# SAST_PCB_V2B_Test_Beta_Main.net
KiCad netlist of a schematic drawn in Altium Designer
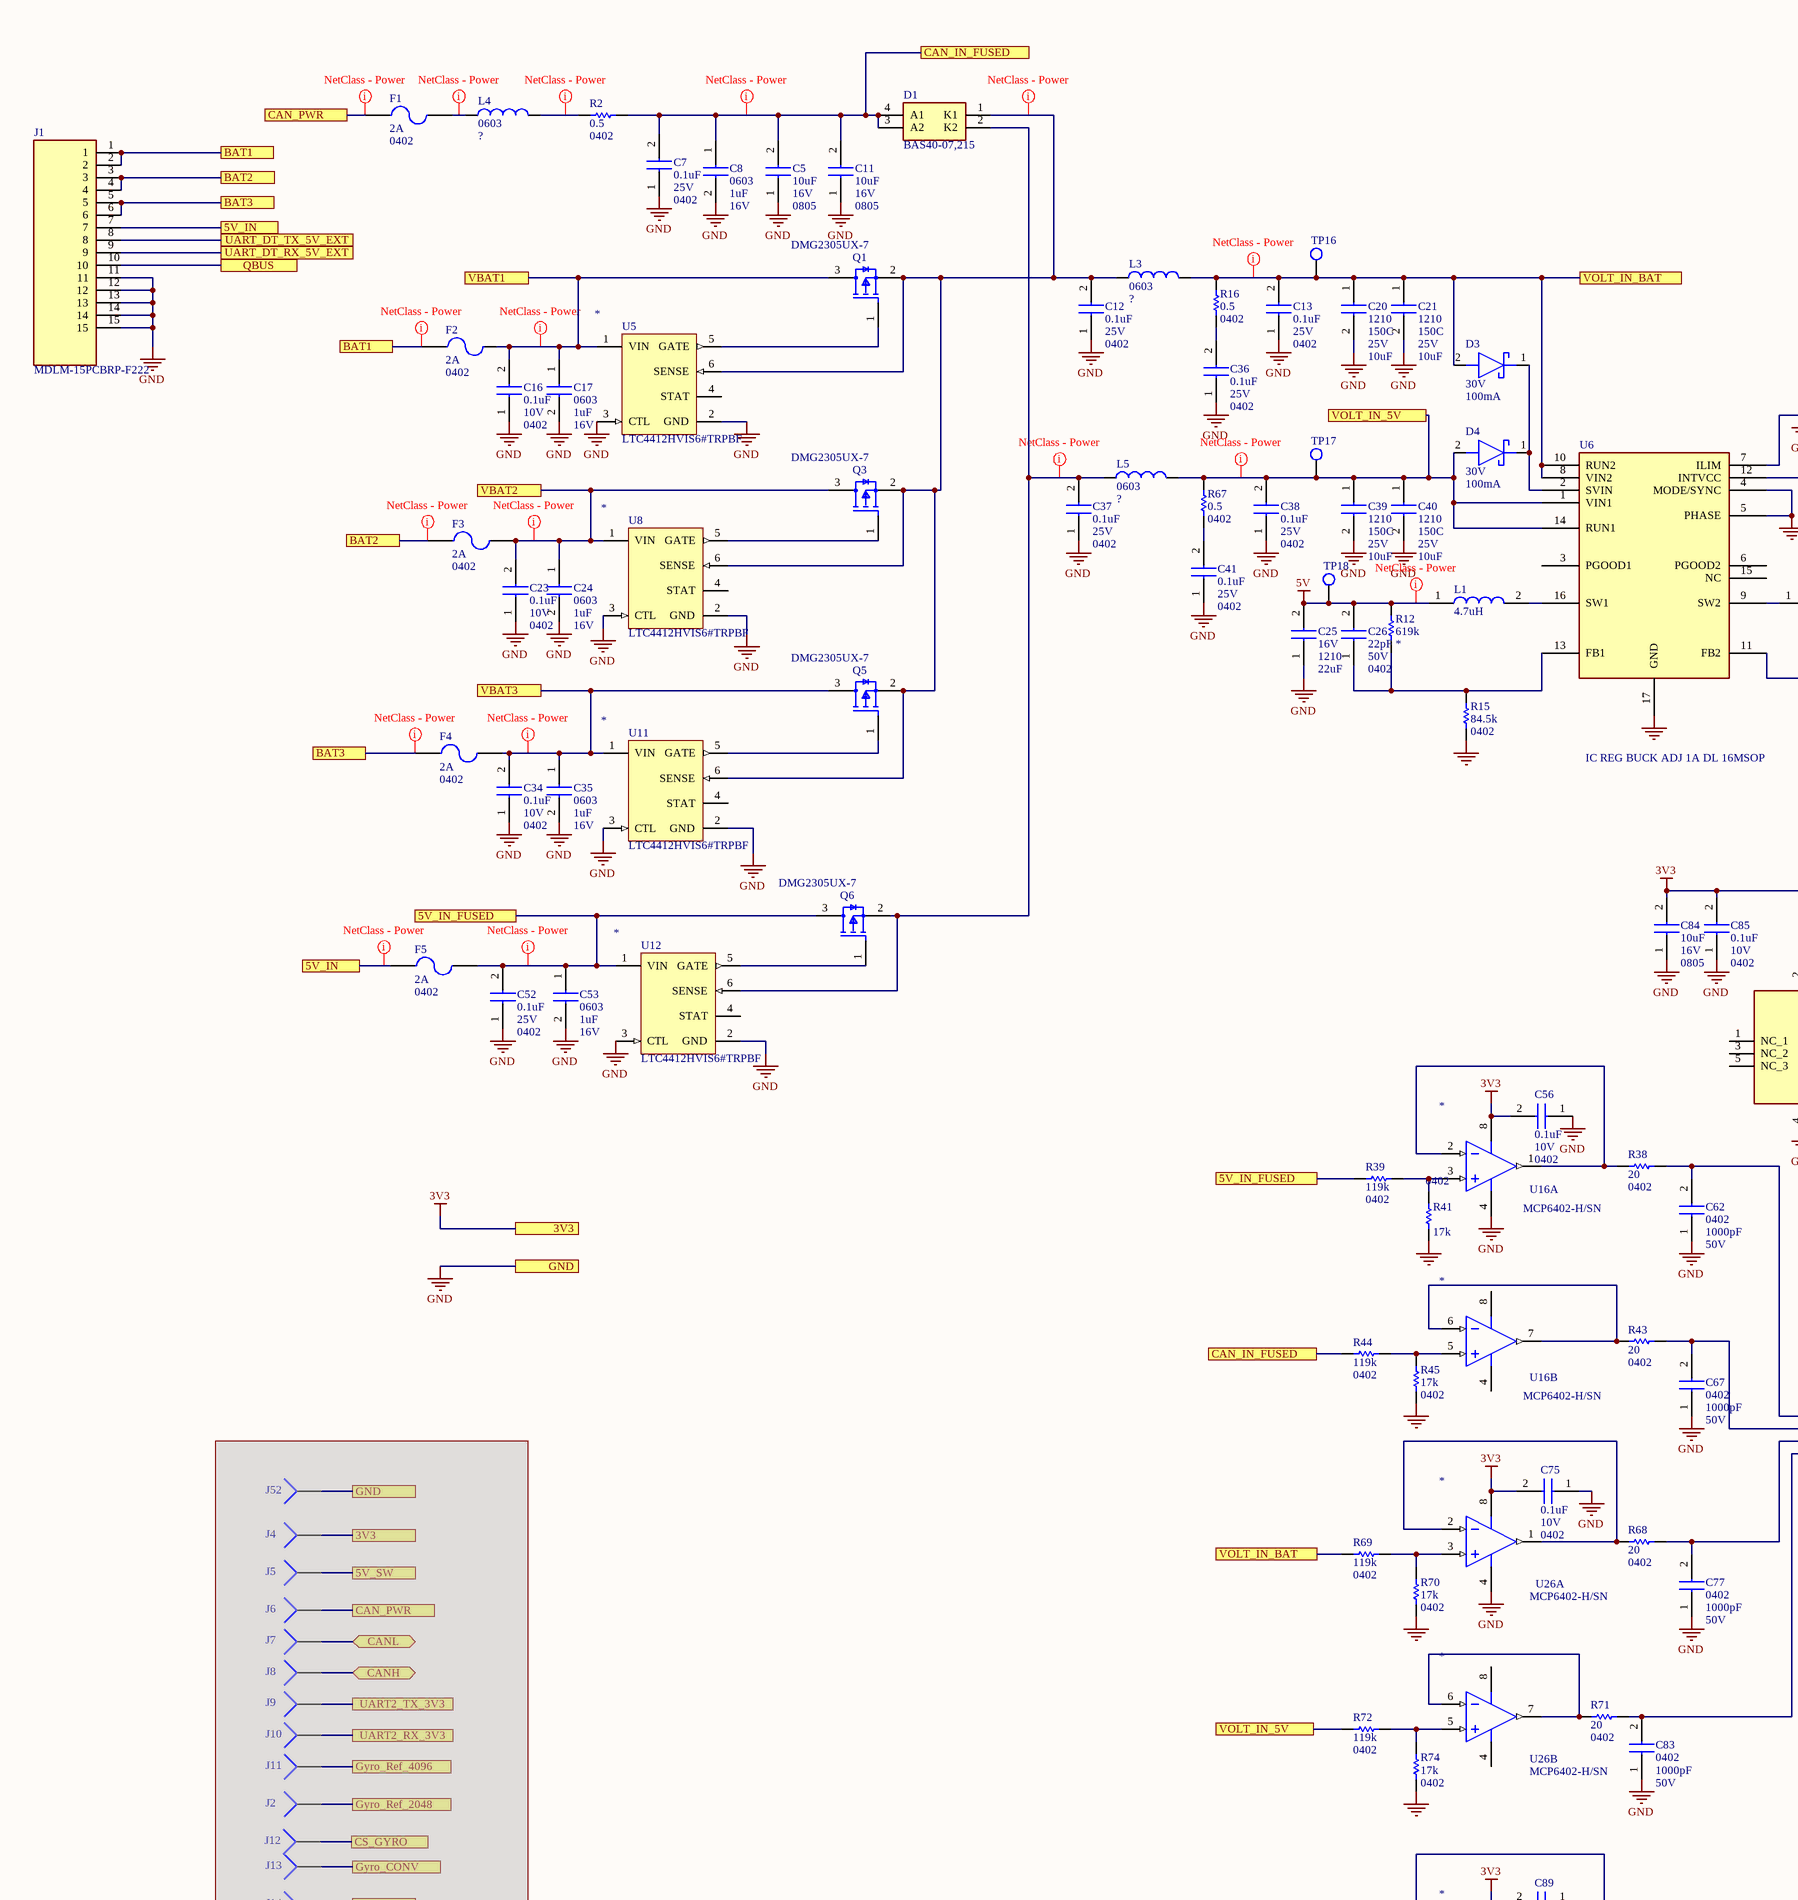
[diagram p0: SAST_PCB_V2B_Test_Beta_Main.SchDoc, top left]
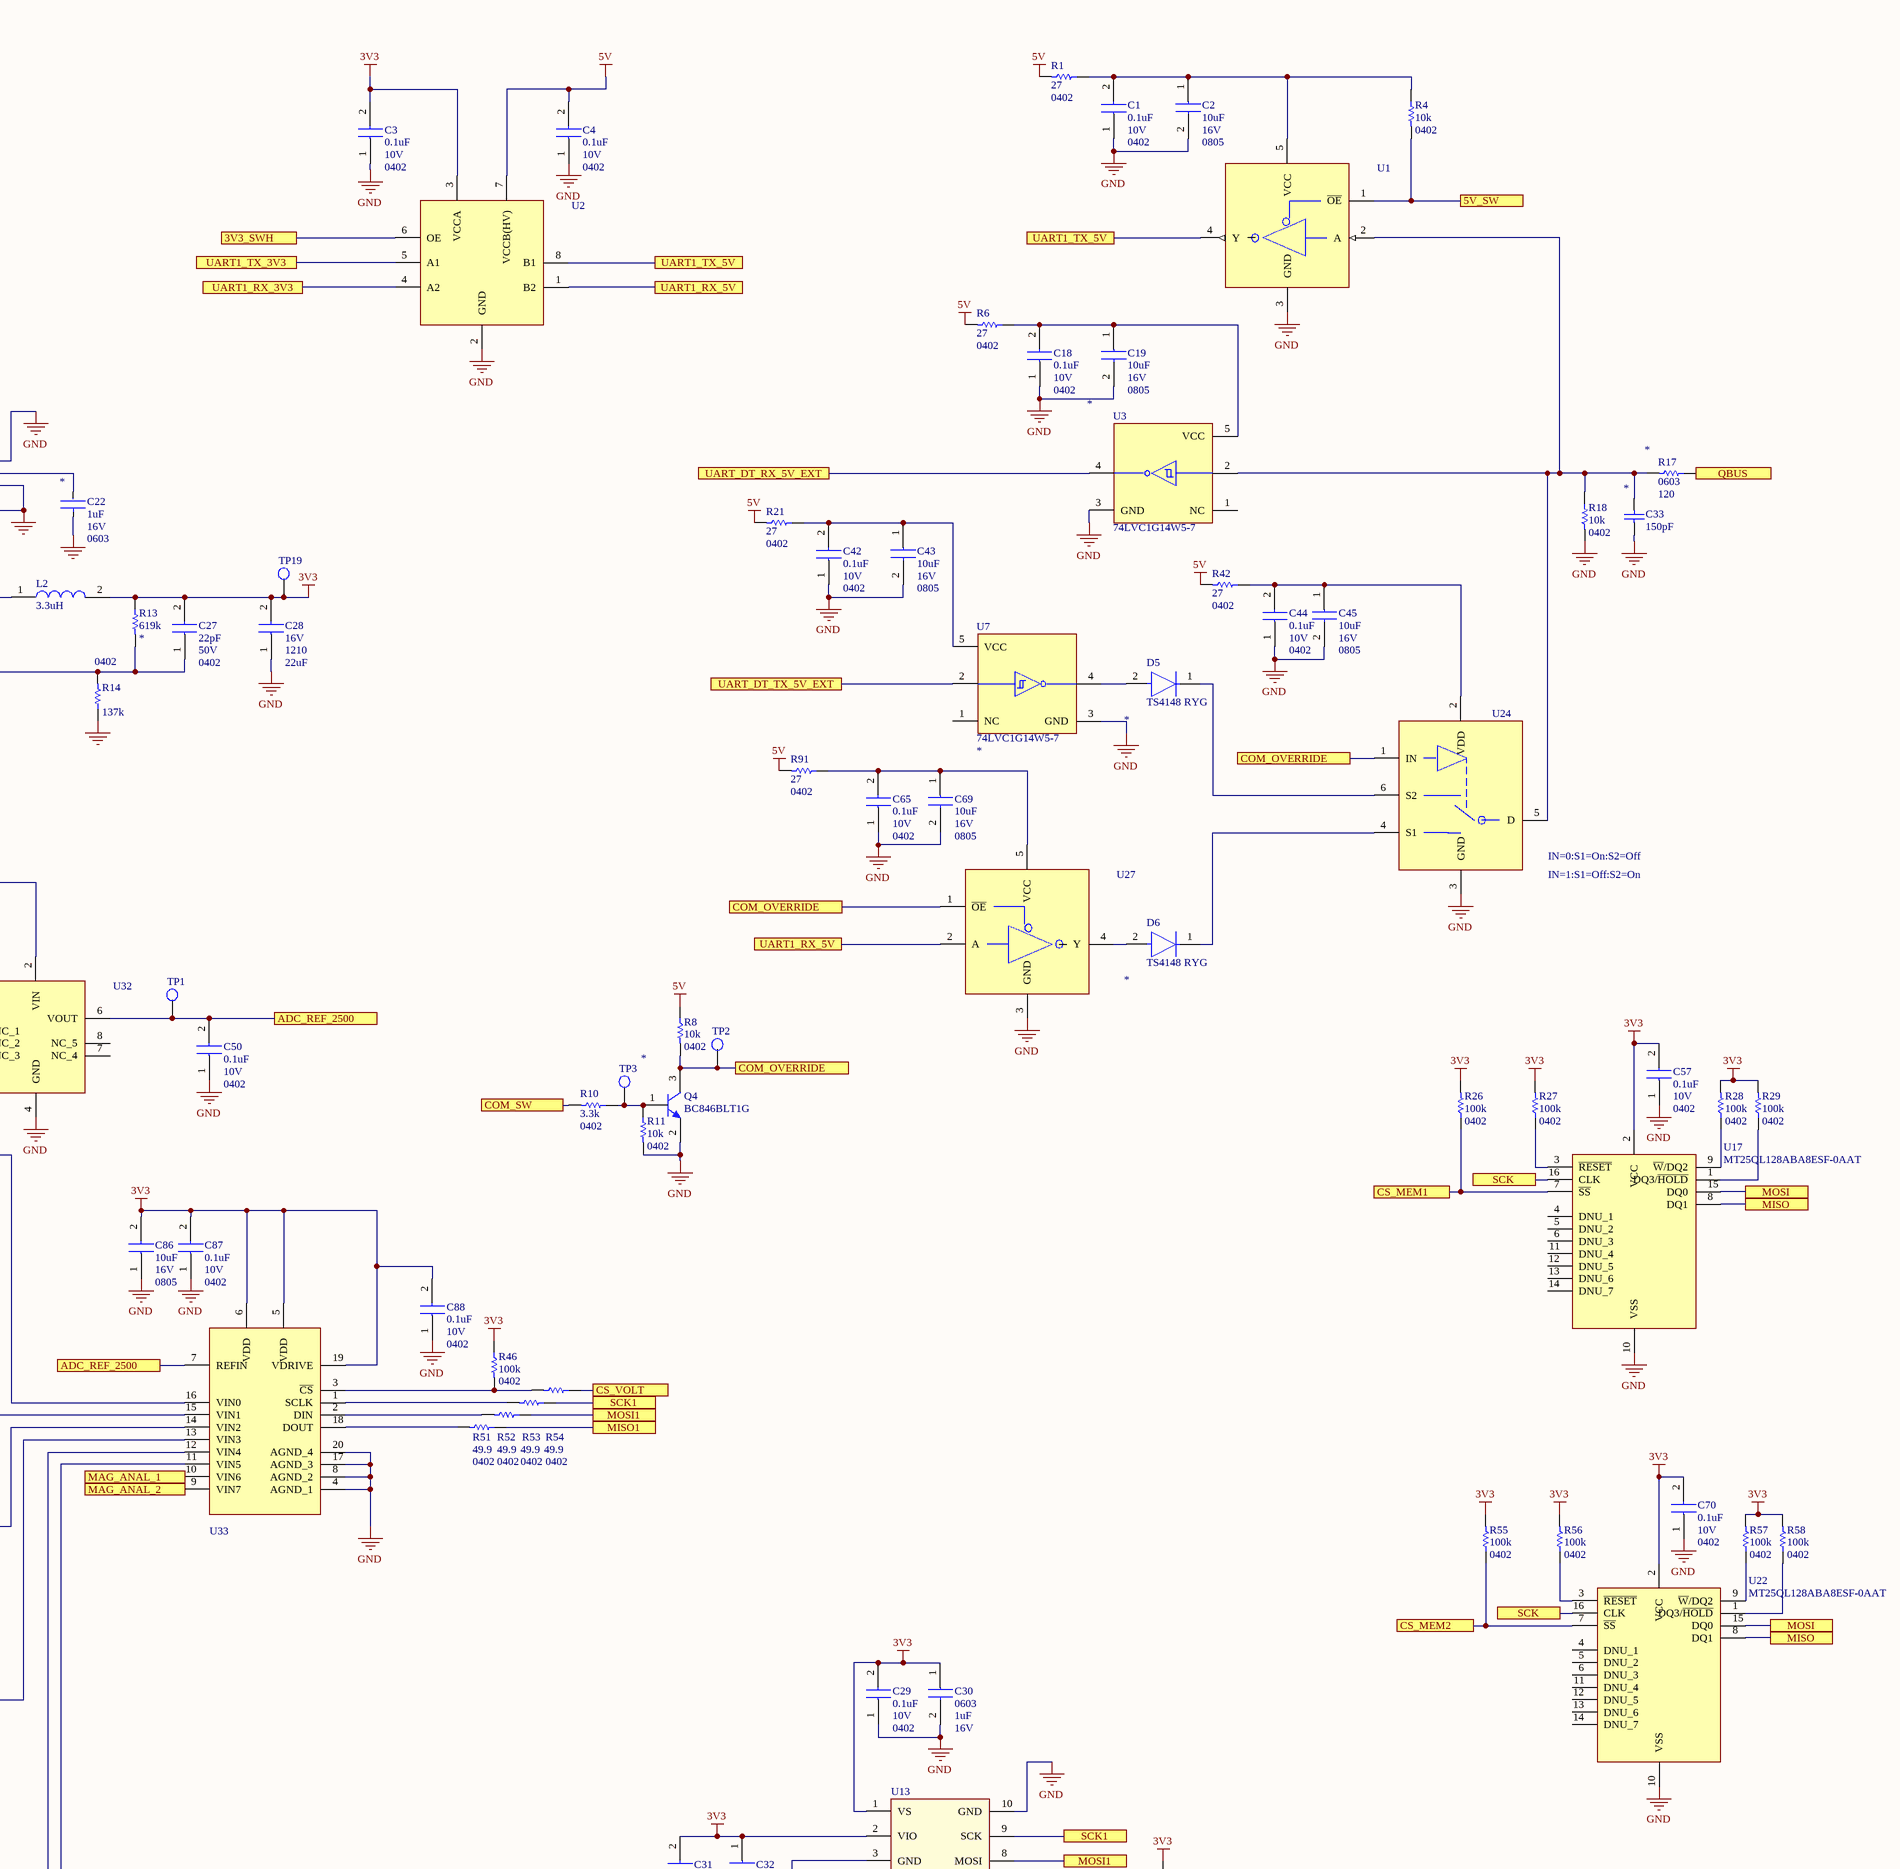
[diagram p1: SAST_PCB_V2B_Test_Beta_Main.SchDoc, top middle]
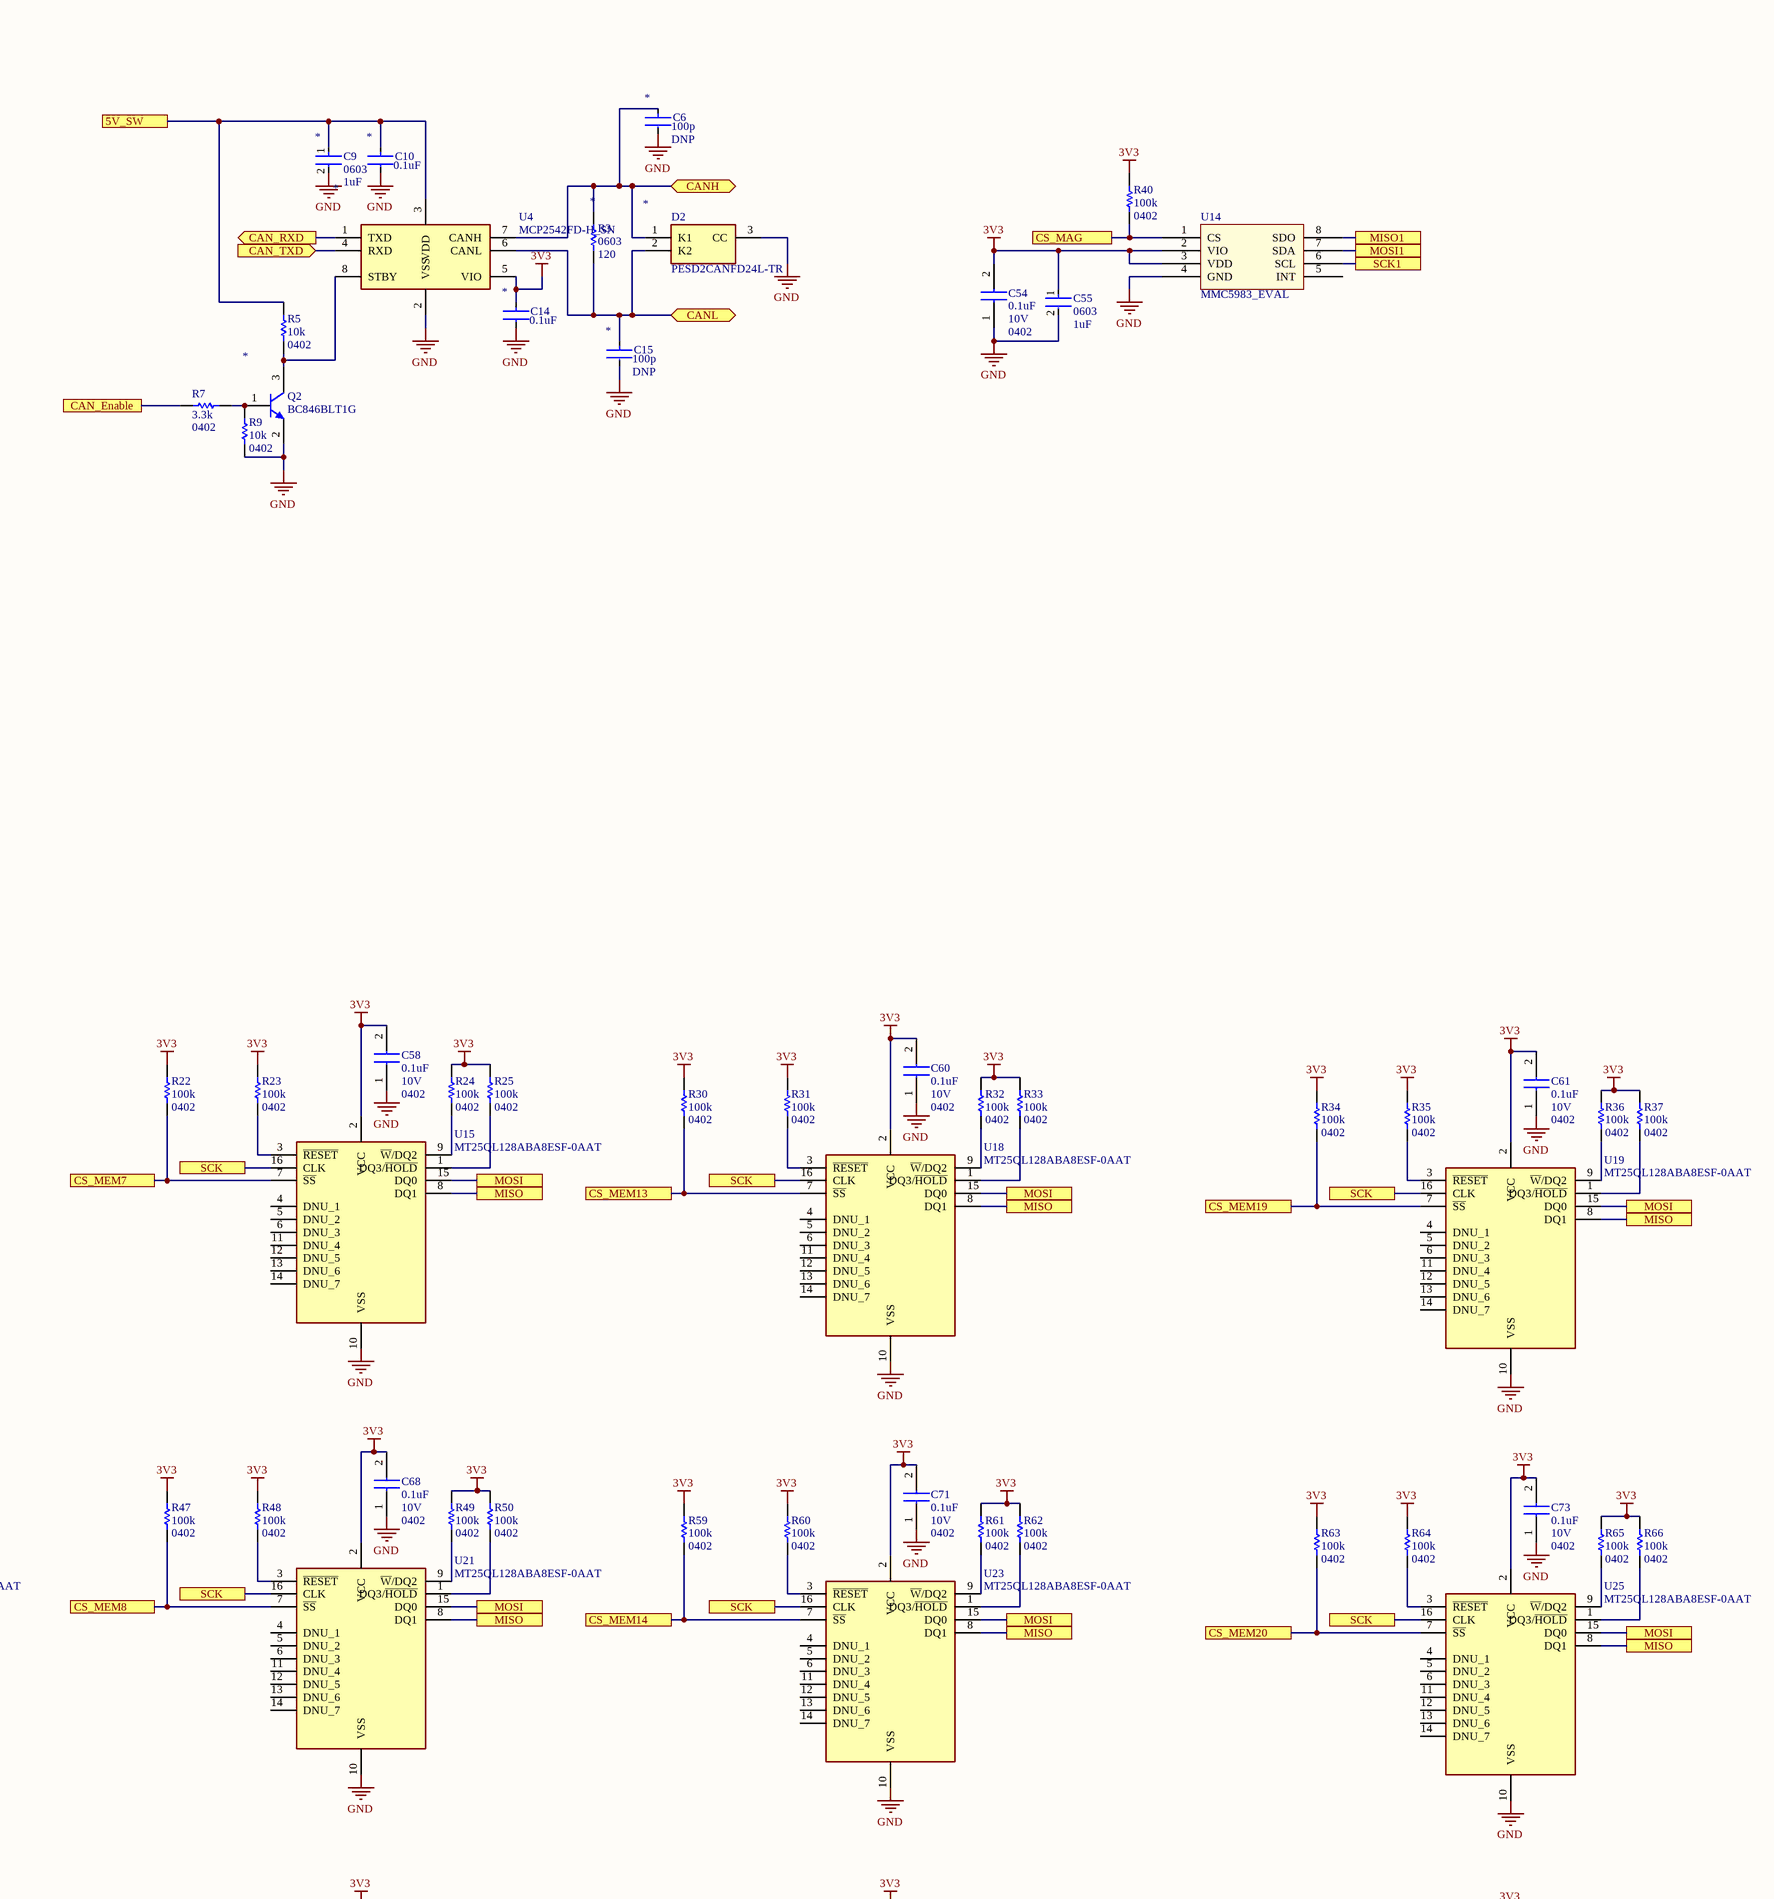
[diagram p2: SAST_PCB_V2B_Test_Beta_Main.SchDoc, top right]
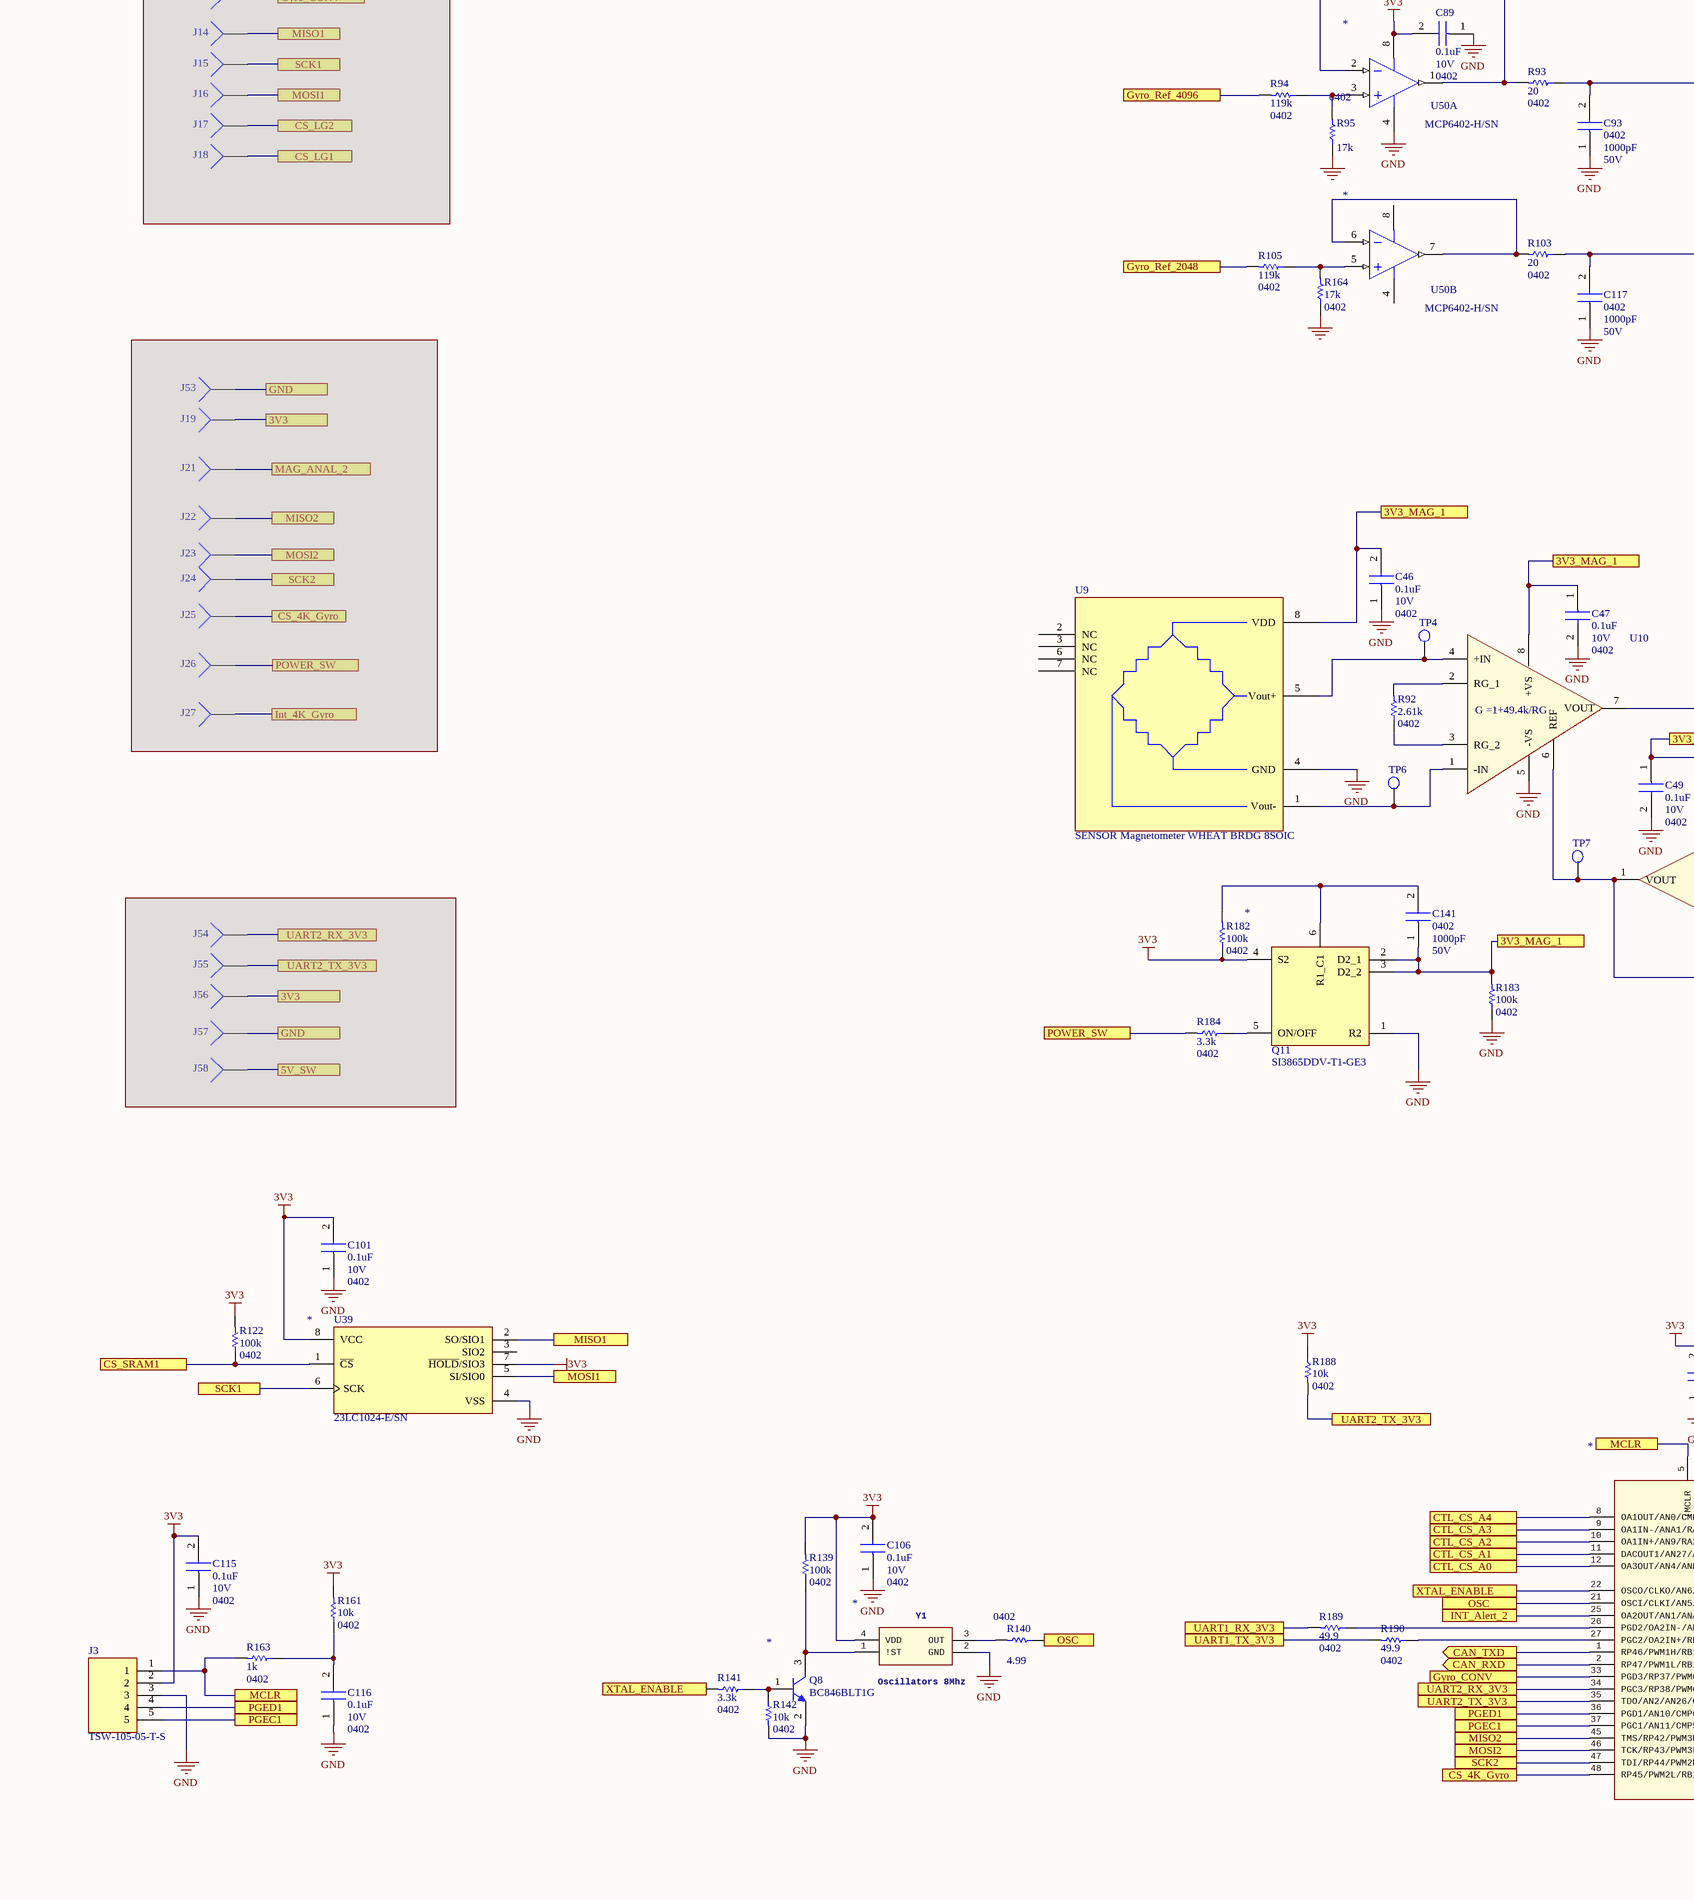
[diagram p3: SAST_PCB_V2B_Test_Beta_Main.SchDoc, bottom left]
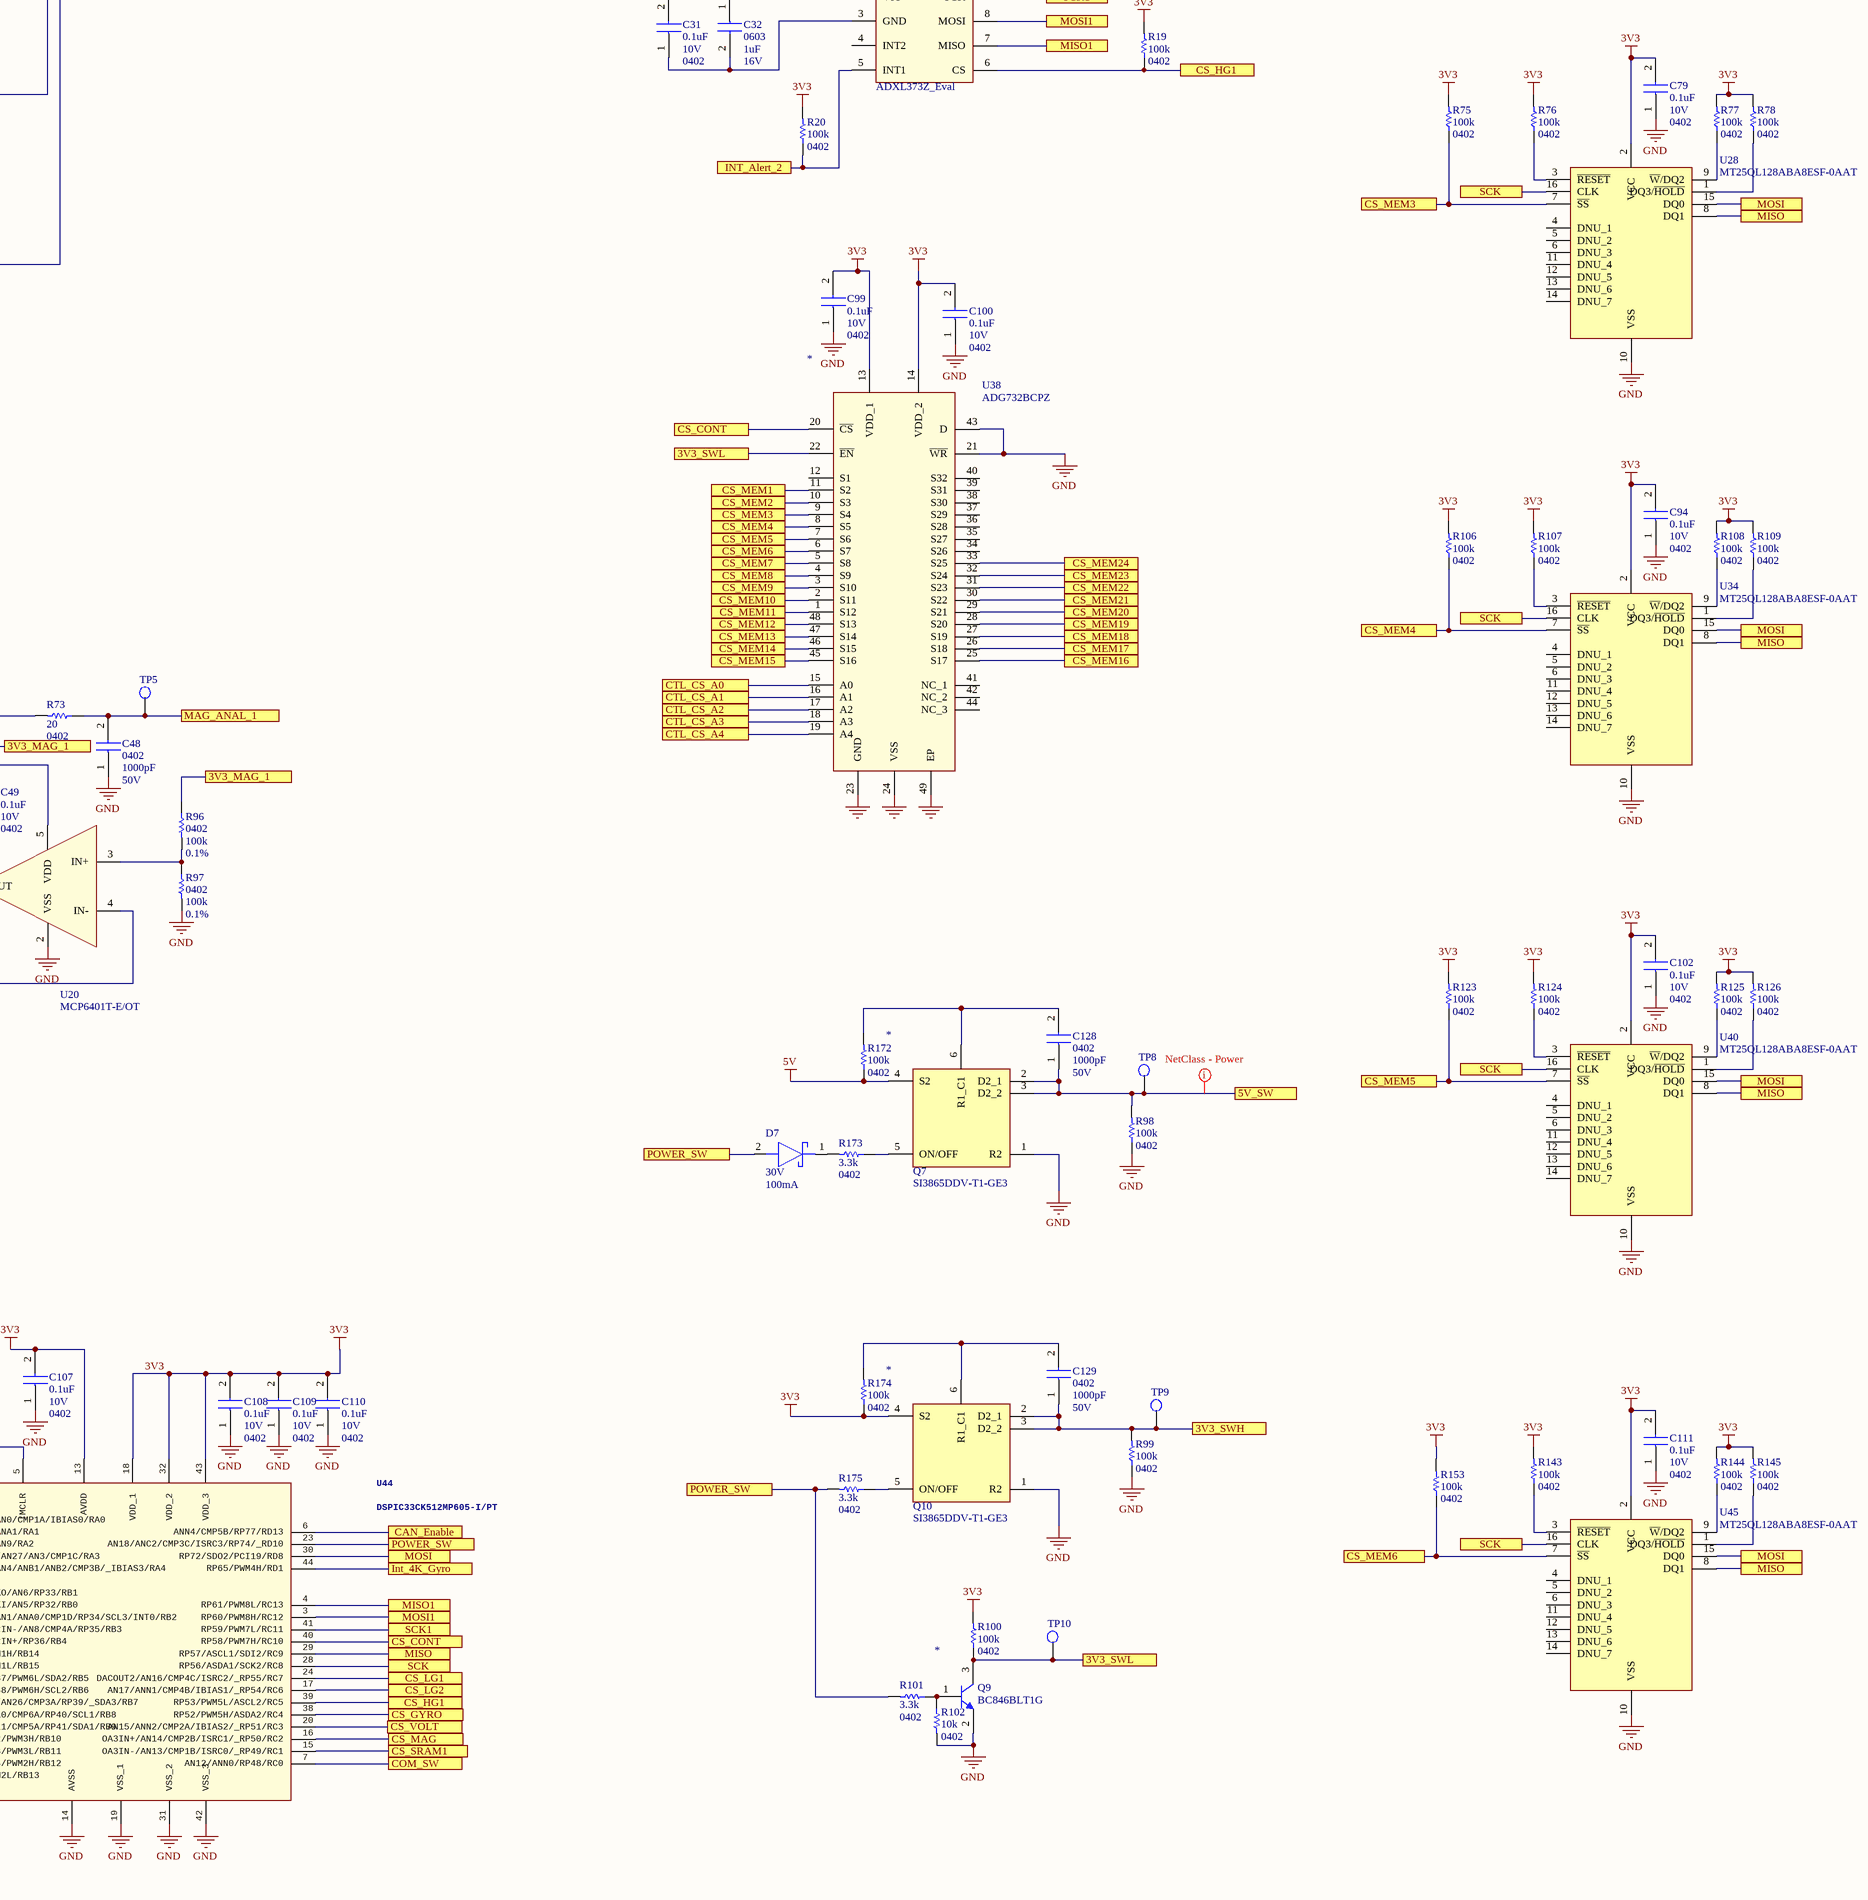
[diagram p4: SAST_PCB_V2B_Test_Beta_Main.SchDoc, bottom middle]
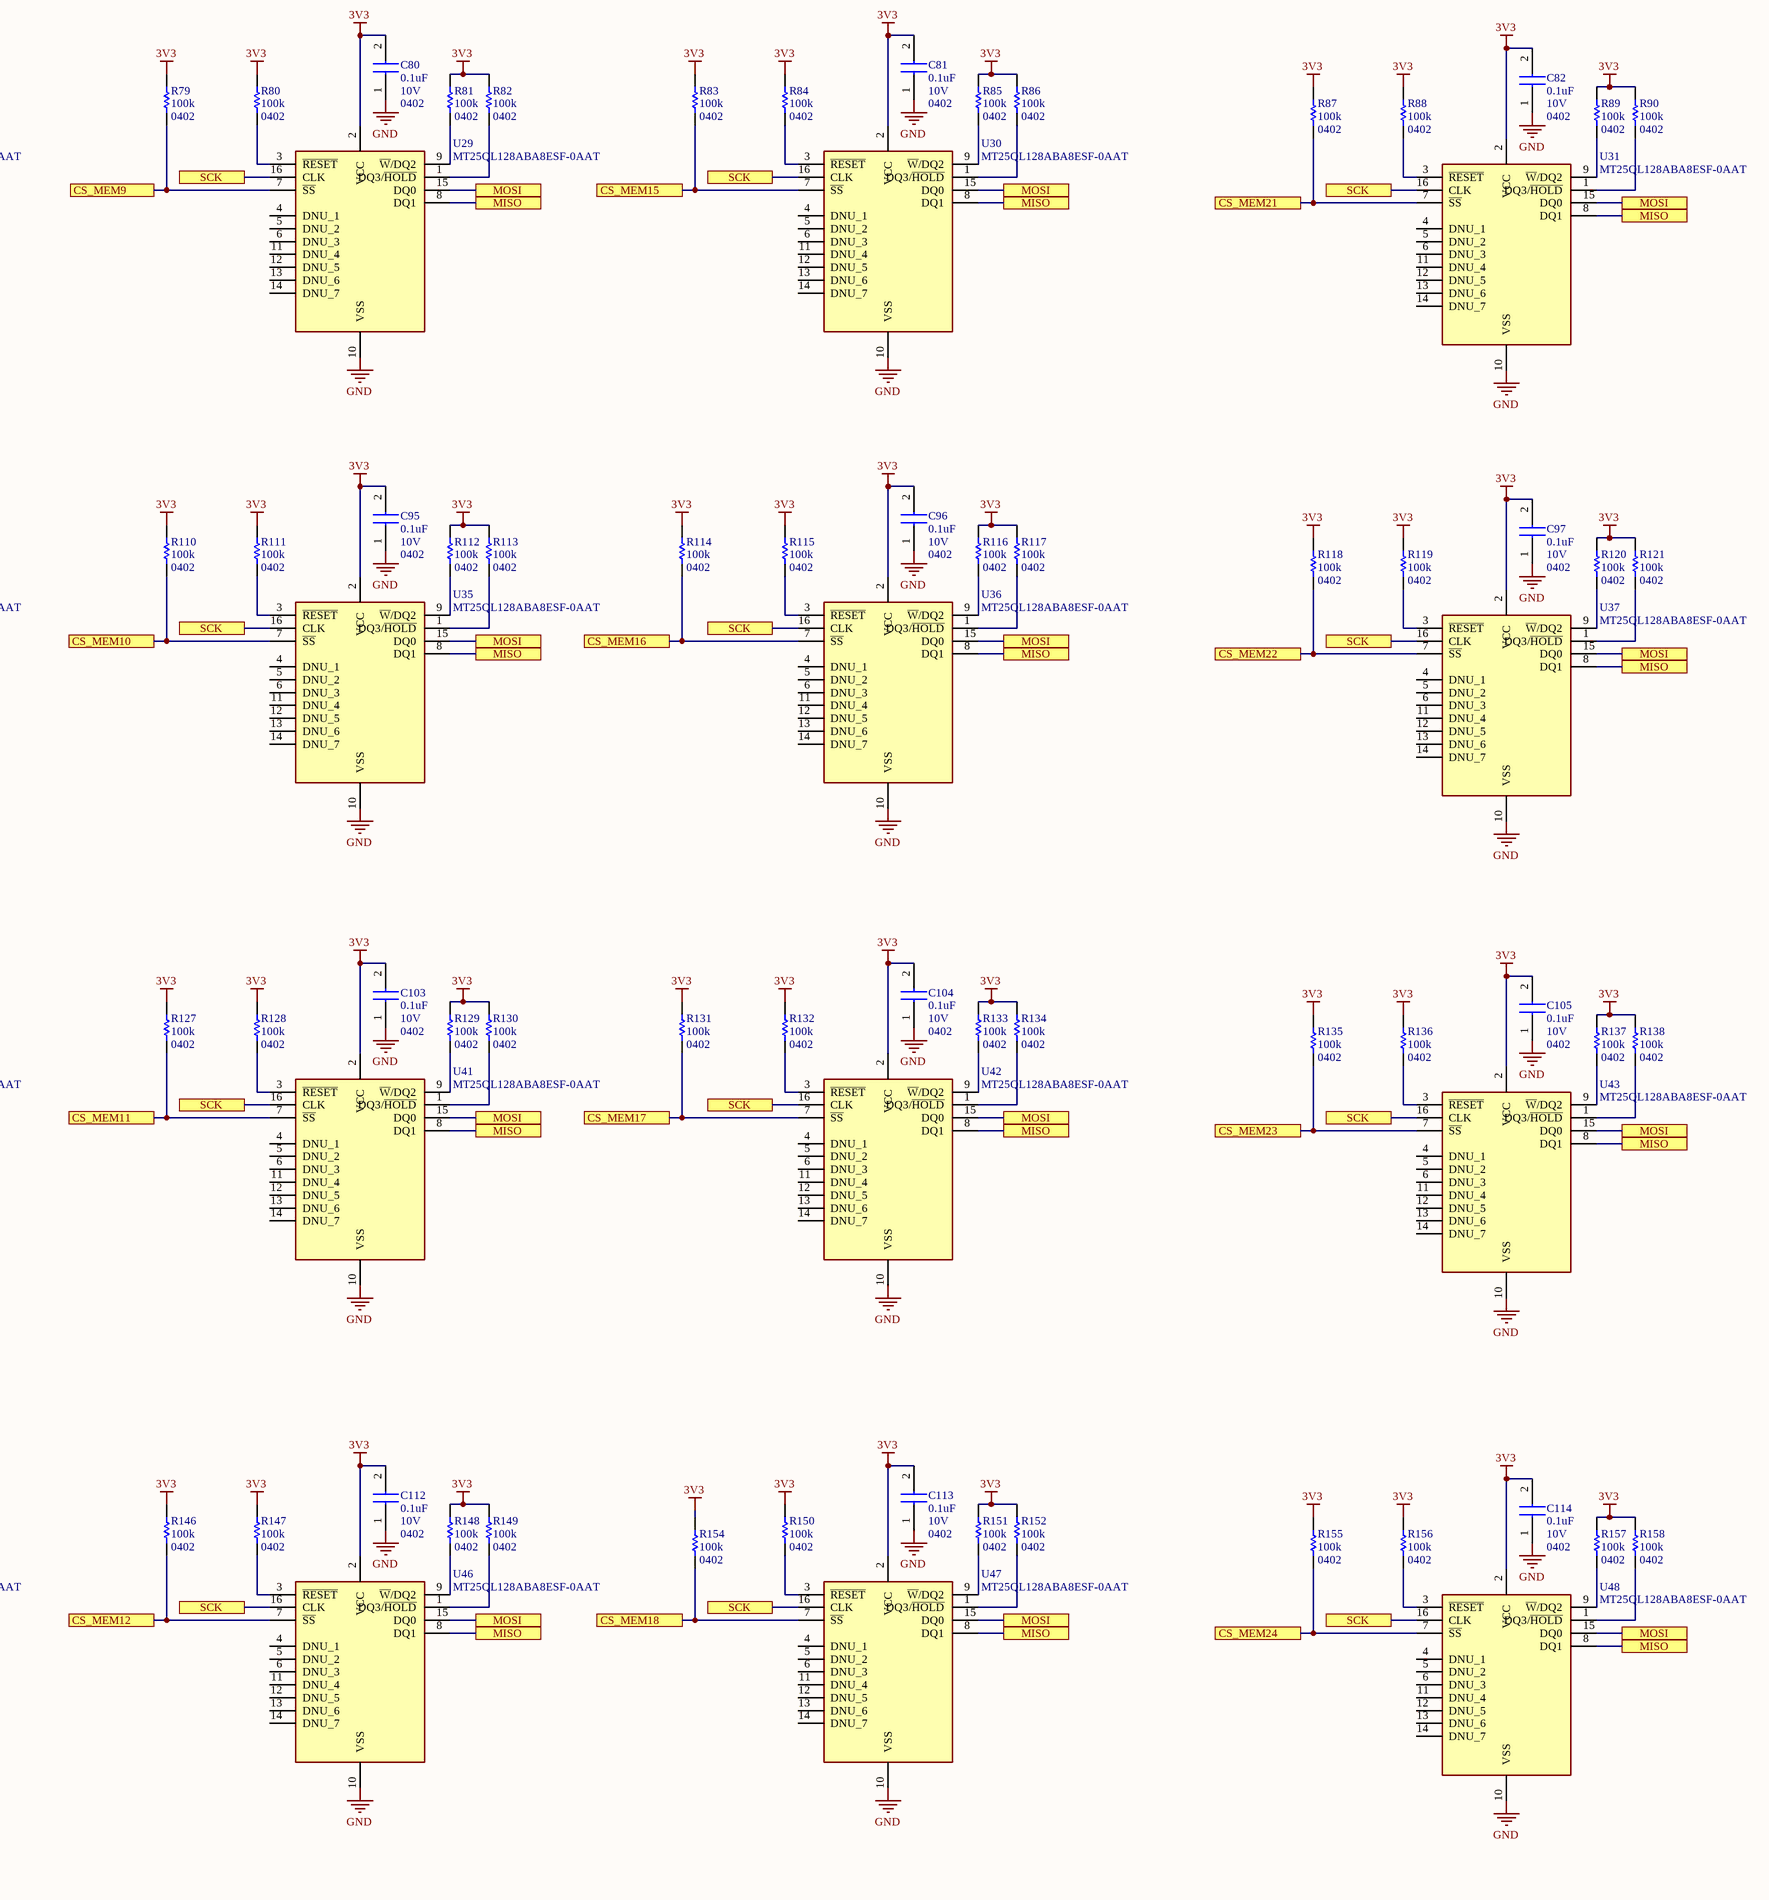
[diagram p5: SAST_PCB_V2B_Test_Beta_Main.SchDoc, bottom right]

(export (version "E")
  (design (tool "Eeschema 10.0.6"))
  (components
    (comp (ref "C1")
      (value "0.1uF")
      (footprint "0402_DSP")
      (description "Capacitor: 0.1 µF ±10% 10V Ceramic Capacitor X8M 0201")
      (fields
        (field (name "MANUFACTURER_PART_NUMBER") "GCM033M8ED104KE07J")
        (field (name "MOUSER PART NUMBER") "81-GCM033M8ED104KE07")
        (field (name "VOLTAGE") "10V")
        (field (name "CASE/PACKAGE") "0402")
      )
      (libsource (lib "CS_Library") (part "GCM033M8ED104KE07J"))
    )
    (comp (ref "C2")
      (value "10uF")
      (footprint "0805_DSP")
      (description "Capacitor:  10 µF ±10% 16V Ceramic Capacitor X8M 0805 (2012 Metric)")
      (fields
        (field (name "MANUFACTURER_PART_NUMBER") "GCM21BM8EE106KE08L")
        (field (name "MOUSER PART NUMBER") "81-GCM21BM8EE106KE8L")
        (field (name "VOLTAGE") "16V")
        (field (name "CASE/PACKAGE") "0805")
      )
      (libsource (lib "CS_Library") (part "GCM21BM8EE106KE08L"))
    )
    (comp (ref "C3")
      (value "0.1uF")
      (footprint "0402_DSP")
      (description "Capacitor: 0.1 µF ±10% 10V Ceramic Capacitor X8M 0201")
      (fields
        (field (name "MANUFACTURER_PART_NUMBER") "GCM033M8ED104KE07J")
        (field (name "MOUSER PART NUMBER") "81-GCM033M8ED104KE07")
        (field (name "VOLTAGE") "10V")
        (field (name "CASE/PACKAGE") "0402")
      )
      (libsource (lib "CS_Library") (part "GCM033M8ED104KE07J"))
    )
    (comp (ref "C4")
      (value "0.1uF")
      (footprint "0402_DSP")
      (description "Capacitor: 0.1 µF ±10% 10V Ceramic Capacitor X8M 0201")
      (fields
        (field (name "MANUFACTURER_PART_NUMBER") "GCM033M8ED104KE07J")
        (field (name "MOUSER PART NUMBER") "81-GCM033M8ED104KE07")
        (field (name "VOLTAGE") "10V")
        (field (name "CASE/PACKAGE") "0402")
      )
      (libsource (lib "CS_Library") (part "GCM033M8ED104KE07J"))
    )
    (comp (ref "C5")
      (value "10uF")
      (footprint "CS_Library:CAPC2012X140N")
      (description "Capacitor:  10 µF ±10% 16V Ceramic Capacitor X8M 0805 (2012 Metric)")
      (fields
        (field (name "MANUFACTURER_PART_NUMBER") "GCM21BM8EE106KE08L")
        (field (name "MOUSER PART NUMBER") "81-GCM21BM8EE106KE8L")
        (field (name "VOLTAGE") "16V")
        (field (name "CASE/PACKAGE") "0805")
      )
      (libsource (lib "CS_Library") (part "GCM21BM8EE106KE08L"))
    )
    (comp (ref "C6")
      (value "100p")
      (footprint "FP-GCM155-0_05-IPC_B")
      (description "Ceramic Capacitor for Automotive 100nF ±10% 25VDC X8L 0402 Paper T/R")
      (fields
        (field (name "MANUFACTURING") "DNP")
        (field (name "CASE/PACKAGE") "*")
        (field (name "Comment") "GCM155L81E104KE02D")
      )
      (libsource (lib "") (part "02cd4be3c70576c341d710602a673aa_1"))
    )
    (comp (ref "C7")
      (value "0.1uF")
      (footprint "CS_Library:0402_DSP")
      (description "Capacitor: 0.1 µF ±10% 25V Ceramic Capacitor X8L 0402 (1005 Metric)")
      (fields
        (field (name "MANUFACTURER_PART_NUMBER") "GCM155L81E104KE02D")
        (field (name "MOUSER PART NUMBER") "81-GCM155L81E104KE2D")
        (field (name "VOLTAGE") "25V")
        (field (name "CASE/PACKAGE") "0402")
      )
      (libsource (lib "CS_Library") (part "GCM155L81E104KE02D"))
    )
    (comp (ref "C8")
      (value "1uF")
      (footprint "0603_DSP")
      (description "Capacitor: 1 µF ±10% 16V Ceramic Capacitor X8L 0603")
      (fields
        (field (name "MANUFACTURER_PART_NUMBER") "GCG188L8EE105KA07D")
        (field (name "MOUSER PART NUMBER") "81-GCG188L8EE105KA7D")
        (field (name "CASE/PACKAGE") "0603")
        (field (name "VOLTAGE") "16V")
      )
      (libsource (lib "CS_Library") (part "GCG188L8EE105KA07D"))
    )
    (comp (ref "C9")
      (value "0603")
      (footprint "FP-GCG188-0_2-IPC_A")
      (fields
        (field (name "MANUFACTURER_PART_NUMBER") "GCG188L8EE105KA07D")
        (field (name "ALTIUM_VALUE") "1uF")
        (field (name "VOLTAGE") "16V")
        (field (name "CASE/PACKAGE") "*")
      )
      (libsource (lib "Altium Content Vault") (part "02cd4be3c70576c341d710602a673aa"))
    )
    (comp (ref "C10")
      (value "0.1uF")
      (footprint "FP-GCM155-0_05-IPC_B")
      (description "Ceramic Capacitor for Automotive 100nF ±10% 25VDC X8L 0402 Paper T/R")
      (fields
        (field (name "MANUFACTURER_PART_NUMBER") "GCM155L81E104KE02D")
        (field (name "VOLTAGE") "25V")
        (field (name "CASE/PACKAGE") "*")
      )
      (libsource (lib "") (part "02cd4be3c70576c341d710602a673aa_1"))
    )
    (comp (ref "C11")
      (value "10uF")
      (footprint "CS_Library:CAPC2012X140N")
      (description "Capacitor:  10 µF ±10% 16V Ceramic Capacitor X8M 0805 (2012 Metric)")
      (fields
        (field (name "MANUFACTURER_PART_NUMBER") "GCM21BM8EE106KE08L")
        (field (name "MOUSER PART NUMBER") "81-GCM21BM8EE106KE8L")
        (field (name "VOLTAGE") "16V")
        (field (name "CASE/PACKAGE") "0805")
      )
      (libsource (lib "CS_Library") (part "GCM21BM8EE106KE08L"))
    )
    (comp (ref "C12")
      (value "0.1uF")
      (footprint "CS_Library:0402_DSP")
      (description "Capacitor: 0.1 µF ±10% 25V Ceramic Capacitor X8L 0402 (1005 Metric)")
      (fields
        (field (name "MANUFACTURER_PART_NUMBER") "GCM155L81E104KE02D")
        (field (name "MOUSER PART NUMBER") "81-GCM155L81E104KE2D")
        (field (name "VOLTAGE") "25V")
        (field (name "CASE/PACKAGE") "0402")
      )
      (libsource (lib "CS_Library") (part "GCM155L81E104KE02D"))
    )
    (comp (ref "C13")
      (value "0.1uF")
      (footprint "CS_Library:0402_DSP")
      (description "Capacitor: 0.1 µF ±10% 25V Ceramic Capacitor X8L 0402 (1005 Metric)")
      (fields
        (field (name "MANUFACTURER_PART_NUMBER") "GCM155L81E104KE02D")
        (field (name "MOUSER PART NUMBER") "81-GCM155L81E104KE2D")
        (field (name "VOLTAGE") "25V")
        (field (name "CASE/PACKAGE") "0402")
      )
      (libsource (lib "CS_Library") (part "GCM155L81E104KE02D"))
    )
    (comp (ref "C14")
      (value "0.1uF")
      (footprint "FP-GCM155-0_05-IPC_B")
      (description "Ceramic Capacitor for Automotive 100nF ±10% 25VDC X8L 0402 Paper T/R")
      (fields
        (field (name "MANUFACTURER_PART_NUMBER") "GCM155L81E104KE02D")
        (field (name "VOLTAGE") "25V")
        (field (name "CASE/PACKAGE") "*")
      )
      (libsource (lib "") (part "02cd4be3c70576c341d710602a673aa_1"))
    )
    (comp (ref "C15")
      (value "100p")
      (footprint "FP-GCM155-0_05-IPC_B")
      (description "Ceramic Capacitor for Automotive 100nF ±10% 25VDC X8L 0402 Paper T/R")
      (fields
        (field (name "MANUFACTURING") "DNP")
        (field (name "CASE/PACKAGE") "*")
        (field (name "Comment") "GCM155L81E104KE02D")
      )
      (libsource (lib "") (part "02cd4be3c70576c341d710602a673aa_1"))
    )
    (comp (ref "C16")
      (value "0.1uF")
      (footprint "0402_DSP")
      (description "Capacitor: 0.1 µF ±10% 10V Ceramic Capacitor X8M 0201")
      (fields
        (field (name "MANUFACTURER_PART_NUMBER") "GCM033M8ED104KE07J")
        (field (name "MOUSER PART NUMBER") "81-GCM033M8ED104KE07")
        (field (name "VOLTAGE") "10V")
        (field (name "CASE/PACKAGE") "0402")
      )
      (libsource (lib "CS_Library") (part "GCM033M8ED104KE07J"))
    )
    (comp (ref "C17")
      (value "1uF")
      (footprint "0603_DSP")
      (description "Capacitor: 1 µF ±10% 16V Ceramic Capacitor X8L 0603")
      (fields
        (field (name "MANUFACTURER_PART_NUMBER") "GCG188L8EE105KA07D")
        (field (name "MOUSER PART NUMBER") "81-GCG188L8EE105KA7D")
        (field (name "CASE/PACKAGE") "0603")
        (field (name "VOLTAGE") "16V")
      )
      (libsource (lib "CS_Library") (part "GCG188L8EE105KA07D"))
    )
    (comp (ref "C18")
      (value "0.1uF")
      (footprint "0402_DSP")
      (description "Capacitor: 0.1 µF ±10% 10V Ceramic Capacitor X8M 0201")
      (fields
        (field (name "MANUFACTURER_PART_NUMBER") "GCM033M8ED104KE07J")
        (field (name "MOUSER PART NUMBER") "81-GCM033M8ED104KE07")
        (field (name "VOLTAGE") "10V")
        (field (name "CASE/PACKAGE") "0402")
      )
      (libsource (lib "CS_Library") (part "GCM033M8ED104KE07J"))
    )
    (comp (ref "C19")
      (value "10uF")
      (footprint "0805_DSP")
      (description "Capacitor:  10 µF ±10% 16V Ceramic Capacitor X8M 0805 (2012 Metric)")
      (fields
        (field (name "MANUFACTURER_PART_NUMBER") "GCM21BM8EE106KE08L")
        (field (name "MOUSER PART NUMBER") "81-GCM21BM8EE106KE8L")
        (field (name "VOLTAGE") "16V")
        (field (name "CASE/PACKAGE") "0805")
      )
      (libsource (lib "CS_Library") (part "GCM21BM8EE106KE08L"))
    )
    (comp (ref "C20")
      (value "10uF")
      (footprint "CS_Library:CAPC3225X280N")
      (description "Capacitor: 10 µF ±10% 25V Ceramic Capacitor X8R 1210 (3225 Metric)")
      (fields
        (field (name "MANUFACTURER_PART_NUMBER") "CGA6P1X8R1E106K250AC")
        (field (name "MOUSER PART NUMBER") "810-A6P1X816K25AC")
        (field (name "CASE/PACKAGE") "1210")
        (field (name "TEMPERATURE") "150C")
        (field (name "VOLTAGE") "25V")
      )
      (libsource (lib "CS_Library") (part "CGA6P1X8R1E106K250AC"))
    )
    (comp (ref "C21")
      (value "10uF")
      (footprint "CS_Library:CAPC3225X280N")
      (description "Capacitor: 10 µF ±10% 25V Ceramic Capacitor X8R 1210 (3225 Metric)")
      (fields
        (field (name "MANUFACTURER_PART_NUMBER") "CGA6P1X8R1E106K250AC")
        (field (name "MOUSER PART NUMBER") "810-A6P1X816K25AC")
        (field (name "CASE/PACKAGE") "1210")
        (field (name "TEMPERATURE") "150C")
        (field (name "VOLTAGE") "25V")
      )
      (libsource (lib "CS_Library") (part "CGA6P1X8R1E106K250AC"))
    )
    (comp (ref "C22")
      (value "C1608X8L1C105K080AC")
      (footprint "FP-C1608-080-0_1-IPC_A")
      (description "Multilayer Ceramic Capacitors 1μF ±10% 16V X8L SMD 0603")
      (fields
        (field (name "CAPACITANCE") "1uF")
        (field (name "CASE/PACKAGE") "*")
        (field (name "VOLTAGE RATING") "16V")
        (field (name "CASE CODE (IMPERIAL)") "0603")
        (field (name "TOLERANCE") "10%")
      )
      (libsource (lib "Altium Content Vault") (part "236180d848d6139a670b325ea6854c9"))
    )
    (comp (ref "C23")
      (value "0.1uF")
      (footprint "0402_DSP")
      (description "Capacitor: 0.1 µF ±10% 10V Ceramic Capacitor X8M 0201")
      (fields
        (field (name "MANUFACTURER_PART_NUMBER") "GCM033M8ED104KE07J")
        (field (name "MOUSER PART NUMBER") "81-GCM033M8ED104KE07")
        (field (name "VOLTAGE") "10V")
        (field (name "CASE/PACKAGE") "0402")
      )
      (libsource (lib "CS_Library") (part "GCM033M8ED104KE07J"))
    )
    (comp (ref "C24")
      (value "1uF")
      (footprint "0603_DSP")
      (description "Capacitor: 1 µF ±10% 16V Ceramic Capacitor X8L 0603")
      (fields
        (field (name "MANUFACTURER_PART_NUMBER") "GCG188L8EE105KA07D")
        (field (name "MOUSER PART NUMBER") "81-GCG188L8EE105KA7D")
        (field (name "CASE/PACKAGE") "0603")
        (field (name "VOLTAGE") "16V")
      )
      (libsource (lib "CS_Library") (part "GCG188L8EE105KA07D"))
    )
    (comp (ref "C25")
      (value "22uF")
      (footprint "CS_Library:CAPC3225X280N")
      (description "Capacitor: 22 µF ±20% 16V Ceramic Capacitor X8L 1210 (3225 Metric)")
      (fields
        (field (name "MANUFACTURER_PART_NUMBER") "CGA6P1X8L1C226M250AC")
        (field (name "MOUSER PART NUMBER") "810-CGA6P1X8L1C226M")
        (field (name "VOLTAGE") "16V")
        (field (name "CASE/PACKAGE") "1210")
      )
      (libsource (lib "CS_Library") (part "CGA6P1X8L1C226M250AC"))
    )
    (comp (ref "C26")
      (value "22pF")
      (footprint "0402_DSP")
      (description "Capacitor: 22 pF ±1% 50V Ceramic Capacitor C0G, NP0 0402 (1005 Metric)")
      (fields
        (field (name "MANUFACTURER_PART_NUMBER") "VJ0402A220FXAAC")
        (field (name "MOUSER PART NUMBER") "77-VJ0402A220FXAAC")
        (field (name "VOLTAGE") "50V")
        (field (name "CASE/PACKAGE") "0402")
      )
      (libsource (lib "CS_Library") (part "VJ0402A220FXAAC"))
    )
    (comp (ref "C27")
      (value "22pF")
      (footprint "0402_DSP")
      (description "Capacitor: 22 pF ±1% 50V Ceramic Capacitor C0G, NP0 0402 (1005 Metric)")
      (fields
        (field (name "MANUFACTURER_PART_NUMBER") "VJ0402A220FXAAC")
        (field (name "MOUSER PART NUMBER") "77-VJ0402A220FXAAC")
        (field (name "VOLTAGE") "50V")
        (field (name "CASE/PACKAGE") "0402")
      )
      (libsource (lib "CS_Library") (part "VJ0402A220FXAAC"))
    )
    (comp (ref "C28")
      (value "22uF")
      (footprint "CS_Library:CAPC3225X280N")
      (description "Capacitor: 22 µF ±20% 16V Ceramic Capacitor X8L 1210 (3225 Metric)")
      (fields
        (field (name "MANUFACTURER_PART_NUMBER") "CGA6P1X8L1C226M250AC")
        (field (name "MOUSER PART NUMBER") "810-CGA6P1X8L1C226M")
        (field (name "VOLTAGE") "16V")
        (field (name "CASE/PACKAGE") "1210")
      )
      (libsource (lib "CS_Library") (part "CGA6P1X8L1C226M250AC"))
    )
    (comp (ref "C29")
      (value "0.1uF")
      (footprint "0402_DSP")
      (description "Capacitor: 0.1 µF ±10% 10V Ceramic Capacitor X8M 0201")
      (fields
        (field (name "MANUFACTURER_PART_NUMBER") "GCM033M8ED104KE07J")
        (field (name "MOUSER PART NUMBER") "81-GCM033M8ED104KE07")
        (field (name "VOLTAGE") "10V")
        (field (name "CASE/PACKAGE") "0402")
      )
      (libsource (lib "CS_Library") (part "GCM033M8ED104KE07J"))
    )
    (comp (ref "C30")
      (value "1uF")
      (footprint "0603_DSP")
      (description "Capacitor: 1 µF ±10% 16V Ceramic Capacitor X8L 0603")
      (fields
        (field (name "MANUFACTURER_PART_NUMBER") "GCG188L8EE105KA07D")
        (field (name "MOUSER PART NUMBER") "81-GCG188L8EE105KA7D")
        (field (name "CASE/PACKAGE") "0603")
        (field (name "VOLTAGE") "16V")
      )
      (libsource (lib "CS_Library") (part "GCG188L8EE105KA07D"))
    )
    (comp (ref "C31")
      (value "0.1uF")
      (footprint "0402_DSP")
      (description "Capacitor: 0.1 µF ±10% 10V Ceramic Capacitor X8M 0201")
      (fields
        (field (name "MANUFACTURER_PART_NUMBER") "GCM033M8ED104KE07J")
        (field (name "MOUSER PART NUMBER") "81-GCM033M8ED104KE07")
        (field (name "VOLTAGE") "10V")
        (field (name "CASE/PACKAGE") "0402")
      )
      (libsource (lib "CS_Library") (part "GCM033M8ED104KE07J"))
    )
    (comp (ref "C32")
      (value "1uF")
      (footprint "0603_DSP")
      (description "Capacitor: 1 µF ±10% 16V Ceramic Capacitor X8L 0603")
      (fields
        (field (name "MANUFACTURER_PART_NUMBER") "GCG188L8EE105KA07D")
        (field (name "MOUSER PART NUMBER") "81-GCG188L8EE105KA7D")
        (field (name "CASE/PACKAGE") "0603")
        (field (name "VOLTAGE") "16V")
      )
      (libsource (lib "CS_Library") (part "GCG188L8EE105KA07D"))
    )
    (comp (ref "C33")
      (value "150pF")
      (footprint "CAPC1005X60X26LL10T16")
      (fields
        (field (name "MANUFACTURER") "Vitramon")
        (field (name "PART NUMBER") "VJ0402A151JXAAC")
        (field (name "VOLTAGE") "50V")
        (field (name "CASE/PACKAGE") "*")
      )
      (libsource (lib "Altium Content Vault") (part "CAP"))
    )
    (comp (ref "C34")
      (value "0.1uF")
      (footprint "0402_DSP")
      (description "Capacitor: 0.1 µF ±10% 10V Ceramic Capacitor X8M 0201")
      (fields
        (field (name "MANUFACTURER_PART_NUMBER") "GCM033M8ED104KE07J")
        (field (name "MOUSER PART NUMBER") "81-GCM033M8ED104KE07")
        (field (name "VOLTAGE") "10V")
        (field (name "CASE/PACKAGE") "0402")
      )
      (libsource (lib "CS_Library") (part "GCM033M8ED104KE07J"))
    )
    (comp (ref "C35")
      (value "1uF")
      (footprint "0603_DSP")
      (description "Capacitor: 1 µF ±10% 16V Ceramic Capacitor X8L 0603")
      (fields
        (field (name "MANUFACTURER_PART_NUMBER") "GCG188L8EE105KA07D")
        (field (name "MOUSER PART NUMBER") "81-GCG188L8EE105KA7D")
        (field (name "CASE/PACKAGE") "0603")
        (field (name "VOLTAGE") "16V")
      )
      (libsource (lib "CS_Library") (part "GCG188L8EE105KA07D"))
    )
    (comp (ref "C36")
      (value "0.1uF")
      (footprint "CS_Library:0402_DSP")
      (description "Capacitor: 0.1 µF ±10% 25V Ceramic Capacitor X8L 0402 (1005 Metric)")
      (fields
        (field (name "MANUFACTURER_PART_NUMBER") "GCM155L81E104KE02D")
        (field (name "MOUSER PART NUMBER") "81-GCM155L81E104KE2D")
        (field (name "VOLTAGE") "25V")
        (field (name "CASE/PACKAGE") "0402")
      )
      (libsource (lib "CS_Library") (part "GCM155L81E104KE02D"))
    )
    (comp (ref "C37")
      (value "0.1uF")
      (footprint "CS_Library:0402_DSP")
      (description "Capacitor: 0.1 µF ±10% 25V Ceramic Capacitor X8L 0402 (1005 Metric)")
      (fields
        (field (name "MANUFACTURER_PART_NUMBER") "GCM155L81E104KE02D")
        (field (name "MOUSER PART NUMBER") "81-GCM155L81E104KE2D")
        (field (name "VOLTAGE") "25V")
        (field (name "CASE/PACKAGE") "0402")
      )
      (libsource (lib "CS_Library") (part "GCM155L81E104KE02D"))
    )
    (comp (ref "C38")
      (value "0.1uF")
      (footprint "CS_Library:0402_DSP")
      (description "Capacitor: 0.1 µF ±10% 25V Ceramic Capacitor X8L 0402 (1005 Metric)")
      (fields
        (field (name "MANUFACTURER_PART_NUMBER") "GCM155L81E104KE02D")
        (field (name "MOUSER PART NUMBER") "81-GCM155L81E104KE2D")
        (field (name "VOLTAGE") "25V")
        (field (name "CASE/PACKAGE") "0402")
      )
      (libsource (lib "CS_Library") (part "GCM155L81E104KE02D"))
    )
    (comp (ref "C39")
      (value "10uF")
      (footprint "CS_Library:CAPC3225X280N")
      (description "Capacitor: 10 µF ±10% 25V Ceramic Capacitor X8R 1210 (3225 Metric)")
      (fields
        (field (name "MANUFACTURER_PART_NUMBER") "CGA6P1X8R1E106K250AC")
        (field (name "MOUSER PART NUMBER") "810-A6P1X816K25AC")
        (field (name "CASE/PACKAGE") "1210")
        (field (name "TEMPERATURE") "150C")
        (field (name "VOLTAGE") "25V")
      )
      (libsource (lib "CS_Library") (part "CGA6P1X8R1E106K250AC"))
    )
    (comp (ref "C40")
      (value "10uF")
      (footprint "CS_Library:CAPC3225X280N")
      (description "Capacitor: 10 µF ±10% 25V Ceramic Capacitor X8R 1210 (3225 Metric)")
      (fields
        (field (name "MANUFACTURER_PART_NUMBER") "CGA6P1X8R1E106K250AC")
        (field (name "MOUSER PART NUMBER") "810-A6P1X816K25AC")
        (field (name "CASE/PACKAGE") "1210")
        (field (name "TEMPERATURE") "150C")
        (field (name "VOLTAGE") "25V")
      )
      (libsource (lib "CS_Library") (part "CGA6P1X8R1E106K250AC"))
    )
    (comp (ref "C41")
      (value "0.1uF")
      (footprint "CS_Library:0402_DSP")
      (description "Capacitor: 0.1 µF ±10% 25V Ceramic Capacitor X8L 0402 (1005 Metric)")
      (fields
        (field (name "MANUFACTURER_PART_NUMBER") "GCM155L81E104KE02D")
        (field (name "MOUSER PART NUMBER") "81-GCM155L81E104KE2D")
        (field (name "VOLTAGE") "25V")
        (field (name "CASE/PACKAGE") "0402")
      )
      (libsource (lib "CS_Library") (part "GCM155L81E104KE02D"))
    )
    (comp (ref "C42")
      (value "0.1uF")
      (footprint "0402_DSP")
      (description "Capacitor: 0.1 µF ±10% 10V Ceramic Capacitor X8M 0201")
      (fields
        (field (name "MANUFACTURER_PART_NUMBER") "GCM033M8ED104KE07J")
        (field (name "MOUSER PART NUMBER") "81-GCM033M8ED104KE07")
        (field (name "VOLTAGE") "10V")
        (field (name "CASE/PACKAGE") "0402")
      )
      (libsource (lib "CS_Library") (part "GCM033M8ED104KE07J"))
    )
    (comp (ref "C43")
      (value "10uF")
      (footprint "0805_DSP")
      (description "Capacitor:  10 µF ±10% 16V Ceramic Capacitor X8M 0805 (2012 Metric)")
      (fields
        (field (name "MANUFACTURER_PART_NUMBER") "GCM21BM8EE106KE08L")
        (field (name "MOUSER PART NUMBER") "81-GCM21BM8EE106KE8L")
        (field (name "VOLTAGE") "16V")
        (field (name "CASE/PACKAGE") "0805")
      )
      (libsource (lib "CS_Library") (part "GCM21BM8EE106KE08L"))
    )
    (comp (ref "C44")
      (value "0.1uF")
      (footprint "0402_DSP")
      (description "Capacitor: 0.1 µF ±10% 10V Ceramic Capacitor X8M 0201")
      (fields
        (field (name "MANUFACTURER_PART_NUMBER") "GCM033M8ED104KE07J")
        (field (name "MOUSER PART NUMBER") "81-GCM033M8ED104KE07")
        (field (name "VOLTAGE") "10V")
        (field (name "CASE/PACKAGE") "0402")
      )
      (libsource (lib "CS_Library") (part "GCM033M8ED104KE07J"))
    )
    (comp (ref "C45")
      (value "10uF")
      (footprint "0805_DSP")
      (description "Capacitor:  10 µF ±10% 16V Ceramic Capacitor X8M 0805 (2012 Metric)")
      (fields
        (field (name "MANUFACTURER_PART_NUMBER") "GCM21BM8EE106KE08L")
        (field (name "MOUSER PART NUMBER") "81-GCM21BM8EE106KE8L")
        (field (name "VOLTAGE") "16V")
        (field (name "CASE/PACKAGE") "0805")
      )
      (libsource (lib "CS_Library") (part "GCM21BM8EE106KE08L"))
    )
    (comp (ref "C46")
      (value "0.1uF")
      (footprint "0402_DSP")
      (description "Capacitor: 0.1 µF ±10% 10V Ceramic Capacitor X8M 0201")
      (fields
        (field (name "MANUFACTURER_PART_NUMBER") "GCM033M8ED104KE07J")
        (field (name "MOUSER PART NUMBER") "81-GCM033M8ED104KE07")
        (field (name "VOLTAGE") "10V")
        (field (name "CASE/PACKAGE") "0402")
      )
      (libsource (lib "CS_Library") (part "GCM033M8ED104KE07J"))
    )
    (comp (ref "C47")
      (value "0.1uF")
      (footprint "0402_DSP")
      (description "Capacitor: 0.1 µF ±10% 10V Ceramic Capacitor X8M 0201")
      (fields
        (field (name "MANUFACTURER_PART_NUMBER") "GCM033M8ED104KE07J")
        (field (name "MOUSER PART NUMBER") "81-GCM033M8ED104KE07")
        (field (name "VOLTAGE") "10V")
        (field (name "CASE/PACKAGE") "0402")
      )
      (libsource (lib "CS_Library") (part "GCM033M8ED104KE07J"))
    )
    (comp (ref "C48")
      (value "1000pF")
      (footprint "0402_DSP")
      (description "Capacitor: 1000 pF ±10% 50V Ceramic Capacitor X8L 0402 (1005 Metric)")
      (fields
        (field (name "MANUFACTURER_PART_NUMBER") "GCM155L81H102KA37D")
        (field (name "MOUSER PART NUMBER") "81-GCM155L81H102KA7D")
        (field (name "CASE/PACKAGE") "0402")
        (field (name "VOLTAGE") "50V")
      )
      (libsource (lib "CS_Library") (part "GCM155L81H102KA37D"))
    )
    (comp (ref "C49")
      (value "0.1uF")
      (footprint "0402_DSP")
      (description "Capacitor: 0.1 µF ±10% 10V Ceramic Capacitor X8M 0201")
      (fields
        (field (name "MANUFACTURER_PART_NUMBER") "GCM033M8ED104KE07J")
        (field (name "MOUSER PART NUMBER") "81-GCM033M8ED104KE07")
        (field (name "VOLTAGE") "10V")
        (field (name "CASE/PACKAGE") "0402")
      )
      (libsource (lib "CS_Library") (part "GCM033M8ED104KE07J"))
    )
    (comp (ref "C50")
      (value "0.1uF")
      (footprint "0402_DSP")
      (description "Capacitor: 0.1 µF ±10% 10V Ceramic Capacitor X8M 0201")
      (fields
        (field (name "MANUFACTURER_PART_NUMBER") "GCM033M8ED104KE07J")
        (field (name "MOUSER PART NUMBER") "81-GCM033M8ED104KE07")
        (field (name "VOLTAGE") "10V")
        (field (name "CASE/PACKAGE") "0402")
      )
      (libsource (lib "CS_Library") (part "GCM033M8ED104KE07J"))
    )
    (comp (ref "C52")
      (value "0.1uF")
      (footprint "CS_Library:0402_DSP")
      (description "Capacitor: 0.1 µF ±10% 25V Ceramic Capacitor X8L 0402 (1005 Metric)")
      (fields
        (field (name "MANUFACTURER_PART_NUMBER") "GCM155L81E104KE02D")
        (field (name "MOUSER PART NUMBER") "81-GCM155L81E104KE2D")
        (field (name "VOLTAGE") "25V")
        (field (name "CASE/PACKAGE") "0402")
      )
      (libsource (lib "CS_Library") (part "GCM155L81E104KE02D"))
    )
    (comp (ref "C53")
      (value "1uF")
      (footprint "0603_DSP")
      (description "Capacitor: 1 µF ±10% 16V Ceramic Capacitor X8L 0603")
      (fields
        (field (name "MANUFACTURER_PART_NUMBER") "GCG188L8EE105KA07D")
        (field (name "MOUSER PART NUMBER") "81-GCG188L8EE105KA7D")
        (field (name "CASE/PACKAGE") "0603")
        (field (name "VOLTAGE") "16V")
      )
      (libsource (lib "CS_Library") (part "GCG188L8EE105KA07D"))
    )
    (comp (ref "C54")
      (value "0.1uF")
      (footprint "0402_DSP")
      (description "Capacitor: 0.1 µF ±10% 10V Ceramic Capacitor X8M 0201")
      (fields
        (field (name "MANUFACTURER_PART_NUMBER") "GCM033M8ED104KE07J")
        (field (name "MOUSER PART NUMBER") "81-GCM033M8ED104KE07")
        (field (name "VOLTAGE") "10V")
        (field (name "CASE/PACKAGE") "0402")
      )
      (libsource (lib "CS_Library") (part "GCM033M8ED104KE07J"))
    )
    (comp (ref "C55")
      (value "0603")
      (footprint "FP-GCG188-0_2-IPC_A")
      (fields
        (field (name "MANUFACTURER_PART_NUMBER") "GCG188L8EE105KA07D")
        (field (name "ALTIUM_VALUE") "1uF")
        (field (name "VOLTAGE") "16V")
      )
      (libsource (lib "Altium Content Vault") (part "02cd4be3c70576c341d710602a673aa"))
    )
    (comp (ref "C56")
      (value "0.1uF")
      (footprint "0402_DSP")
      (description "Capacitor: 0.1 µF ±10% 10V Ceramic Capacitor X8M 0201")
      (fields
        (field (name "MANUFACTURER_PART_NUMBER") "GCM033M8ED104KE07J")
        (field (name "MOUSER PART NUMBER") "81-GCM033M8ED104KE07")
        (field (name "VOLTAGE") "10V")
        (field (name "CASE/PACKAGE") "0402")
      )
      (libsource (lib "CS_Library") (part "GCM033M8ED104KE07J"))
    )
    (comp (ref "C57")
      (value "0.1uF")
      (footprint "0402_DSP")
      (description "Capacitor: 0.1 µF ±10% 10V Ceramic Capacitor X8M 0201")
      (fields
        (field (name "MANUFACTURER_PART_NUMBER") "GCM033M8ED104KE07J")
        (field (name "MOUSER PART NUMBER") "81-GCM033M8ED104KE07")
        (field (name "VOLTAGE") "10V")
        (field (name "CASE/PACKAGE") "0402")
      )
      (libsource (lib "CS_Library") (part "GCM033M8ED104KE07J"))
    )
    (comp (ref "C58")
      (value "0.1uF")
      (footprint "0402_DSP")
      (description "Capacitor: 0.1 µF ±10% 10V Ceramic Capacitor X8M 0201")
      (fields
        (field (name "MANUFACTURER_PART_NUMBER") "GCM033M8ED104KE07J")
        (field (name "MOUSER PART NUMBER") "81-GCM033M8ED104KE07")
        (field (name "VOLTAGE") "10V")
        (field (name "CASE/PACKAGE") "0402")
      )
      (libsource (lib "CS_Library") (part "GCM033M8ED104KE07J"))
    )
    (comp (ref "C60")
      (value "0.1uF")
      (footprint "0402_DSP")
      (description "Capacitor: 0.1 µF ±10% 10V Ceramic Capacitor X8M 0201")
      (fields
        (field (name "MANUFACTURER_PART_NUMBER") "GCM033M8ED104KE07J")
        (field (name "MOUSER PART NUMBER") "81-GCM033M8ED104KE07")
        (field (name "VOLTAGE") "10V")
        (field (name "CASE/PACKAGE") "0402")
      )
      (libsource (lib "CS_Library") (part "GCM033M8ED104KE07J"))
    )
    (comp (ref "C61")
      (value "0.1uF")
      (footprint "0402_DSP")
      (description "Capacitor: 0.1 µF ±10% 10V Ceramic Capacitor X8M 0201")
      (fields
        (field (name "MANUFACTURER_PART_NUMBER") "GCM033M8ED104KE07J")
        (field (name "MOUSER PART NUMBER") "81-GCM033M8ED104KE07")
        (field (name "VOLTAGE") "10V")
        (field (name "CASE/PACKAGE") "0402")
      )
      (libsource (lib "CS_Library") (part "GCM033M8ED104KE07J"))
    )
    (comp (ref "C62")
      (value "1000pF")
      (footprint "0402_DSP")
      (description "Capacitor: 1000 pF ±10% 50V Ceramic Capacitor X8L 0402 (1005 Metric)")
      (fields
        (field (name "MANUFACTURER_PART_NUMBER") "GCM155L81H102KA37D")
        (field (name "MOUSER PART NUMBER") "81-GCM155L81H102KA7D")
        (field (name "CASE/PACKAGE") "0402")
        (field (name "VOLTAGE") "50V")
      )
      (libsource (lib "CS_Library") (part "GCM155L81H102KA37D"))
    )
    (comp (ref "C65")
      (value "0.1uF")
      (footprint "0402_DSP")
      (description "Capacitor: 0.1 µF ±10% 10V Ceramic Capacitor X8M 0201")
      (fields
        (field (name "MANUFACTURER_PART_NUMBER") "GCM033M8ED104KE07J")
        (field (name "MOUSER PART NUMBER") "81-GCM033M8ED104KE07")
        (field (name "VOLTAGE") "10V")
        (field (name "CASE/PACKAGE") "0402")
      )
      (libsource (lib "CS_Library") (part "GCM033M8ED104KE07J"))
    )
    (comp (ref "C67")
      (value "1000pF")
      (footprint "0402_DSP")
      (description "Capacitor: 1000 pF ±10% 50V Ceramic Capacitor X8L 0402 (1005 Metric)")
      (fields
        (field (name "MANUFACTURER_PART_NUMBER") "GCM155L81H102KA37D")
        (field (name "MOUSER PART NUMBER") "81-GCM155L81H102KA7D")
        (field (name "CASE/PACKAGE") "0402")
        (field (name "VOLTAGE") "50V")
      )
      (libsource (lib "CS_Library") (part "GCM155L81H102KA37D"))
    )
    (comp (ref "C68")
      (value "0.1uF")
      (footprint "0402_DSP")
      (description "Capacitor: 0.1 µF ±10% 10V Ceramic Capacitor X8M 0201")
      (fields
        (field (name "MANUFACTURER_PART_NUMBER") "GCM033M8ED104KE07J")
        (field (name "MOUSER PART NUMBER") "81-GCM033M8ED104KE07")
        (field (name "VOLTAGE") "10V")
        (field (name "CASE/PACKAGE") "0402")
      )
      (libsource (lib "CS_Library") (part "GCM033M8ED104KE07J"))
    )
    (comp (ref "C69")
      (value "10uF")
      (footprint "0805_DSP")
      (description "Capacitor:  10 µF ±10% 16V Ceramic Capacitor X8M 0805 (2012 Metric)")
      (fields
        (field (name "MANUFACTURER_PART_NUMBER") "GCM21BM8EE106KE08L")
        (field (name "MOUSER PART NUMBER") "81-GCM21BM8EE106KE8L")
        (field (name "VOLTAGE") "16V")
        (field (name "CASE/PACKAGE") "0805")
      )
      (libsource (lib "CS_Library") (part "GCM21BM8EE106KE08L"))
    )
    (comp (ref "C70")
      (value "0.1uF")
      (footprint "0402_DSP")
      (description "Capacitor: 0.1 µF ±10% 10V Ceramic Capacitor X8M 0201")
      (fields
        (field (name "MANUFACTURER_PART_NUMBER") "GCM033M8ED104KE07J")
        (field (name "MOUSER PART NUMBER") "81-GCM033M8ED104KE07")
        (field (name "VOLTAGE") "10V")
        (field (name "CASE/PACKAGE") "0402")
      )
      (libsource (lib "CS_Library") (part "GCM033M8ED104KE07J"))
    )
    (comp (ref "C71")
      (value "0.1uF")
      (footprint "0402_DSP")
      (description "Capacitor: 0.1 µF ±10% 10V Ceramic Capacitor X8M 0201")
      (fields
        (field (name "MANUFACTURER_PART_NUMBER") "GCM033M8ED104KE07J")
        (field (name "MOUSER PART NUMBER") "81-GCM033M8ED104KE07")
        (field (name "VOLTAGE") "10V")
        (field (name "CASE/PACKAGE") "0402")
      )
      (libsource (lib "CS_Library") (part "GCM033M8ED104KE07J"))
    )
    (comp (ref "C73")
      (value "0.1uF")
      (footprint "0402_DSP")
      (description "Capacitor: 0.1 µF ±10% 10V Ceramic Capacitor X8M 0201")
      (fields
        (field (name "MANUFACTURER_PART_NUMBER") "GCM033M8ED104KE07J")
        (field (name "MOUSER PART NUMBER") "81-GCM033M8ED104KE07")
        (field (name "VOLTAGE") "10V")
        (field (name "CASE/PACKAGE") "0402")
      )
      (libsource (lib "CS_Library") (part "GCM033M8ED104KE07J"))
    )
    (comp (ref "C75")
      (value "0.1uF")
      (footprint "0402_DSP")
      (description "Capacitor: 0.1 µF ±10% 10V Ceramic Capacitor X8M 0201")
      (fields
        (field (name "MANUFACTURER_PART_NUMBER") "GCM033M8ED104KE07J")
        (field (name "MOUSER PART NUMBER") "81-GCM033M8ED104KE07")
        (field (name "VOLTAGE") "10V")
        (field (name "CASE/PACKAGE") "0402")
      )
      (libsource (lib "CS_Library") (part "GCM033M8ED104KE07J"))
    )
    (comp (ref "C77")
      (value "1000pF")
      (footprint "0402_DSP")
      (description "Capacitor: 1000 pF ±10% 50V Ceramic Capacitor X8L 0402 (1005 Metric)")
      (fields
        (field (name "MANUFACTURER_PART_NUMBER") "GCM155L81H102KA37D")
        (field (name "MOUSER PART NUMBER") "81-GCM155L81H102KA7D")
        (field (name "CASE/PACKAGE") "0402")
        (field (name "VOLTAGE") "50V")
      )
      (libsource (lib "CS_Library") (part "GCM155L81H102KA37D"))
    )
    (comp (ref "C79")
      (value "0.1uF")
      (footprint "0402_DSP")
      (description "Capacitor: 0.1 µF ±10% 10V Ceramic Capacitor X8M 0201")
      (fields
        (field (name "MANUFACTURER_PART_NUMBER") "GCM033M8ED104KE07J")
        (field (name "MOUSER PART NUMBER") "81-GCM033M8ED104KE07")
        (field (name "VOLTAGE") "10V")
        (field (name "CASE/PACKAGE") "0402")
      )
      (libsource (lib "CS_Library") (part "GCM033M8ED104KE07J"))
    )
    (comp (ref "C80")
      (value "0.1uF")
      (footprint "0402_DSP")
      (description "Capacitor: 0.1 µF ±10% 10V Ceramic Capacitor X8M 0201")
      (fields
        (field (name "MANUFACTURER_PART_NUMBER") "GCM033M8ED104KE07J")
        (field (name "MOUSER PART NUMBER") "81-GCM033M8ED104KE07")
        (field (name "VOLTAGE") "10V")
        (field (name "CASE/PACKAGE") "0402")
      )
      (libsource (lib "CS_Library") (part "GCM033M8ED104KE07J"))
    )
    (comp (ref "C81")
      (value "0.1uF")
      (footprint "0402_DSP")
      (description "Capacitor: 0.1 µF ±10% 10V Ceramic Capacitor X8M 0201")
      (fields
        (field (name "MANUFACTURER_PART_NUMBER") "GCM033M8ED104KE07J")
        (field (name "MOUSER PART NUMBER") "81-GCM033M8ED104KE07")
        (field (name "VOLTAGE") "10V")
        (field (name "CASE/PACKAGE") "0402")
      )
      (libsource (lib "CS_Library") (part "GCM033M8ED104KE07J"))
    )
    (comp (ref "C82")
      (value "0.1uF")
      (footprint "0402_DSP")
      (description "Capacitor: 0.1 µF ±10% 10V Ceramic Capacitor X8M 0201")
      (fields
        (field (name "MANUFACTURER_PART_NUMBER") "GCM033M8ED104KE07J")
        (field (name "MOUSER PART NUMBER") "81-GCM033M8ED104KE07")
        (field (name "VOLTAGE") "10V")
        (field (name "CASE/PACKAGE") "0402")
      )
      (libsource (lib "CS_Library") (part "GCM033M8ED104KE07J"))
    )
    (comp (ref "C83")
      (value "1000pF")
      (footprint "0402_DSP")
      (description "Capacitor: 1000 pF ±10% 50V Ceramic Capacitor X8L 0402 (1005 Metric)")
      (fields
        (field (name "MANUFACTURER_PART_NUMBER") "GCM155L81H102KA37D")
        (field (name "MOUSER PART NUMBER") "81-GCM155L81H102KA7D")
        (field (name "CASE/PACKAGE") "0402")
        (field (name "VOLTAGE") "50V")
      )
      (libsource (lib "CS_Library") (part "GCM155L81H102KA37D"))
    )
    (comp (ref "C84")
      (value "10uF")
      (footprint "CS_Library:CAPC2012X140N")
      (description "Capacitor:  10 µF ±10% 16V Ceramic Capacitor X8M 0805 (2012 Metric)")
      (fields
        (field (name "MANUFACTURER_PART_NUMBER") "GCM21BM8EE106KE08L")
        (field (name "MOUSER PART NUMBER") "81-GCM21BM8EE106KE8L")
        (field (name "VOLTAGE") "16V")
        (field (name "CASE/PACKAGE") "0805")
      )
      (libsource (lib "CS_Library") (part "GCM21BM8EE106KE08L"))
    )
    (comp (ref "C85")
      (value "0.1uF")
      (footprint "0402_DSP")
      (description "Capacitor: 0.1 µF ±10% 10V Ceramic Capacitor X8M 0201")
      (fields
        (field (name "MANUFACTURER_PART_NUMBER") "GCM033M8ED104KE07J")
        (field (name "MOUSER PART NUMBER") "81-GCM033M8ED104KE07")
        (field (name "VOLTAGE") "10V")
        (field (name "CASE/PACKAGE") "0402")
      )
      (libsource (lib "CS_Library") (part "GCM033M8ED104KE07J"))
    )
    (comp (ref "C86")
      (value "10uF")
      (footprint "CS_Library:CAPC2012X140N")
      (description "Capacitor:  10 µF ±10% 16V Ceramic Capacitor X8M 0805 (2012 Metric)")
      (fields
        (field (name "MANUFACTURER_PART_NUMBER") "GCM21BM8EE106KE08L")
        (field (name "MOUSER PART NUMBER") "81-GCM21BM8EE106KE8L")
        (field (name "VOLTAGE") "16V")
        (field (name "CASE/PACKAGE") "0805")
      )
      (libsource (lib "CS_Library") (part "GCM21BM8EE106KE08L"))
    )
    (comp (ref "C87")
      (value "0.1uF")
      (footprint "0402_DSP")
      (description "Capacitor: 0.1 µF ±10% 10V Ceramic Capacitor X8M 0201")
      (fields
        (field (name "MANUFACTURER_PART_NUMBER") "GCM033M8ED104KE07J")
        (field (name "MOUSER PART NUMBER") "81-GCM033M8ED104KE07")
        (field (name "VOLTAGE") "10V")
        (field (name "CASE/PACKAGE") "0402")
      )
      (libsource (lib "CS_Library") (part "GCM033M8ED104KE07J"))
    )
    (comp (ref "C88")
      (value "0.1uF")
      (footprint "0402_DSP")
      (description "Capacitor: 0.1 µF ±10% 10V Ceramic Capacitor X8M 0201")
      (fields
        (field (name "MANUFACTURER_PART_NUMBER") "GCM033M8ED104KE07J")
        (field (name "MOUSER PART NUMBER") "81-GCM033M8ED104KE07")
        (field (name "VOLTAGE") "10V")
        (field (name "CASE/PACKAGE") "0402")
      )
      (libsource (lib "CS_Library") (part "GCM033M8ED104KE07J"))
    )
    (comp (ref "C89")
      (value "0.1uF")
      (footprint "0402_DSP")
      (description "Capacitor: 0.1 µF ±10% 10V Ceramic Capacitor X8M 0201")
      (fields
        (field (name "MANUFACTURER_PART_NUMBER") "GCM033M8ED104KE07J")
        (field (name "MOUSER PART NUMBER") "81-GCM033M8ED104KE07")
        (field (name "VOLTAGE") "10V")
        (field (name "CASE/PACKAGE") "0402")
      )
      (libsource (lib "CS_Library") (part "GCM033M8ED104KE07J"))
    )
    (comp (ref "C93")
      (value "1000pF")
      (footprint "0402_DSP")
      (description "Capacitor: 1000 pF ±10% 50V Ceramic Capacitor X8L 0402 (1005 Metric)")
      (fields
        (field (name "MANUFACTURER_PART_NUMBER") "GCM155L81H102KA37D")
        (field (name "MOUSER PART NUMBER") "81-GCM155L81H102KA7D")
        (field (name "CASE/PACKAGE") "0402")
        (field (name "VOLTAGE") "50V")
      )
      (libsource (lib "CS_Library") (part "GCM155L81H102KA37D"))
    )
    (comp (ref "C94")
      (value "0.1uF")
      (footprint "0402_DSP")
      (description "Capacitor: 0.1 µF ±10% 10V Ceramic Capacitor X8M 0201")
      (fields
        (field (name "MANUFACTURER_PART_NUMBER") "GCM033M8ED104KE07J")
        (field (name "MOUSER PART NUMBER") "81-GCM033M8ED104KE07")
        (field (name "VOLTAGE") "10V")
        (field (name "CASE/PACKAGE") "0402")
      )
      (libsource (lib "CS_Library") (part "GCM033M8ED104KE07J"))
    )
    (comp (ref "C95")
      (value "0.1uF")
      (footprint "0402_DSP")
      (description "Capacitor: 0.1 µF ±10% 10V Ceramic Capacitor X8M 0201")
      (fields
        (field (name "MANUFACTURER_PART_NUMBER") "GCM033M8ED104KE07J")
        (field (name "MOUSER PART NUMBER") "81-GCM033M8ED104KE07")
        (field (name "VOLTAGE") "10V")
        (field (name "CASE/PACKAGE") "0402")
      )
      (libsource (lib "CS_Library") (part "GCM033M8ED104KE07J"))
    )
    (comp (ref "C96")
      (value "0.1uF")
      (footprint "0402_DSP")
      (description "Capacitor: 0.1 µF ±10% 10V Ceramic Capacitor X8M 0201")
      (fields
        (field (name "MANUFACTURER_PART_NUMBER") "GCM033M8ED104KE07J")
        (field (name "MOUSER PART NUMBER") "81-GCM033M8ED104KE07")
        (field (name "VOLTAGE") "10V")
        (field (name "CASE/PACKAGE") "0402")
      )
      (libsource (lib "CS_Library") (part "GCM033M8ED104KE07J"))
    )
    (comp (ref "C97")
      (value "0.1uF")
      (footprint "0402_DSP")
      (description "Capacitor: 0.1 µF ±10% 10V Ceramic Capacitor X8M 0201")
      (fields
        (field (name "MANUFACTURER_PART_NUMBER") "GCM033M8ED104KE07J")
        (field (name "MOUSER PART NUMBER") "81-GCM033M8ED104KE07")
        (field (name "VOLTAGE") "10V")
        (field (name "CASE/PACKAGE") "0402")
      )
      (libsource (lib "CS_Library") (part "GCM033M8ED104KE07J"))
    )
    (comp (ref "C99")
      (value "0.1uF")
      (footprint "0402_DSP")
      (description "Capacitor: 0.1 µF ±10% 10V Ceramic Capacitor X8M 0201")
      (fields
        (field (name "MANUFACTURER_PART_NUMBER") "GCM033M8ED104KE07J")
        (field (name "MOUSER PART NUMBER") "81-GCM033M8ED104KE07")
        (field (name "VOLTAGE") "10V")
        (field (name "CASE/PACKAGE") "0402")
      )
      (libsource (lib "CS_Library") (part "GCM033M8ED104KE07J"))
    )
    (comp (ref "C100")
      (value "0.1uF")
      (footprint "0402_DSP")
      (description "Capacitor: 0.1 µF ±10% 10V Ceramic Capacitor X8M 0201")
      (fields
        (field (name "MANUFACTURER_PART_NUMBER") "GCM033M8ED104KE07J")
        (field (name "MOUSER PART NUMBER") "81-GCM033M8ED104KE07")
        (field (name "VOLTAGE") "10V")
        (field (name "CASE/PACKAGE") "0402")
      )
      (libsource (lib "CS_Library") (part "GCM033M8ED104KE07J"))
    )
    (comp (ref "C101")
      (value "0.1uF")
      (footprint "0402_DSP")
      (description "Capacitor: 0.1 µF ±10% 10V Ceramic Capacitor X8M 0201")
      (fields
        (field (name "MANUFACTURER_PART_NUMBER") "GCM033M8ED104KE07J")
        (field (name "MOUSER PART NUMBER") "81-GCM033M8ED104KE07")
        (field (name "VOLTAGE") "10V")
        (field (name "CASE/PACKAGE") "0402")
      )
      (libsource (lib "CS_Library") (part "GCM033M8ED104KE07J"))
    )
    (comp (ref "C102")
      (value "0.1uF")
      (footprint "0402_DSP")
      (description "Capacitor: 0.1 µF ±10% 10V Ceramic Capacitor X8M 0201")
      (fields
        (field (name "MANUFACTURER_PART_NUMBER") "GCM033M8ED104KE07J")
        (field (name "MOUSER PART NUMBER") "81-GCM033M8ED104KE07")
        (field (name "VOLTAGE") "10V")
        (field (name "CASE/PACKAGE") "0402")
      )
      (libsource (lib "CS_Library") (part "GCM033M8ED104KE07J"))
    )
    (comp (ref "C103")
      (value "0.1uF")
      (footprint "0402_DSP")
      (description "Capacitor: 0.1 µF ±10% 10V Ceramic Capacitor X8M 0201")
      (fields
        (field (name "MANUFACTURER_PART_NUMBER") "GCM033M8ED104KE07J")
        (field (name "MOUSER PART NUMBER") "81-GCM033M8ED104KE07")
        (field (name "VOLTAGE") "10V")
        (field (name "CASE/PACKAGE") "0402")
      )
      (libsource (lib "CS_Library") (part "GCM033M8ED104KE07J"))
    )
    (comp (ref "C104")
      (value "0.1uF")
      (footprint "0402_DSP")
      (description "Capacitor: 0.1 µF ±10% 10V Ceramic Capacitor X8M 0201")
      (fields
        (field (name "MANUFACTURER_PART_NUMBER") "GCM033M8ED104KE07J")
        (field (name "MOUSER PART NUMBER") "81-GCM033M8ED104KE07")
        (field (name "VOLTAGE") "10V")
        (field (name "CASE/PACKAGE") "0402")
      )
      (libsource (lib "CS_Library") (part "GCM033M8ED104KE07J"))
    )
    (comp (ref "C105")
      (value "0.1uF")
      (footprint "0402_DSP")
      (description "Capacitor: 0.1 µF ±10% 10V Ceramic Capacitor X8M 0201")
      (fields
        (field (name "MANUFACTURER_PART_NUMBER") "GCM033M8ED104KE07J")
        (field (name "MOUSER PART NUMBER") "81-GCM033M8ED104KE07")
        (field (name "VOLTAGE") "10V")
        (field (name "CASE/PACKAGE") "0402")
      )
      (libsource (lib "CS_Library") (part "GCM033M8ED104KE07J"))
    )
    (comp (ref "C106")
      (value "0.1uF")
      (footprint "0402_DSP")
      (description "Capacitor: 0.1 µF ±10% 10V Ceramic Capacitor X8M 0201")
      (fields
        (field (name "MANUFACTURER_PART_NUMBER") "GCM033M8ED104KE07J")
        (field (name "MOUSER PART NUMBER") "81-GCM033M8ED104KE07")
        (field (name "VOLTAGE") "10V")
        (field (name "CASE/PACKAGE") "0402")
      )
      (libsource (lib "CS_Library") (part "GCM033M8ED104KE07J"))
    )
    (comp (ref "C107")
      (value "0.1uF")
      (footprint "0402_DSP")
      (description "Capacitor: 0.1 µF ±10% 10V Ceramic Capacitor X8M 0201")
      (fields
        (field (name "MANUFACTURER_PART_NUMBER") "GCM033M8ED104KE07J")
        (field (name "MOUSER PART NUMBER") "81-GCM033M8ED104KE07")
        (field (name "VOLTAGE") "10V")
        (field (name "CASE/PACKAGE") "0402")
      )
      (libsource (lib "CS_Library") (part "GCM033M8ED104KE07J"))
    )
    (comp (ref "C108")
      (value "0.1uF")
      (footprint "0402_DSP")
      (description "Capacitor: 0.1 µF ±10% 10V Ceramic Capacitor X8M 0201")
      (fields
        (field (name "MANUFACTURER_PART_NUMBER") "GCM033M8ED104KE07J")
        (field (name "MOUSER PART NUMBER") "81-GCM033M8ED104KE07")
        (field (name "VOLTAGE") "10V")
        (field (name "CASE/PACKAGE") "0402")
      )
      (libsource (lib "CS_Library") (part "GCM033M8ED104KE07J"))
    )
    (comp (ref "C109")
      (value "0.1uF")
      (footprint "0402_DSP")
      (description "Capacitor: 0.1 µF ±10% 10V Ceramic Capacitor X8M 0201")
      (fields
        (field (name "MANUFACTURER_PART_NUMBER") "GCM033M8ED104KE07J")
        (field (name "MOUSER PART NUMBER") "81-GCM033M8ED104KE07")
        (field (name "VOLTAGE") "10V")
        (field (name "CASE/PACKAGE") "0402")
      )
      (libsource (lib "CS_Library") (part "GCM033M8ED104KE07J"))
    )
    (comp (ref "C110")
      (value "0.1uF")
      (footprint "0402_DSP")
      (description "Capacitor: 0.1 µF ±10% 10V Ceramic Capacitor X8M 0201")
      (fields
        (field (name "MANUFACTURER_PART_NUMBER") "GCM033M8ED104KE07J")
        (field (name "MOUSER PART NUMBER") "81-GCM033M8ED104KE07")
        (field (name "VOLTAGE") "10V")
        (field (name "CASE/PACKAGE") "0402")
      )
      (libsource (lib "CS_Library") (part "GCM033M8ED104KE07J"))
    )
    (comp (ref "C111")
      (value "0.1uF")
      (footprint "0402_DSP")
      (description "Capacitor: 0.1 µF ±10% 10V Ceramic Capacitor X8M 0201")
      (fields
        (field (name "MANUFACTURER_PART_NUMBER") "GCM033M8ED104KE07J")
        (field (name "MOUSER PART NUMBER") "81-GCM033M8ED104KE07")
        (field (name "VOLTAGE") "10V")
        (field (name "CASE/PACKAGE") "0402")
      )
      (libsource (lib "CS_Library") (part "GCM033M8ED104KE07J"))
    )
    (comp (ref "C112")
      (value "0.1uF")
      (footprint "0402_DSP")
      (description "Capacitor: 0.1 µF ±10% 10V Ceramic Capacitor X8M 0201")
      (fields
        (field (name "MANUFACTURER_PART_NUMBER") "GCM033M8ED104KE07J")
        (field (name "MOUSER PART NUMBER") "81-GCM033M8ED104KE07")
        (field (name "VOLTAGE") "10V")
        (field (name "CASE/PACKAGE") "0402")
      )
      (libsource (lib "CS_Library") (part "GCM033M8ED104KE07J"))
    )
    (comp (ref "C113")
      (value "0.1uF")
      (footprint "0402_DSP")
      (description "Capacitor: 0.1 µF ±10% 10V Ceramic Capacitor X8M 0201")
      (fields
        (field (name "MANUFACTURER_PART_NUMBER") "GCM033M8ED104KE07J")
        (field (name "MOUSER PART NUMBER") "81-GCM033M8ED104KE07")
        (field (name "VOLTAGE") "10V")
        (field (name "CASE/PACKAGE") "0402")
      )
      (libsource (lib "CS_Library") (part "GCM033M8ED104KE07J"))
    )
    (comp (ref "C114")
      (value "0.1uF")
      (footprint "0402_DSP")
      (description "Capacitor: 0.1 µF ±10% 10V Ceramic Capacitor X8M 0201")
      (fields
        (field (name "MANUFACTURER_PART_NUMBER") "GCM033M8ED104KE07J")
        (field (name "MOUSER PART NUMBER") "81-GCM033M8ED104KE07")
        (field (name "VOLTAGE") "10V")
        (field (name "CASE/PACKAGE") "0402")
      )
      (libsource (lib "CS_Library") (part "GCM033M8ED104KE07J"))
    )
    (comp (ref "C115")
      (value "0.1uF")
      (footprint "0402_DSP")
      (description "Capacitor: 0.1 µF ±10% 10V Ceramic Capacitor X8M 0201")
      (fields
        (field (name "MANUFACTURER_PART_NUMBER") "GCM033M8ED104KE07J")
        (field (name "MOUSER PART NUMBER") "81-GCM033M8ED104KE07")
        (field (name "VOLTAGE") "10V")
        (field (name "CASE/PACKAGE") "0402")
      )
      (libsource (lib "CS_Library") (part "GCM033M8ED104KE07J"))
    )
    (comp (ref "C116")
      (value "0.1uF")
      (footprint "0402_DSP")
      (description "Capacitor: 0.1 µF ±10% 10V Ceramic Capacitor X8M 0201")
      (fields
        (field (name "MANUFACTURER_PART_NUMBER") "GCM033M8ED104KE07J")
        (field (name "MOUSER PART NUMBER") "81-GCM033M8ED104KE07")
        (field (name "VOLTAGE") "10V")
        (field (name "CASE/PACKAGE") "0402")
      )
      (libsource (lib "CS_Library") (part "GCM033M8ED104KE07J"))
    )
    (comp (ref "C117")
      (value "1000pF")
      (footprint "0402_DSP")
      (description "Capacitor: 1000 pF ±10% 50V Ceramic Capacitor X8L 0402 (1005 Metric)")
      (fields
        (field (name "MANUFACTURER_PART_NUMBER") "GCM155L81H102KA37D")
        (field (name "MOUSER PART NUMBER") "81-GCM155L81H102KA7D")
        (field (name "CASE/PACKAGE") "0402")
        (field (name "VOLTAGE") "50V")
      )
      (libsource (lib "CS_Library") (part "GCM155L81H102KA37D"))
    )
    (comp (ref "C128")
      (value "1000pF")
      (footprint "0402_DSP")
      (description "Capacitor: 1000 pF ±10% 50V Ceramic Capacitor X8L 0402 (1005 Metric)")
      (fields
        (field (name "MANUFACTURER_PART_NUMBER") "GCM155L81H102KA37D")
        (field (name "MOUSER PART NUMBER") "81-GCM155L81H102KA7D")
        (field (name "CASE/PACKAGE") "0402")
        (field (name "VOLTAGE") "50V")
      )
      (libsource (lib "CS_Library") (part "GCM155L81H102KA37D"))
    )
    (comp (ref "C129")
      (value "1000pF")
      (footprint "0402_DSP")
      (description "Capacitor: 1000 pF ±10% 50V Ceramic Capacitor X8L 0402 (1005 Metric)")
      (fields
        (field (name "MANUFACTURER_PART_NUMBER") "GCM155L81H102KA37D")
        (field (name "MOUSER PART NUMBER") "81-GCM155L81H102KA7D")
        (field (name "CASE/PACKAGE") "0402")
        (field (name "VOLTAGE") "50V")
      )
      (libsource (lib "CS_Library") (part "GCM155L81H102KA37D"))
    )
    (comp (ref "C141")
      (value "1000pF")
      (footprint "0402_DSP")
      (description "Capacitor: 1000 pF ±10% 50V Ceramic Capacitor X8L 0402 (1005 Metric)")
      (fields
        (field (name "MANUFACTURER_PART_NUMBER") "GCM155L81H102KA37D")
        (field (name "MOUSER PART NUMBER") "81-GCM155L81H102KA7D")
        (field (name "CASE/PACKAGE") "0402")
        (field (name "VOLTAGE") "50V")
      )
      (libsource (lib "CS_Library") (part "GCM155L81H102KA37D"))
    )
    (comp (ref "D1")
      (value "BAS40-07,215")
      (footprint "CS_Library:BAS4007215")
      (description "Schottky Diode")
      (fields (field (name "MOUSER PART NUMBER") "771-BAS40-07215"))
      (libsource (lib "*") (part "BAS40-07,215"))
    )
    (comp (ref "D2")
      (value "PESD2CANFD24L-TR")
      (footprint "CS_Library:SOT95P230X110-3N")
      (description "Diode")
      (fields (field (name "MOUSER PART NUMBER") "771-PESD2CANFD24L-TR") (field (name "CASE/PACKAGE") "*"))
      (libsource (lib "*") (part "PESD2CANFD24L-TR"))
    )
    (comp (ref "D3")
      (value "DIODE SCHOTTKY 30V 100MA VMN2")
      (footprint "CS_Library:RB521CS30FHT2RA")
      (description "Diode: Schottky Diode 30 V 100mA Surface Mount VMN2 (SOD-923)")
      (fields
        (field (name "MANUFACTURER_PART_NUMBER") "RB521CS-30FHT2RA")
        (field (name "MOUSER PART NUMBER") "755-RB521CS-30FHT2RA")
        (field (name "VOLTAGE") "30V")
        (field (name "CURRENT") "100mA")
      )
      (libsource (lib "CS_Library") (part "RB521CS-30FHT2RA"))
    )
    (comp (ref "D4")
      (value "DIODE SCHOTTKY 30V 100MA VMN2")
      (footprint "CS_Library:RB521CS30FHT2RA")
      (description "Diode: Schottky Diode 30 V 100mA Surface Mount VMN2 (SOD-923)")
      (fields
        (field (name "MANUFACTURER_PART_NUMBER") "RB521CS-30FHT2RA")
        (field (name "MOUSER PART NUMBER") "755-RB521CS-30FHT2RA")
        (field (name "VOLTAGE") "30V")
        (field (name "CURRENT") "100mA")
      )
      (libsource (lib "CS_Library") (part "RB521CS-30FHT2RA"))
    )
    (comp (ref "D5")
      (value "TS4148 RYG")
      (footprint "FP-TS4148_RYG-MFG")
      (description "Rectifier Diode Switching 75V 0.15A 4ns 2-Pin Case 0805(2012Metric) T/R")
      (fields (field (name "CASE/PACKAGE") "*"))
      (libsource (lib "Altium Content Vault") (part "d7152d700b627762746794eb795d46e"))
    )
    (comp (ref "D6")
      (value "TS4148 RYG")
      (footprint "FP-TS4148_RYG-MFG")
      (description "Rectifier Diode Switching 75V 0.15A 4ns 2-Pin Case 0805(2012Metric) T/R")
      (fields (field (name "CASE/PACKAGE") "*"))
      (libsource (lib "Altium Content Vault") (part "d7152d700b627762746794eb795d46e"))
    )
    (comp (ref "D7")
      (value "DIODE SCHOTTKY 30V 100MA VMN2")
      (footprint "CS_Library:RB521CS30FHT2RA")
      (description "Diode: Schottky Diode 30 V 100mA Surface Mount VMN2 (SOD-923)")
      (fields
        (field (name "MANUFACTURER_PART_NUMBER") "RB521CS-30FHT2RA")
        (field (name "MOUSER PART NUMBER") "755-RB521CS-30FHT2RA")
        (field (name "VOLTAGE") "30V")
        (field (name "CURRENT") "100mA")
      )
      (libsource (lib "CS_Library") (part "RB521CS-30FHT2RA"))
    )
    (comp (ref "F1")
      (value "2A")
      (footprint "0402_DSP")
      (description "Fuse")
      (fields
        (field (name "MANUFACTURER_PART_NUMBER") "SF-0402FP200-2")
        (field (name "CASE/PACKAGE") "0402")
        (field (name "PUBLISHER") "Altium Limited")
      )
      (libsource (lib "Miscellaneous Devices") (part "Fuse 2"))
    )
    (comp (ref "F2")
      (value "2A")
      (footprint "0402_DSP")
      (description "Fuse")
      (fields
        (field (name "MANUFACTURER_PART_NUMBER") "SF-0402FP200-2")
        (field (name "CASE/PACKAGE") "0402")
        (field (name "PUBLISHER") "Altium Limited")
      )
      (libsource (lib "Miscellaneous Devices") (part "Fuse 2"))
    )
    (comp (ref "F3")
      (value "2A")
      (footprint "0402_DSP")
      (description "Fuse")
      (fields
        (field (name "MANUFACTURER_PART_NUMBER") "SF-0402FP200-2")
        (field (name "CASE/PACKAGE") "0402")
        (field (name "PUBLISHER") "Altium Limited")
      )
      (libsource (lib "Miscellaneous Devices") (part "Fuse 2"))
    )
    (comp (ref "F4")
      (value "2A")
      (footprint "0402_DSP")
      (description "Fuse")
      (fields
        (field (name "MANUFACTURER_PART_NUMBER") "SF-0402FP200-2")
        (field (name "CASE/PACKAGE") "0402")
        (field (name "PUBLISHER") "Altium Limited")
      )
      (libsource (lib "Miscellaneous Devices") (part "Fuse 2"))
    )
    (comp (ref "F5")
      (value "2A")
      (footprint "0402_DSP")
      (description "Fuse")
      (fields
        (field (name "MANUFACTURER_PART_NUMBER") "SF-0402FP200-2")
        (field (name "CASE/PACKAGE") "0402")
        (field (name "PUBLISHER") "Altium Limited")
      )
      (libsource (lib "Miscellaneous Devices") (part "Fuse 2"))
    )
    (comp (ref "J1")
      (value "MDLM-15PCBRP-F222")
      (footprint "MDLM-15PCBRP-F222")
      (description "Connector")
      (libsource (lib "CS_Library") (part "MDLM-15PCBRP-F222"))
    )
    (comp (ref "J2")
      (value "~")
      (footprint "Wire24Awg2x1HPAD")
      (description "Socket")
      (fields (field (name "PUBLISHER") "Altium Limited"))
      (libsource (lib "Miscellaneous Connectors") (part "Socket"))
    )
    (comp (ref "J3")
      (value "TSW-105-05-T-S")
      (footprint "Surface_Mount_PIC_Prog")
      (description "Connector")
      (fields (field (name "MOUSER PART NUMBER") "200-TSW10505TS"))
      (libsource (lib "CS_Library") (part "TSW-105-05-T-S"))
    )
    (comp (ref "J4")
      (value "~")
      (footprint "Wire24Awg2x1HPAD")
      (description "Socket")
      (fields (field (name "PUBLISHER") "Altium Limited"))
      (libsource (lib "Miscellaneous Connectors") (part "Socket"))
    )
    (comp (ref "J5")
      (value "~")
      (footprint "Wire24Awg2x1HPAD")
      (description "Socket")
      (fields (field (name "PUBLISHER") "Altium Limited"))
      (libsource (lib "Miscellaneous Connectors") (part "Socket"))
    )
    (comp (ref "J6")
      (value "~")
      (footprint "Wire24Awg2x1HPAD")
      (description "Socket")
      (fields (field (name "PUBLISHER") "Altium Limited"))
      (libsource (lib "Miscellaneous Connectors") (part "Socket"))
    )
    (comp (ref "J7")
      (value "~")
      (footprint "Wire24Awg2x1HPAD")
      (description "Socket")
      (fields (field (name "PUBLISHER") "Altium Limited"))
      (libsource (lib "Miscellaneous Connectors") (part "Socket"))
    )
    (comp (ref "J8")
      (value "~")
      (footprint "Wire24Awg2x1HPAD")
      (description "Socket")
      (fields (field (name "PUBLISHER") "Altium Limited"))
      (libsource (lib "Miscellaneous Connectors") (part "Socket"))
    )
    (comp (ref "J9")
      (value "~")
      (footprint "Wire24Awg2x1HPAD")
      (description "Socket")
      (fields (field (name "PUBLISHER") "Altium Limited"))
      (libsource (lib "Miscellaneous Connectors") (part "Socket"))
    )
    (comp (ref "J10")
      (value "~")
      (footprint "Wire24Awg2x1HPAD")
      (description "Socket")
      (fields (field (name "PUBLISHER") "Altium Limited"))
      (libsource (lib "Miscellaneous Connectors") (part "Socket"))
    )
    (comp (ref "J11")
      (value "~")
      (footprint "Wire24Awg2x1HPAD")
      (description "Socket")
      (fields (field (name "PUBLISHER") "Altium Limited"))
      (libsource (lib "Miscellaneous Connectors") (part "Socket"))
    )
    (comp (ref "J12")
      (value "~")
      (footprint "Wire24Awg2x1HPAD")
      (description "Socket")
      (fields (field (name "PUBLISHER") "Altium Limited"))
      (libsource (lib "Miscellaneous Connectors") (part "Socket"))
    )
    (comp (ref "J13")
      (value "~")
      (footprint "Wire24Awg2x1HPAD")
      (description "Socket")
      (fields (field (name "PUBLISHER") "Altium Limited"))
      (libsource (lib "Miscellaneous Connectors") (part "Socket"))
    )
    (comp (ref "J14")
      (value "~")
      (footprint "Wire24Awg2x1HPAD")
      (description "Socket")
      (fields (field (name "PUBLISHER") "Altium Limited"))
      (libsource (lib "Miscellaneous Connectors") (part "Socket"))
    )
    (comp (ref "J15")
      (value "~")
      (footprint "Wire24Awg2x1HPAD")
      (description "Socket")
      (fields (field (name "PUBLISHER") "Altium Limited"))
      (libsource (lib "Miscellaneous Connectors") (part "Socket"))
    )
    (comp (ref "J16")
      (value "~")
      (footprint "Wire24Awg2x1HPAD")
      (description "Socket")
      (fields (field (name "PUBLISHER") "Altium Limited"))
      (libsource (lib "Miscellaneous Connectors") (part "Socket"))
    )
    (comp (ref "J17")
      (value "~")
      (footprint "Wire24Awg2x1HPAD")
      (description "Socket")
      (fields (field (name "PUBLISHER") "Altium Limited"))
      (libsource (lib "Miscellaneous Connectors") (part "Socket"))
    )
    (comp (ref "J18")
      (value "~")
      (footprint "Wire24Awg2x1HPAD")
      (description "Socket")
      (fields (field (name "PUBLISHER") "Altium Limited"))
      (libsource (lib "Miscellaneous Connectors") (part "Socket"))
    )
    (comp (ref "J19")
      (value "~")
      (footprint "Wire24Awg2x1HPAD")
      (description "Socket")
      (fields (field (name "PUBLISHER") "Altium Limited"))
      (libsource (lib "Miscellaneous Connectors") (part "Socket"))
    )
    (comp (ref "J21")
      (value "~")
      (footprint "Wire24Awg2x1HPAD")
      (description "Socket")
      (fields (field (name "PUBLISHER") "Altium Limited"))
      (libsource (lib "Miscellaneous Connectors") (part "Socket"))
    )
    (comp (ref "J22")
      (value "~")
      (footprint "Wire24Awg2x1HPAD")
      (description "Socket")
      (fields (field (name "PUBLISHER") "Altium Limited"))
      (libsource (lib "Miscellaneous Connectors") (part "Socket"))
    )
    (comp (ref "J23")
      (value "~")
      (footprint "Wire24Awg2x1HPAD")
      (description "Socket")
      (fields (field (name "PUBLISHER") "Altium Limited"))
      (libsource (lib "Miscellaneous Connectors") (part "Socket"))
    )
    (comp (ref "J24")
      (value "~")
      (footprint "Wire24Awg2x1HPAD")
      (description "Socket")
      (fields (field (name "PUBLISHER") "Altium Limited"))
      (libsource (lib "Miscellaneous Connectors") (part "Socket"))
    )
    (comp (ref "J25")
      (value "~")
      (footprint "Wire24Awg2x1HPAD")
      (description "Socket")
      (fields (field (name "PUBLISHER") "Altium Limited"))
      (libsource (lib "Miscellaneous Connectors") (part "Socket"))
    )
    (comp (ref "J26")
      (value "~")
      (footprint "Wire24Awg2x1HPAD")
      (description "Socket")
      (fields (field (name "PUBLISHER") "Altium Limited"))
      (libsource (lib "Miscellaneous Connectors") (part "Socket"))
    )
    (comp (ref "J27")
      (value "~")
      (footprint "Wire24Awg2x1HPAD")
      (description "Socket")
      (fields (field (name "PUBLISHER") "Altium Limited"))
      (libsource (lib "Miscellaneous Connectors") (part "Socket"))
    )
    (comp (ref "J52")
      (value "~")
      (footprint "Wire24Awg2x1HPAD")
      (description "Socket")
      (fields (field (name "PUBLISHER") "Altium Limited"))
      (libsource (lib "Miscellaneous Connectors") (part "Socket"))
    )
    (comp (ref "J53")
      (value "~")
      (footprint "Wire24Awg2x1HPAD")
      (description "Socket")
      (fields (field (name "PUBLISHER") "Altium Limited"))
      (libsource (lib "Miscellaneous Connectors") (part "Socket"))
    )
    (comp (ref "J54")
      (value "~")
      (footprint "Wire24Awg2x1HPAD")
      (description "Socket")
      (fields (field (name "PUBLISHER") "Altium Limited"))
      (libsource (lib "Miscellaneous Connectors") (part "Socket"))
    )
    (comp (ref "J55")
      (value "~")
      (footprint "Wire24Awg2x1HPAD")
      (description "Socket")
      (fields (field (name "PUBLISHER") "Altium Limited"))
      (libsource (lib "Miscellaneous Connectors") (part "Socket"))
    )
    (comp (ref "J56")
      (value "~")
      (footprint "Wire24Awg2x1HPAD")
      (description "Socket")
      (fields (field (name "PUBLISHER") "Altium Limited"))
      (libsource (lib "Miscellaneous Connectors") (part "Socket"))
    )
    (comp (ref "J57")
      (value "~")
      (footprint "Wire24Awg2x1HPAD")
      (description "Socket")
      (fields (field (name "PUBLISHER") "Altium Limited"))
      (libsource (lib "Miscellaneous Connectors") (part "Socket"))
    )
    (comp (ref "J58")
      (value "~")
      (footprint "Wire24Awg2x1HPAD")
      (description "Socket")
      (fields (field (name "PUBLISHER") "Altium Limited"))
      (libsource (lib "Miscellaneous Connectors") (part "Socket"))
    )
    (comp (ref "L1")
      (value "4.7uH")
      (footprint "CS_Library:INDPM4441X200N")
      (description "Inductor")
      (fields
        (field (name "MANUFACTURER_PART_NUMBER") "IHLP1616BZER4R7M5A")
        (field (name "MOUSER PART NUMBER") "70-IHLP1616BZR4R7M5A")
      )
      (libsource (lib "CS_Library") (part "IHLP1616BZER4R7M5A"))
    )
    (comp (ref "L2")
      (value "3.3uH")
      (footprint "CS_Library:IHLP2020BZER3R3M01")
      (description "Inductor: 3.3 µH Shielded Molded Inductor 4 A 74.9mOhm Max Nonstandard")
      (fields
        (field (name "MANUFACTURER_PART_NUMBER") "IHLP2020BZER3R3M5A")
        (field (name "MOUSER PART NUMBER") "70-IHLP2020BZR3R3M5A")
      )
      (libsource (lib "CS_Library") (part "IHLP2020BZER3R3M5A"))
    )
    (comp (ref "L3")
      (value "?")
      (footprint "0603_DSP")
      (description "Inductor")
      (fields (field (name "PACKAGEREFERENCE") "0603") (field (name "PUBLISHER") "Altium Limited"))
      (libsource (lib "Miscellaneous Devices") (part "Inductor"))
    )
    (comp (ref "L4")
      (value "?")
      (footprint "0603_DSP")
      (description "Inductor")
      (fields (field (name "PACKAGEREFERENCE") "0603") (field (name "PUBLISHER") "Altium Limited"))
      (libsource (lib "Miscellaneous Devices") (part "Inductor"))
    )
    (comp (ref "L5")
      (value "?")
      (footprint "0603_DSP")
      (description "Inductor")
      (fields (field (name "PACKAGEREFERENCE") "0603") (field (name "PUBLISHER") "Altium Limited"))
      (libsource (lib "Miscellaneous Devices") (part "Inductor"))
    )
    (comp (ref "Q1")
      (value "DMG2305UX-7")
      (footprint "FP-SOT23-IPC_B")
      (description "MOSFET P-CH 20V 4.2A SOT23")
      (libsource (lib "Altium Content Vault") (part "87831b450059b469d4a68f5364f4496"))
    )
    (comp (ref "Q2")
      (value "BC846BLT1G")
      (footprint "ONSC-SOT-23-3-318-08_V")
      (description "General Purpose Transistor, NPN Silicon, 3-Pin SOT-23, Pb-Free, Tape and Reel")
      (fields (field (name "MANUFACTURER") "On Semiconductor") (field (name "CASE/PACKAGE") "*"))
      (libsource (lib "Altium Content Vault") (part "ONSC-NPN-B1E2C3-3"))
    )
    (comp (ref "Q3")
      (value "DMG2305UX-7")
      (footprint "FP-SOT23-IPC_B")
      (description "MOSFET P-CH 20V 4.2A SOT23")
      (libsource (lib "Altium Content Vault") (part "87831b450059b469d4a68f5364f4496"))
    )
    (comp (ref "Q4")
      (value "BC846BLT1G")
      (footprint "ONSC-SOT-23-3-318-08_V")
      (description "General Purpose Transistor, NPN Silicon, 3-Pin SOT-23, Pb-Free, Tape and Reel")
      (fields (field (name "MANUFACTURER") "On Semiconductor") (field (name "CASE/PACKAGE") "*"))
      (libsource (lib "Altium Content Vault") (part "ONSC-NPN-B1E2C3-3"))
    )
    (comp (ref "Q5")
      (value "DMG2305UX-7")
      (footprint "FP-SOT23-IPC_B")
      (description "MOSFET P-CH 20V 4.2A SOT23")
      (libsource (lib "Altium Content Vault") (part "87831b450059b469d4a68f5364f4496"))
    )
    (comp (ref "Q6")
      (value "DMG2305UX-7")
      (footprint "FP-SOT23-IPC_B")
      (description "MOSFET P-CH 20V 4.2A SOT23")
      (libsource (lib "Altium Content Vault") (part "87831b450059b469d4a68f5364f4496"))
    )
    (comp (ref "Q7")
      (value "SI3865DDV-T1-GE3")
      (footprint "CS_Library:SOP95P284X110-6N")
      (description "Transistor")
      (fields (field (name "MOUSER PART NUMBER") "78-SI3865DDV-T1-GE3") (field (name "CASE/PACKAGE") "*"))
      (libsource (lib "CS_Library") (part "SI3865DDV-T1-GE3"))
    )
    (comp (ref "Q8")
      (value "BC846BLT1G")
      (footprint "ONSC-SOT-23-3-318-08_V")
      (description "General Purpose Transistor, NPN Silicon, 3-Pin SOT-23, Pb-Free, Tape and Reel")
      (fields (field (name "MANUFACTURER") "On Semiconductor") (field (name "CASE/PACKAGE") "*"))
      (libsource (lib "Altium Content Vault") (part "ONSC-NPN-B1E2C3-3"))
    )
    (comp (ref "Q9")
      (value "BC846BLT1G")
      (footprint "ONSC-SOT-23-3-318-08_V")
      (description "General Purpose Transistor, NPN Silicon, 3-Pin SOT-23, Pb-Free, Tape and Reel")
      (fields (field (name "MANUFACTURER") "On Semiconductor") (field (name "CASE/PACKAGE") "*"))
      (libsource (lib "Altium Content Vault") (part "ONSC-NPN-B1E2C3-3"))
    )
    (comp (ref "Q10")
      (value "SI3865DDV-T1-GE3")
      (footprint "CS_Library:SOP95P284X110-6N")
      (description "Transistor")
      (fields (field (name "MOUSER PART NUMBER") "78-SI3865DDV-T1-GE3") (field (name "CASE/PACKAGE") "*"))
      (libsource (lib "CS_Library") (part "SI3865DDV-T1-GE3"))
    )
    (comp (ref "Q11")
      (value "SI3865DDV-T1-GE3")
      (footprint "CS_Library:SOP95P284X110-6N")
      (description "Transistor")
      (fields (field (name "MOUSER PART NUMBER") "78-SI3865DDV-T1-GE3") (field (name "CASE/PACKAGE") "*"))
      (libsource (lib "CS_Library") (part "SI3865DDV-T1-GE3"))
    )
    (comp (ref "R1")
      (value "27")
      (footprint "0402_DSP")
      (fields (field (name "CASE/PACKAGE") "0402"))
      (libsource (lib "CS_Library") (part "Resistor 0402"))
    )
    (comp (ref "R2")
      (value "0.5")
      (footprint "0402_DSP")
      (fields (field (name "CASE/PACKAGE") "0402"))
      (libsource (lib "CS_Library") (part "Resistor 0402"))
    )
    (comp (ref "R3")
      (value "0603")
      (footprint "0603_DSP")
      (fields (field (name "ALTIUM_VALUE") "120") (field (name "CASE/PACKAGE") "*"))
      (libsource (lib "CS_Library") (part "Resistor 0603"))
    )
    (comp (ref "R4")
      (value "10k")
      (footprint "0402_DSP")
      (fields
        (field (name "MANUFACTURER_PART_NUMBER") "CRCW040210K0FKEDC")
        (field (name "CASE/PACKAGE") "0402")
      )
      (libsource (lib "CS_Library") (part "Resistor 0402"))
    )
    (comp (ref "R5")
      (value "10k")
      (footprint "0402_DSP")
      (fields
        (field (name "MANUFACTURER_PART_NUMBER") "CRCW040210K0FKEDC")
        (field (name "CASE/PACKAGE") "0402")
      )
      (libsource (lib "CS_Library") (part "Resistor 0402"))
    )
    (comp (ref "R6")
      (value "27")
      (footprint "0402_DSP")
      (fields (field (name "CASE/PACKAGE") "0402"))
      (libsource (lib "CS_Library") (part "Resistor 0402"))
    )
    (comp (ref "R7")
      (value "3.3k")
      (footprint "0402_DSP")
      (fields
        (field (name "MANUFACTURER_PART_NUMBER") "CRCW04023K30FKEDC")
        (field (name "CASE/PACKAGE") "0402")
      )
      (libsource (lib "CS_Library") (part "Resistor 0402"))
    )
    (comp (ref "R8")
      (value "10k")
      (footprint "0402_DSP")
      (fields
        (field (name "MANUFACTURER_PART_NUMBER") "CRCW040210K0FKEDC")
        (field (name "CASE/PACKAGE") "0402")
      )
      (libsource (lib "CS_Library") (part "Resistor 0402"))
    )
    (comp (ref "R9")
      (value "10k")
      (footprint "0402_DSP")
      (fields
        (field (name "MANUFACTURER_PART_NUMBER") "CRCW040210K0FKEDC")
        (field (name "CASE/PACKAGE") "0402")
      )
      (libsource (lib "CS_Library") (part "Resistor 0402"))
    )
    (comp (ref "R10")
      (value "3.3k")
      (footprint "0402_DSP")
      (fields
        (field (name "MANUFACTURER_PART_NUMBER") "CRCW04023K30FKEDC")
        (field (name "CASE/PACKAGE") "0402")
      )
      (libsource (lib "CS_Library") (part "Resistor 0402"))
    )
    (comp (ref "R11")
      (value "10k")
      (footprint "0402_DSP")
      (fields
        (field (name "MANUFACTURER_PART_NUMBER") "CRCW040210K0FKEDC")
        (field (name "CASE/PACKAGE") "0402")
      )
      (libsource (lib "CS_Library") (part "Resistor 0402"))
    )
    (comp (ref "R12")
      (value "619k")
      (footprint "RESC1005X40X25NL05T05")
      (fields
        (field (name "PART NUMBER") "CRCW0402619KFKTD")
        (field (name "MANUFACTURER") "Vishay Dale")
        (field (name "CASE/PACKAGE") "*")
      )
      (libsource (lib "Altium Content Vault") (part "RES"))
    )
    (comp (ref "R13")
      (value "619k")
      (footprint "RESC1005X40X25NL05T05")
      (fields
        (field (name "PART NUMBER") "CRCW0402619KFKTD")
        (field (name "MANUFACTURER") "Vishay Dale")
        (field (name "CASE/PACKAGE") "*")
      )
      (libsource (lib "Altium Content Vault") (part "RES"))
    )
    (comp (ref "R14")
      (value "137k")
      (footprint "0402_DSP")
      (fields (field (name "CASE/PACKAGE") "0402"))
      (libsource (lib "CS_Library") (part "Resistor 0402"))
    )
    (comp (ref "R15")
      (value "84.5k")
      (footprint "0402_DSP")
      (fields (field (name "CASE/PACKAGE") "0402"))
      (libsource (lib "CS_Library") (part "Resistor 0402"))
    )
    (comp (ref "R16")
      (value "0.5")
      (footprint "0402_DSP")
      (fields (field (name "CASE/PACKAGE") "0402"))
      (libsource (lib "CS_Library") (part "Resistor 0402"))
    )
    (comp (ref "R17")
      (value "0603")
      (footprint "0603_DSP")
      (fields (field (name "ALTIUM_VALUE") "120") (field (name "CASE/PACKAGE") "*"))
      (libsource (lib "CS_Library") (part "Resistor 0603"))
    )
    (comp (ref "R18")
      (value "10k")
      (footprint "0402_DSP")
      (fields
        (field (name "MANUFACTURER_PART_NUMBER") "CRCW040210K0FKEDC")
        (field (name "CASE/PACKAGE") "0402")
      )
      (libsource (lib "CS_Library") (part "Resistor 0402"))
    )
    (comp (ref "R19")
      (value "100k")
      (footprint "0402_DSP")
      (fields
        (field (name "MANUFACTURER_PART_NUMBER") "CRCW0402100KFKEDC")
        (field (name "CASE/PACKAGE") "0402")
      )
      (libsource (lib "CS_Library") (part "Resistor 0402"))
    )
    (comp (ref "R20")
      (value "100k")
      (footprint "0402_DSP")
      (fields
        (field (name "MANUFACTURER_PART_NUMBER") "CRCW0402100KFKEDC")
        (field (name "CASE/PACKAGE") "0402")
      )
      (libsource (lib "CS_Library") (part "Resistor 0402"))
    )
    (comp (ref "R21")
      (value "27")
      (footprint "0402_DSP")
      (fields (field (name "CASE/PACKAGE") "0402"))
      (libsource (lib "CS_Library") (part "Resistor 0402"))
    )
    (comp (ref "R22")
      (value "100k")
      (footprint "0402_DSP")
      (fields
        (field (name "MANUFACTURER_PART_NUMBER") "CRCW0402100KFKEDC")
        (field (name "CASE/PACKAGE") "0402")
      )
      (libsource (lib "CS_Library") (part "Resistor 0402"))
    )
    (comp (ref "R23")
      (value "100k")
      (footprint "0402_DSP")
      (fields
        (field (name "MANUFACTURER_PART_NUMBER") "CRCW0402100KFKEDC")
        (field (name "CASE/PACKAGE") "0402")
      )
      (libsource (lib "CS_Library") (part "Resistor 0402"))
    )
    (comp (ref "R24")
      (value "100k")
      (footprint "0402_DSP")
      (fields
        (field (name "MANUFACTURER_PART_NUMBER") "CRCW0402100KFKEDC")
        (field (name "CASE/PACKAGE") "0402")
      )
      (libsource (lib "CS_Library") (part "Resistor 0402"))
    )
    (comp (ref "R25")
      (value "100k")
      (footprint "0402_DSP")
      (fields
        (field (name "MANUFACTURER_PART_NUMBER") "CRCW0402100KFKEDC")
        (field (name "CASE/PACKAGE") "0402")
      )
      (libsource (lib "CS_Library") (part "Resistor 0402"))
    )
    (comp (ref "R26")
      (value "100k")
      (footprint "0402_DSP")
      (fields
        (field (name "MANUFACTURER_PART_NUMBER") "CRCW0402100KFKEDC")
        (field (name "CASE/PACKAGE") "0402")
      )
      (libsource (lib "CS_Library") (part "Resistor 0402"))
    )
    (comp (ref "R27")
      (value "100k")
      (footprint "0402_DSP")
      (fields
        (field (name "MANUFACTURER_PART_NUMBER") "CRCW0402100KFKEDC")
        (field (name "CASE/PACKAGE") "0402")
      )
      (libsource (lib "CS_Library") (part "Resistor 0402"))
    )
    (comp (ref "R28")
      (value "100k")
      (footprint "0402_DSP")
      (fields
        (field (name "MANUFACTURER_PART_NUMBER") "CRCW0402100KFKEDC")
        (field (name "CASE/PACKAGE") "0402")
      )
      (libsource (lib "CS_Library") (part "Resistor 0402"))
    )
    (comp (ref "R29")
      (value "100k")
      (footprint "0402_DSP")
      (fields
        (field (name "MANUFACTURER_PART_NUMBER") "CRCW0402100KFKEDC")
        (field (name "CASE/PACKAGE") "0402")
      )
      (libsource (lib "CS_Library") (part "Resistor 0402"))
    )
    (comp (ref "R30")
      (value "100k")
      (footprint "0402_DSP")
      (fields
        (field (name "MANUFACTURER_PART_NUMBER") "CRCW0402100KFKEDC")
        (field (name "CASE/PACKAGE") "0402")
      )
      (libsource (lib "CS_Library") (part "Resistor 0402"))
    )
    (comp (ref "R31")
      (value "100k")
      (footprint "0402_DSP")
      (fields
        (field (name "MANUFACTURER_PART_NUMBER") "CRCW0402100KFKEDC")
        (field (name "CASE/PACKAGE") "0402")
      )
      (libsource (lib "CS_Library") (part "Resistor 0402"))
    )
    (comp (ref "R32")
      (value "100k")
      (footprint "0402_DSP")
      (fields
        (field (name "MANUFACTURER_PART_NUMBER") "CRCW0402100KFKEDC")
        (field (name "CASE/PACKAGE") "0402")
      )
      (libsource (lib "CS_Library") (part "Resistor 0402"))
    )
    (comp (ref "R33")
      (value "100k")
      (footprint "0402_DSP")
      (fields
        (field (name "MANUFACTURER_PART_NUMBER") "CRCW0402100KFKEDC")
        (field (name "CASE/PACKAGE") "0402")
      )
      (libsource (lib "CS_Library") (part "Resistor 0402"))
    )
    (comp (ref "R34")
      (value "100k")
      (footprint "0402_DSP")
      (fields
        (field (name "MANUFACTURER_PART_NUMBER") "CRCW0402100KFKEDC")
        (field (name "CASE/PACKAGE") "0402")
      )
      (libsource (lib "CS_Library") (part "Resistor 0402"))
    )
    (comp (ref "R35")
      (value "100k")
      (footprint "0402_DSP")
      (fields
        (field (name "MANUFACTURER_PART_NUMBER") "CRCW0402100KFKEDC")
        (field (name "CASE/PACKAGE") "0402")
      )
      (libsource (lib "CS_Library") (part "Resistor 0402"))
    )
    (comp (ref "R36")
      (value "100k")
      (footprint "0402_DSP")
      (fields
        (field (name "MANUFACTURER_PART_NUMBER") "CRCW0402100KFKEDC")
        (field (name "CASE/PACKAGE") "0402")
      )
      (libsource (lib "CS_Library") (part "Resistor 0402"))
    )
    (comp (ref "R37")
      (value "100k")
      (footprint "0402_DSP")
      (fields
        (field (name "MANUFACTURER_PART_NUMBER") "CRCW0402100KFKEDC")
        (field (name "CASE/PACKAGE") "0402")
      )
      (libsource (lib "CS_Library") (part "Resistor 0402"))
    )
    (comp (ref "R38")
      (value "20")
      (footprint "0402_DSP")
      (fields (field (name "CASE/PACKAGE") "0402"))
      (libsource (lib "CS_Library") (part "Resistor 0402"))
    )
    (comp (ref "R39")
      (value "119k")
      (footprint "0402_DSP")
      (fields (field (name "CASE/PACKAGE") "0402"))
      (libsource (lib "CS_Library") (part "Resistor 0402"))
    )
    (comp (ref "R40")
      (value "100k")
      (footprint "0402_DSP")
      (fields
        (field (name "MANUFACTURER_PART_NUMBER") "CRCW040210K0FKEDC")
        (field (name "CASE/PACKAGE") "0402")
      )
      (libsource (lib "CS_Library") (part "Resistor 0402"))
    )
    (comp (ref "R41")
      (value "17k")
      (footprint "0402_DSP")
      (fields (field (name "CASE/PACKAGE") "0402"))
      (libsource (lib "CS_Library") (part "Resistor 0402"))
    )
    (comp (ref "R42")
      (value "27")
      (footprint "0402_DSP")
      (fields (field (name "CASE/PACKAGE") "0402"))
      (libsource (lib "CS_Library") (part "Resistor 0402"))
    )
    (comp (ref "R43")
      (value "20")
      (footprint "0402_DSP")
      (fields (field (name "CASE/PACKAGE") "0402"))
      (libsource (lib "CS_Library") (part "Resistor 0402"))
    )
    (comp (ref "R44")
      (value "119k")
      (footprint "0402_DSP")
      (fields (field (name "CASE/PACKAGE") "0402"))
      (libsource (lib "CS_Library") (part "Resistor 0402"))
    )
    (comp (ref "R45")
      (value "17k")
      (footprint "0402_DSP")
      (fields (field (name "CASE/PACKAGE") "0402"))
      (libsource (lib "CS_Library") (part "Resistor 0402"))
    )
    (comp (ref "R46")
      (value "100k")
      (footprint "0402_DSP")
      (fields
        (field (name "MANUFACTURER_PART_NUMBER") "CRCW040210K0FKEDC")
        (field (name "CASE/PACKAGE") "0402")
      )
      (libsource (lib "CS_Library") (part "Resistor 0402"))
    )
    (comp (ref "R47")
      (value "100k")
      (footprint "0402_DSP")
      (fields
        (field (name "MANUFACTURER_PART_NUMBER") "CRCW0402100KFKEDC")
        (field (name "CASE/PACKAGE") "0402")
      )
      (libsource (lib "CS_Library") (part "Resistor 0402"))
    )
    (comp (ref "R48")
      (value "100k")
      (footprint "0402_DSP")
      (fields
        (field (name "MANUFACTURER_PART_NUMBER") "CRCW0402100KFKEDC")
        (field (name "CASE/PACKAGE") "0402")
      )
      (libsource (lib "CS_Library") (part "Resistor 0402"))
    )
    (comp (ref "R49")
      (value "100k")
      (footprint "0402_DSP")
      (fields
        (field (name "MANUFACTURER_PART_NUMBER") "CRCW0402100KFKEDC")
        (field (name "CASE/PACKAGE") "0402")
      )
      (libsource (lib "CS_Library") (part "Resistor 0402"))
    )
    (comp (ref "R50")
      (value "100k")
      (footprint "0402_DSP")
      (fields
        (field (name "MANUFACTURER_PART_NUMBER") "CRCW0402100KFKEDC")
        (field (name "CASE/PACKAGE") "0402")
      )
      (libsource (lib "CS_Library") (part "Resistor 0402"))
    )
    (comp (ref "R51")
      (value "49.9")
      (footprint "0402_DSP")
      (fields (field (name "CASE/PACKAGE") "0402"))
      (libsource (lib "CS_Library") (part "Resistor 0402"))
    )
    (comp (ref "R52")
      (value "49.9")
      (footprint "0402_DSP")
      (fields (field (name "CASE/PACKAGE") "0402"))
      (libsource (lib "CS_Library") (part "Resistor 0402"))
    )
    (comp (ref "R53")
      (value "49.9")
      (footprint "0402_DSP")
      (fields (field (name "CASE/PACKAGE") "0402"))
      (libsource (lib "CS_Library") (part "Resistor 0402"))
    )
    (comp (ref "R54")
      (value "49.9")
      (footprint "0402_DSP")
      (fields (field (name "CASE/PACKAGE") "0402"))
      (libsource (lib "CS_Library") (part "Resistor 0402"))
    )
    (comp (ref "R55")
      (value "100k")
      (footprint "0402_DSP")
      (fields
        (field (name "MANUFACTURER_PART_NUMBER") "CRCW0402100KFKEDC")
        (field (name "CASE/PACKAGE") "0402")
      )
      (libsource (lib "CS_Library") (part "Resistor 0402"))
    )
    (comp (ref "R56")
      (value "100k")
      (footprint "0402_DSP")
      (fields
        (field (name "MANUFACTURER_PART_NUMBER") "CRCW0402100KFKEDC")
        (field (name "CASE/PACKAGE") "0402")
      )
      (libsource (lib "CS_Library") (part "Resistor 0402"))
    )
    (comp (ref "R57")
      (value "100k")
      (footprint "0402_DSP")
      (fields
        (field (name "MANUFACTURER_PART_NUMBER") "CRCW0402100KFKEDC")
        (field (name "CASE/PACKAGE") "0402")
      )
      (libsource (lib "CS_Library") (part "Resistor 0402"))
    )
    (comp (ref "R58")
      (value "100k")
      (footprint "0402_DSP")
      (fields
        (field (name "MANUFACTURER_PART_NUMBER") "CRCW0402100KFKEDC")
        (field (name "CASE/PACKAGE") "0402")
      )
      (libsource (lib "CS_Library") (part "Resistor 0402"))
    )
    (comp (ref "R59")
      (value "100k")
      (footprint "0402_DSP")
      (fields
        (field (name "MANUFACTURER_PART_NUMBER") "CRCW0402100KFKEDC")
        (field (name "CASE/PACKAGE") "0402")
      )
      (libsource (lib "CS_Library") (part "Resistor 0402"))
    )
    (comp (ref "R60")
      (value "100k")
      (footprint "0402_DSP")
      (fields
        (field (name "MANUFACTURER_PART_NUMBER") "CRCW0402100KFKEDC")
        (field (name "CASE/PACKAGE") "0402")
      )
      (libsource (lib "CS_Library") (part "Resistor 0402"))
    )
    (comp (ref "R61")
      (value "100k")
      (footprint "0402_DSP")
      (fields
        (field (name "MANUFACTURER_PART_NUMBER") "CRCW0402100KFKEDC")
        (field (name "CASE/PACKAGE") "0402")
      )
      (libsource (lib "CS_Library") (part "Resistor 0402"))
    )
    (comp (ref "R62")
      (value "100k")
      (footprint "0402_DSP")
      (fields
        (field (name "MANUFACTURER_PART_NUMBER") "CRCW0402100KFKEDC")
        (field (name "CASE/PACKAGE") "0402")
      )
      (libsource (lib "CS_Library") (part "Resistor 0402"))
    )
    (comp (ref "R63")
      (value "100k")
      (footprint "0402_DSP")
      (fields
        (field (name "MANUFACTURER_PART_NUMBER") "CRCW0402100KFKEDC")
        (field (name "CASE/PACKAGE") "0402")
      )
      (libsource (lib "CS_Library") (part "Resistor 0402"))
    )
    (comp (ref "R64")
      (value "100k")
      (footprint "0402_DSP")
      (fields
        (field (name "MANUFACTURER_PART_NUMBER") "CRCW0402100KFKEDC")
        (field (name "CASE/PACKAGE") "0402")
      )
      (libsource (lib "CS_Library") (part "Resistor 0402"))
    )
    (comp (ref "R65")
      (value "100k")
      (footprint "0402_DSP")
      (fields
        (field (name "MANUFACTURER_PART_NUMBER") "CRCW0402100KFKEDC")
        (field (name "CASE/PACKAGE") "0402")
      )
      (libsource (lib "CS_Library") (part "Resistor 0402"))
    )
    (comp (ref "R66")
      (value "100k")
      (footprint "0402_DSP")
      (fields
        (field (name "MANUFACTURER_PART_NUMBER") "CRCW0402100KFKEDC")
        (field (name "CASE/PACKAGE") "0402")
      )
      (libsource (lib "CS_Library") (part "Resistor 0402"))
    )
    (comp (ref "R67")
      (value "0.5")
      (footprint "0402_DSP")
      (fields (field (name "CASE/PACKAGE") "0402"))
      (libsource (lib "CS_Library") (part "Resistor 0402"))
    )
    (comp (ref "R68")
      (value "20")
      (footprint "0402_DSP")
      (fields (field (name "CASE/PACKAGE") "0402"))
      (libsource (lib "CS_Library") (part "Resistor 0402"))
    )
    (comp (ref "R69")
      (value "119k")
      (footprint "0402_DSP")
      (fields (field (name "CASE/PACKAGE") "0402"))
      (libsource (lib "CS_Library") (part "Resistor 0402"))
    )
    (comp (ref "R70")
      (value "17k")
      (footprint "0402_DSP")
      (fields (field (name "CASE/PACKAGE") "0402"))
      (libsource (lib "CS_Library") (part "Resistor 0402"))
    )
    (comp (ref "R71")
      (value "20")
      (footprint "0402_DSP")
      (fields (field (name "CASE/PACKAGE") "0402"))
      (libsource (lib "CS_Library") (part "Resistor 0402"))
    )
    (comp (ref "R72")
      (value "119k")
      (footprint "0402_DSP")
      (fields (field (name "CASE/PACKAGE") "0402"))
      (libsource (lib "CS_Library") (part "Resistor 0402"))
    )
    (comp (ref "R73")
      (value "20")
      (footprint "0402_DSP")
      (fields (field (name "CASE/PACKAGE") "0402"))
      (libsource (lib "CS_Library") (part "Resistor 0402"))
    )
    (comp (ref "R74")
      (value "17k")
      (footprint "0402_DSP")
      (fields (field (name "CASE/PACKAGE") "0402"))
      (libsource (lib "CS_Library") (part "Resistor 0402"))
    )
    (comp (ref "R75")
      (value "100k")
      (footprint "0402_DSP")
      (fields
        (field (name "MANUFACTURER_PART_NUMBER") "CRCW0402100KFKEDC")
        (field (name "CASE/PACKAGE") "0402")
      )
      (libsource (lib "CS_Library") (part "Resistor 0402"))
    )
    (comp (ref "R76")
      (value "100k")
      (footprint "0402_DSP")
      (fields
        (field (name "MANUFACTURER_PART_NUMBER") "CRCW0402100KFKEDC")
        (field (name "CASE/PACKAGE") "0402")
      )
      (libsource (lib "CS_Library") (part "Resistor 0402"))
    )
    (comp (ref "R77")
      (value "100k")
      (footprint "0402_DSP")
      (fields
        (field (name "MANUFACTURER_PART_NUMBER") "CRCW0402100KFKEDC")
        (field (name "CASE/PACKAGE") "0402")
      )
      (libsource (lib "CS_Library") (part "Resistor 0402"))
    )
    (comp (ref "R78")
      (value "100k")
      (footprint "0402_DSP")
      (fields
        (field (name "MANUFACTURER_PART_NUMBER") "CRCW0402100KFKEDC")
        (field (name "CASE/PACKAGE") "0402")
      )
      (libsource (lib "CS_Library") (part "Resistor 0402"))
    )
    (comp (ref "R79")
      (value "100k")
      (footprint "0402_DSP")
      (fields
        (field (name "MANUFACTURER_PART_NUMBER") "CRCW0402100KFKEDC")
        (field (name "CASE/PACKAGE") "0402")
      )
      (libsource (lib "CS_Library") (part "Resistor 0402"))
    )
    (comp (ref "R80")
      (value "100k")
      (footprint "0402_DSP")
      (fields
        (field (name "MANUFACTURER_PART_NUMBER") "CRCW0402100KFKEDC")
        (field (name "CASE/PACKAGE") "0402")
      )
      (libsource (lib "CS_Library") (part "Resistor 0402"))
    )
    (comp (ref "R81")
      (value "100k")
      (footprint "0402_DSP")
      (fields
        (field (name "MANUFACTURER_PART_NUMBER") "CRCW0402100KFKEDC")
        (field (name "CASE/PACKAGE") "0402")
      )
      (libsource (lib "CS_Library") (part "Resistor 0402"))
    )
    (comp (ref "R82")
      (value "100k")
      (footprint "0402_DSP")
      (fields
        (field (name "MANUFACTURER_PART_NUMBER") "CRCW0402100KFKEDC")
        (field (name "CASE/PACKAGE") "0402")
      )
      (libsource (lib "CS_Library") (part "Resistor 0402"))
    )
    (comp (ref "R83")
      (value "100k")
      (footprint "0402_DSP")
      (fields
        (field (name "MANUFACTURER_PART_NUMBER") "CRCW0402100KFKEDC")
        (field (name "CASE/PACKAGE") "0402")
      )
      (libsource (lib "CS_Library") (part "Resistor 0402"))
    )
    (comp (ref "R84")
      (value "100k")
      (footprint "0402_DSP")
      (fields
        (field (name "MANUFACTURER_PART_NUMBER") "CRCW0402100KFKEDC")
        (field (name "CASE/PACKAGE") "0402")
      )
      (libsource (lib "CS_Library") (part "Resistor 0402"))
    )
    (comp (ref "R85")
      (value "100k")
      (footprint "0402_DSP")
      (fields
        (field (name "MANUFACTURER_PART_NUMBER") "CRCW0402100KFKEDC")
        (field (name "CASE/PACKAGE") "0402")
      )
      (libsource (lib "CS_Library") (part "Resistor 0402"))
    )
    (comp (ref "R86")
      (value "100k")
      (footprint "0402_DSP")
      (fields
        (field (name "MANUFACTURER_PART_NUMBER") "CRCW0402100KFKEDC")
        (field (name "CASE/PACKAGE") "0402")
      )
      (libsource (lib "CS_Library") (part "Resistor 0402"))
    )
    (comp (ref "R87")
      (value "100k")
      (footprint "0402_DSP")
      (fields
        (field (name "MANUFACTURER_PART_NUMBER") "CRCW0402100KFKEDC")
        (field (name "CASE/PACKAGE") "0402")
      )
      (libsource (lib "CS_Library") (part "Resistor 0402"))
    )
    (comp (ref "R88")
      (value "100k")
      (footprint "0402_DSP")
      (fields
        (field (name "MANUFACTURER_PART_NUMBER") "CRCW0402100KFKEDC")
        (field (name "CASE/PACKAGE") "0402")
      )
      (libsource (lib "CS_Library") (part "Resistor 0402"))
    )
    (comp (ref "R89")
      (value "100k")
      (footprint "0402_DSP")
      (fields
        (field (name "MANUFACTURER_PART_NUMBER") "CRCW0402100KFKEDC")
        (field (name "CASE/PACKAGE") "0402")
      )
      (libsource (lib "CS_Library") (part "Resistor 0402"))
    )
    (comp (ref "R90")
      (value "100k")
      (footprint "0402_DSP")
      (fields
        (field (name "MANUFACTURER_PART_NUMBER") "CRCW0402100KFKEDC")
        (field (name "CASE/PACKAGE") "0402")
      )
      (libsource (lib "CS_Library") (part "Resistor 0402"))
    )
    (comp (ref "R91")
      (value "27")
      (footprint "0402_DSP")
      (fields (field (name "CASE/PACKAGE") "0402"))
      (libsource (lib "CS_Library") (part "Resistor 0402"))
    )
    (comp (ref "R92")
      (value "2.61k")
      (footprint "0402_DSP")
      (fields (field (name "CASE/PACKAGE") "0402"))
      (libsource (lib "CS_Library") (part "Resistor 0402"))
    )
    (comp (ref "R93")
      (value "20")
      (footprint "0402_DSP")
      (fields (field (name "CASE/PACKAGE") "0402"))
      (libsource (lib "CS_Library") (part "Resistor 0402"))
    )
    (comp (ref "R94")
      (value "119k")
      (footprint "0402_DSP")
      (fields (field (name "CASE/PACKAGE") "0402"))
      (libsource (lib "CS_Library") (part "Resistor 0402"))
    )
    (comp (ref "R95")
      (value "17k")
      (footprint "0402_DSP")
      (fields (field (name "CASE/PACKAGE") "0402"))
      (libsource (lib "CS_Library") (part "Resistor 0402"))
    )
    (comp (ref "R96")
      (value "0402")
      (footprint "0402_DSP")
      (fields (field (name "ALTIUM_VALUE") "100k") (field (name "TOLERANCE") "0.1%"))
      (libsource (lib "CS_Library") (part "Resistor 0402"))
    )
    (comp (ref "R97")
      (value "0402")
      (footprint "0402_DSP")
      (fields (field (name "ALTIUM_VALUE") "100k") (field (name "TOLERANCE") "0.1%"))
      (libsource (lib "CS_Library") (part "Resistor 0402"))
    )
    (comp (ref "R98")
      (value "100k")
      (footprint "0402_DSP")
      (fields
        (field (name "MANUFACTURER_PART_NUMBER") "CRCW0402100KFKEDC")
        (field (name "CASE/PACKAGE") "0402")
      )
      (libsource (lib "CS_Library") (part "Resistor 0402"))
    )
    (comp (ref "R99")
      (value "100k")
      (footprint "0402_DSP")
      (fields
        (field (name "MANUFACTURER_PART_NUMBER") "CRCW0402100KFKEDC")
        (field (name "CASE/PACKAGE") "0402")
      )
      (libsource (lib "CS_Library") (part "Resistor 0402"))
    )
    (comp (ref "R100")
      (value "100k")
      (footprint "0402_DSP")
      (fields
        (field (name "MANUFACTURER_PART_NUMBER") "CRCW0402100KFKEDC")
        (field (name "CASE/PACKAGE") "0402")
      )
      (libsource (lib "CS_Library") (part "Resistor 0402"))
    )
    (comp (ref "R101")
      (value "3.3k")
      (footprint "0402_DSP")
      (fields
        (field (name "MANUFACTURER_PART_NUMBER") "CRCW04023K30FKEDC")
        (field (name "CASE/PACKAGE") "0402")
      )
      (libsource (lib "CS_Library") (part "Resistor 0402"))
    )
    (comp (ref "R102")
      (value "10k")
      (footprint "0402_DSP")
      (fields
        (field (name "MANUFACTURER_PART_NUMBER") "CRCW040210K0FKEDC")
        (field (name "CASE/PACKAGE") "0402")
      )
      (libsource (lib "CS_Library") (part "Resistor 0402"))
    )
    (comp (ref "R103")
      (value "20")
      (footprint "0402_DSP")
      (fields (field (name "CASE/PACKAGE") "0402"))
      (libsource (lib "CS_Library") (part "Resistor 0402"))
    )
    (comp (ref "R105")
      (value "119k")
      (footprint "0402_DSP")
      (fields (field (name "CASE/PACKAGE") "0402"))
      (libsource (lib "CS_Library") (part "Resistor 0402"))
    )
    (comp (ref "R106")
      (value "100k")
      (footprint "0402_DSP")
      (fields
        (field (name "MANUFACTURER_PART_NUMBER") "CRCW0402100KFKEDC")
        (field (name "CASE/PACKAGE") "0402")
      )
      (libsource (lib "CS_Library") (part "Resistor 0402"))
    )
    (comp (ref "R107")
      (value "100k")
      (footprint "0402_DSP")
      (fields
        (field (name "MANUFACTURER_PART_NUMBER") "CRCW0402100KFKEDC")
        (field (name "CASE/PACKAGE") "0402")
      )
      (libsource (lib "CS_Library") (part "Resistor 0402"))
    )
    (comp (ref "R108")
      (value "100k")
      (footprint "0402_DSP")
      (fields
        (field (name "MANUFACTURER_PART_NUMBER") "CRCW0402100KFKEDC")
        (field (name "CASE/PACKAGE") "0402")
      )
      (libsource (lib "CS_Library") (part "Resistor 0402"))
    )
    (comp (ref "R109")
      (value "100k")
      (footprint "0402_DSP")
      (fields
        (field (name "MANUFACTURER_PART_NUMBER") "CRCW0402100KFKEDC")
        (field (name "CASE/PACKAGE") "0402")
      )
      (libsource (lib "CS_Library") (part "Resistor 0402"))
    )
    (comp (ref "R110")
      (value "100k")
      (footprint "0402_DSP")
      (fields
        (field (name "MANUFACTURER_PART_NUMBER") "CRCW0402100KFKEDC")
        (field (name "CASE/PACKAGE") "0402")
      )
      (libsource (lib "CS_Library") (part "Resistor 0402"))
    )
    (comp (ref "R111")
      (value "100k")
      (footprint "0402_DSP")
      (fields
        (field (name "MANUFACTURER_PART_NUMBER") "CRCW0402100KFKEDC")
        (field (name "CASE/PACKAGE") "0402")
      )
      (libsource (lib "CS_Library") (part "Resistor 0402"))
    )
    (comp (ref "R112")
      (value "100k")
      (footprint "0402_DSP")
      (fields
        (field (name "MANUFACTURER_PART_NUMBER") "CRCW0402100KFKEDC")
        (field (name "CASE/PACKAGE") "0402")
      )
      (libsource (lib "CS_Library") (part "Resistor 0402"))
    )
    (comp (ref "R113")
      (value "100k")
      (footprint "0402_DSP")
      (fields
        (field (name "MANUFACTURER_PART_NUMBER") "CRCW0402100KFKEDC")
        (field (name "CASE/PACKAGE") "0402")
      )
      (libsource (lib "CS_Library") (part "Resistor 0402"))
    )
    (comp (ref "R114")
      (value "100k")
      (footprint "0402_DSP")
      (fields
        (field (name "MANUFACTURER_PART_NUMBER") "CRCW0402100KFKEDC")
        (field (name "CASE/PACKAGE") "0402")
      )
      (libsource (lib "CS_Library") (part "Resistor 0402"))
    )
    (comp (ref "R115")
      (value "100k")
      (footprint "0402_DSP")
      (fields
        (field (name "MANUFACTURER_PART_NUMBER") "CRCW0402100KFKEDC")
        (field (name "CASE/PACKAGE") "0402")
      )
      (libsource (lib "CS_Library") (part "Resistor 0402"))
    )
    (comp (ref "R116")
      (value "100k")
      (footprint "0402_DSP")
      (fields
        (field (name "MANUFACTURER_PART_NUMBER") "CRCW0402100KFKEDC")
        (field (name "CASE/PACKAGE") "0402")
      )
      (libsource (lib "CS_Library") (part "Resistor 0402"))
    )
    (comp (ref "R117")
      (value "100k")
      (footprint "0402_DSP")
      (fields
        (field (name "MANUFACTURER_PART_NUMBER") "CRCW0402100KFKEDC")
        (field (name "CASE/PACKAGE") "0402")
      )
      (libsource (lib "CS_Library") (part "Resistor 0402"))
    )
    (comp (ref "R118")
      (value "100k")
      (footprint "0402_DSP")
      (fields
        (field (name "MANUFACTURER_PART_NUMBER") "CRCW0402100KFKEDC")
        (field (name "CASE/PACKAGE") "0402")
      )
      (libsource (lib "CS_Library") (part "Resistor 0402"))
    )
    (comp (ref "R119")
      (value "100k")
      (footprint "0402_DSP")
      (fields
        (field (name "MANUFACTURER_PART_NUMBER") "CRCW0402100KFKEDC")
        (field (name "CASE/PACKAGE") "0402")
      )
      (libsource (lib "CS_Library") (part "Resistor 0402"))
    )
    (comp (ref "R120")
      (value "100k")
      (footprint "0402_DSP")
      (fields
        (field (name "MANUFACTURER_PART_NUMBER") "CRCW0402100KFKEDC")
        (field (name "CASE/PACKAGE") "0402")
      )
      (libsource (lib "CS_Library") (part "Resistor 0402"))
    )
    (comp (ref "R121")
      (value "100k")
      (footprint "0402_DSP")
      (fields
        (field (name "MANUFACTURER_PART_NUMBER") "CRCW0402100KFKEDC")
        (field (name "CASE/PACKAGE") "0402")
      )
      (libsource (lib "CS_Library") (part "Resistor 0402"))
    )
    (comp (ref "R122")
      (value "100k")
      (footprint "0402_DSP")
      (fields
        (field (name "MANUFACTURER_PART_NUMBER") "CRCW0402100KFKEDC")
        (field (name "CASE/PACKAGE") "0402")
      )
      (libsource (lib "CS_Library") (part "Resistor 0402"))
    )
    (comp (ref "R123")
      (value "100k")
      (footprint "0402_DSP")
      (fields
        (field (name "MANUFACTURER_PART_NUMBER") "CRCW0402100KFKEDC")
        (field (name "CASE/PACKAGE") "0402")
      )
      (libsource (lib "CS_Library") (part "Resistor 0402"))
    )
    (comp (ref "R124")
      (value "100k")
      (footprint "0402_DSP")
      (fields
        (field (name "MANUFACTURER_PART_NUMBER") "CRCW0402100KFKEDC")
        (field (name "CASE/PACKAGE") "0402")
      )
      (libsource (lib "CS_Library") (part "Resistor 0402"))
    )
    (comp (ref "R125")
      (value "100k")
      (footprint "0402_DSP")
      (fields
        (field (name "MANUFACTURER_PART_NUMBER") "CRCW0402100KFKEDC")
        (field (name "CASE/PACKAGE") "0402")
      )
      (libsource (lib "CS_Library") (part "Resistor 0402"))
    )
    (comp (ref "R126")
      (value "100k")
      (footprint "0402_DSP")
      (fields
        (field (name "MANUFACTURER_PART_NUMBER") "CRCW0402100KFKEDC")
        (field (name "CASE/PACKAGE") "0402")
      )
      (libsource (lib "CS_Library") (part "Resistor 0402"))
    )
    (comp (ref "R127")
      (value "100k")
      (footprint "0402_DSP")
      (fields
        (field (name "MANUFACTURER_PART_NUMBER") "CRCW0402100KFKEDC")
        (field (name "CASE/PACKAGE") "0402")
      )
      (libsource (lib "CS_Library") (part "Resistor 0402"))
    )
    (comp (ref "R128")
      (value "100k")
      (footprint "0402_DSP")
      (fields
        (field (name "MANUFACTURER_PART_NUMBER") "CRCW0402100KFKEDC")
        (field (name "CASE/PACKAGE") "0402")
      )
      (libsource (lib "CS_Library") (part "Resistor 0402"))
    )
    (comp (ref "R129")
      (value "100k")
      (footprint "0402_DSP")
      (fields
        (field (name "MANUFACTURER_PART_NUMBER") "CRCW0402100KFKEDC")
        (field (name "CASE/PACKAGE") "0402")
      )
      (libsource (lib "CS_Library") (part "Resistor 0402"))
    )
    (comp (ref "R130")
      (value "100k")
      (footprint "0402_DSP")
      (fields
        (field (name "MANUFACTURER_PART_NUMBER") "CRCW0402100KFKEDC")
        (field (name "CASE/PACKAGE") "0402")
      )
      (libsource (lib "CS_Library") (part "Resistor 0402"))
    )
    (comp (ref "R131")
      (value "100k")
      (footprint "0402_DSP")
      (fields
        (field (name "MANUFACTURER_PART_NUMBER") "CRCW0402100KFKEDC")
        (field (name "CASE/PACKAGE") "0402")
      )
      (libsource (lib "CS_Library") (part "Resistor 0402"))
    )
    (comp (ref "R132")
      (value "100k")
      (footprint "0402_DSP")
      (fields
        (field (name "MANUFACTURER_PART_NUMBER") "CRCW0402100KFKEDC")
        (field (name "CASE/PACKAGE") "0402")
      )
      (libsource (lib "CS_Library") (part "Resistor 0402"))
    )
    (comp (ref "R133")
      (value "100k")
      (footprint "0402_DSP")
      (fields
        (field (name "MANUFACTURER_PART_NUMBER") "CRCW0402100KFKEDC")
        (field (name "CASE/PACKAGE") "0402")
      )
      (libsource (lib "CS_Library") (part "Resistor 0402"))
    )
    (comp (ref "R134")
      (value "100k")
      (footprint "0402_DSP")
      (fields
        (field (name "MANUFACTURER_PART_NUMBER") "CRCW0402100KFKEDC")
        (field (name "CASE/PACKAGE") "0402")
      )
      (libsource (lib "CS_Library") (part "Resistor 0402"))
    )
    (comp (ref "R135")
      (value "100k")
      (footprint "0402_DSP")
      (fields
        (field (name "MANUFACTURER_PART_NUMBER") "CRCW0402100KFKEDC")
        (field (name "CASE/PACKAGE") "0402")
      )
      (libsource (lib "CS_Library") (part "Resistor 0402"))
    )
    (comp (ref "R136")
      (value "100k")
      (footprint "0402_DSP")
      (fields
        (field (name "MANUFACTURER_PART_NUMBER") "CRCW0402100KFKEDC")
        (field (name "CASE/PACKAGE") "0402")
      )
      (libsource (lib "CS_Library") (part "Resistor 0402"))
    )
    (comp (ref "R137")
      (value "100k")
      (footprint "0402_DSP")
      (fields
        (field (name "MANUFACTURER_PART_NUMBER") "CRCW0402100KFKEDC")
        (field (name "CASE/PACKAGE") "0402")
      )
      (libsource (lib "CS_Library") (part "Resistor 0402"))
    )
    (comp (ref "R138")
      (value "100k")
      (footprint "0402_DSP")
      (fields
        (field (name "MANUFACTURER_PART_NUMBER") "CRCW0402100KFKEDC")
        (field (name "CASE/PACKAGE") "0402")
      )
      (libsource (lib "CS_Library") (part "Resistor 0402"))
    )
    (comp (ref "R139")
      (value "100k")
      (footprint "0402_DSP")
      (fields
        (field (name "MANUFACTURER_PART_NUMBER") "CRCW0402100KFKEDC")
        (field (name "CASE/PACKAGE") "0402")
      )
      (libsource (lib "CS_Library") (part "Resistor 0402"))
    )
    (comp (ref "R140")
      (value "4.99")
      (footprint "0402_DSP")
      (fields
        (field (name "MANUFACTURER_PART_NUMBER") "CRCW04024R99FKEDC")
        (field (name "CASE/PACKAGE") "0402")
      )
      (libsource (lib "CS_Library") (part "Resistor 0402"))
    )
    (comp (ref "R141")
      (value "3.3k")
      (footprint "0402_DSP")
      (fields
        (field (name "MANUFACTURER_PART_NUMBER") "CRCW04023K30FKEDC")
        (field (name "CASE/PACKAGE") "0402")
      )
      (libsource (lib "CS_Library") (part "Resistor 0402"))
    )
    (comp (ref "R142")
      (value "10k")
      (footprint "0402_DSP")
      (fields
        (field (name "MANUFACTURER_PART_NUMBER") "CRCW040210K0FKEDC")
        (field (name "CASE/PACKAGE") "0402")
      )
      (libsource (lib "CS_Library") (part "Resistor 0402"))
    )
    (comp (ref "R143")
      (value "100k")
      (footprint "0402_DSP")
      (fields
        (field (name "MANUFACTURER_PART_NUMBER") "CRCW0402100KFKEDC")
        (field (name "CASE/PACKAGE") "0402")
      )
      (libsource (lib "CS_Library") (part "Resistor 0402"))
    )
    (comp (ref "R144")
      (value "100k")
      (footprint "0402_DSP")
      (fields
        (field (name "MANUFACTURER_PART_NUMBER") "CRCW0402100KFKEDC")
        (field (name "CASE/PACKAGE") "0402")
      )
      (libsource (lib "CS_Library") (part "Resistor 0402"))
    )
    (comp (ref "R145")
      (value "100k")
      (footprint "0402_DSP")
      (fields
        (field (name "MANUFACTURER_PART_NUMBER") "CRCW0402100KFKEDC")
        (field (name "CASE/PACKAGE") "0402")
      )
      (libsource (lib "CS_Library") (part "Resistor 0402"))
    )
    (comp (ref "R146")
      (value "100k")
      (footprint "0402_DSP")
      (fields
        (field (name "MANUFACTURER_PART_NUMBER") "CRCW0402100KFKEDC")
        (field (name "CASE/PACKAGE") "0402")
      )
      (libsource (lib "CS_Library") (part "Resistor 0402"))
    )
    (comp (ref "R147")
      (value "100k")
      (footprint "0402_DSP")
      (fields
        (field (name "MANUFACTURER_PART_NUMBER") "CRCW0402100KFKEDC")
        (field (name "CASE/PACKAGE") "0402")
      )
      (libsource (lib "CS_Library") (part "Resistor 0402"))
    )
    (comp (ref "R148")
      (value "100k")
      (footprint "0402_DSP")
      (fields
        (field (name "MANUFACTURER_PART_NUMBER") "CRCW0402100KFKEDC")
        (field (name "CASE/PACKAGE") "0402")
      )
      (libsource (lib "CS_Library") (part "Resistor 0402"))
    )
    (comp (ref "R149")
      (value "100k")
      (footprint "0402_DSP")
      (fields
        (field (name "MANUFACTURER_PART_NUMBER") "CRCW0402100KFKEDC")
        (field (name "CASE/PACKAGE") "0402")
      )
      (libsource (lib "CS_Library") (part "Resistor 0402"))
    )
    (comp (ref "R150")
      (value "100k")
      (footprint "0402_DSP")
      (fields
        (field (name "MANUFACTURER_PART_NUMBER") "CRCW0402100KFKEDC")
        (field (name "CASE/PACKAGE") "0402")
      )
      (libsource (lib "CS_Library") (part "Resistor 0402"))
    )
    (comp (ref "R151")
      (value "100k")
      (footprint "0402_DSP")
      (fields
        (field (name "MANUFACTURER_PART_NUMBER") "CRCW0402100KFKEDC")
        (field (name "CASE/PACKAGE") "0402")
      )
      (libsource (lib "CS_Library") (part "Resistor 0402"))
    )
    (comp (ref "R152")
      (value "100k")
      (footprint "0402_DSP")
      (fields
        (field (name "MANUFACTURER_PART_NUMBER") "CRCW0402100KFKEDC")
        (field (name "CASE/PACKAGE") "0402")
      )
      (libsource (lib "CS_Library") (part "Resistor 0402"))
    )
    (comp (ref "R153")
      (value "100k")
      (footprint "0402_DSP")
      (fields
        (field (name "MANUFACTURER_PART_NUMBER") "CRCW0402100KFKEDC")
        (field (name "CASE/PACKAGE") "0402")
      )
      (libsource (lib "CS_Library") (part "Resistor 0402"))
    )
    (comp (ref "R154")
      (value "100k")
      (footprint "0402_DSP")
      (fields
        (field (name "MANUFACTURER_PART_NUMBER") "CRCW0402100KFKEDC")
        (field (name "CASE/PACKAGE") "0402")
      )
      (libsource (lib "CS_Library") (part "Resistor 0402"))
    )
    (comp (ref "R155")
      (value "100k")
      (footprint "0402_DSP")
      (fields
        (field (name "MANUFACTURER_PART_NUMBER") "CRCW0402100KFKEDC")
        (field (name "CASE/PACKAGE") "0402")
      )
      (libsource (lib "CS_Library") (part "Resistor 0402"))
    )
    (comp (ref "R156")
      (value "100k")
      (footprint "0402_DSP")
      (fields
        (field (name "MANUFACTURER_PART_NUMBER") "CRCW0402100KFKEDC")
        (field (name "CASE/PACKAGE") "0402")
      )
      (libsource (lib "CS_Library") (part "Resistor 0402"))
    )
    (comp (ref "R157")
      (value "100k")
      (footprint "0402_DSP")
      (fields
        (field (name "MANUFACTURER_PART_NUMBER") "CRCW0402100KFKEDC")
        (field (name "CASE/PACKAGE") "0402")
      )
      (libsource (lib "CS_Library") (part "Resistor 0402"))
    )
    (comp (ref "R158")
      (value "100k")
      (footprint "0402_DSP")
      (fields
        (field (name "MANUFACTURER_PART_NUMBER") "CRCW0402100KFKEDC")
        (field (name "CASE/PACKAGE") "0402")
      )
      (libsource (lib "CS_Library") (part "Resistor 0402"))
    )
    (comp (ref "R161")
      (value "10k")
      (footprint "0402_DSP")
      (fields
        (field (name "MANUFACTURER_PART_NUMBER") "CRCW040210K0FKEDC")
        (field (name "CASE/PACKAGE") "0402")
      )
      (libsource (lib "CS_Library") (part "Resistor 0402"))
    )
    (comp (ref "R163")
      (value "1k")
      (footprint "0402_DSP")
      (fields
        (field (name "MANUFACTURER_PART_NUMBER") "CRCW04021K00FKEDC")
        (field (name "CASE/PACKAGE") "0402")
      )
      (libsource (lib "CS_Library") (part "Resistor 0402"))
    )
    (comp (ref "R164")
      (value "17k")
      (footprint "0402_DSP")
      (fields (field (name "CASE/PACKAGE") "0402"))
      (libsource (lib "CS_Library") (part "Resistor 0402"))
    )
    (comp (ref "R172")
      (value "100k")
      (footprint "0402_DSP")
      (fields
        (field (name "MANUFACTURER_PART_NUMBER") "CRCW0402100KFKEDC")
        (field (name "CASE/PACKAGE") "0402")
      )
      (libsource (lib "CS_Library") (part "Resistor 0402"))
    )
    (comp (ref "R173")
      (value "3.3k")
      (footprint "0402_DSP")
      (fields
        (field (name "MANUFACTURER_PART_NUMBER") "CRCW0402100KFKEDC")
        (field (name "CASE/PACKAGE") "0402")
      )
      (libsource (lib "CS_Library") (part "Resistor 0402"))
    )
    (comp (ref "R174")
      (value "100k")
      (footprint "0402_DSP")
      (fields
        (field (name "MANUFACTURER_PART_NUMBER") "CRCW0402100KFKEDC")
        (field (name "CASE/PACKAGE") "0402")
      )
      (libsource (lib "CS_Library") (part "Resistor 0402"))
    )
    (comp (ref "R175")
      (value "3.3k")
      (footprint "0402_DSP")
      (fields
        (field (name "MANUFACTURER_PART_NUMBER") "CRCW0402100KFKEDC")
        (field (name "CASE/PACKAGE") "0402")
      )
      (libsource (lib "CS_Library") (part "Resistor 0402"))
    )
    (comp (ref "R182")
      (value "100k")
      (footprint "0402_DSP")
      (fields
        (field (name "MANUFACTURER_PART_NUMBER") "CRCW0402100KFKEDC")
        (field (name "CASE/PACKAGE") "0402")
      )
      (libsource (lib "CS_Library") (part "Resistor 0402"))
    )
    (comp (ref "R183")
      (value "100k")
      (footprint "0402_DSP")
      (fields
        (field (name "MANUFACTURER_PART_NUMBER") "CRCW0402100KFKEDC")
        (field (name "CASE/PACKAGE") "0402")
      )
      (libsource (lib "CS_Library") (part "Resistor 0402"))
    )
    (comp (ref "R184")
      (value "3.3k")
      (footprint "0402_DSP")
      (fields
        (field (name "MANUFACTURER_PART_NUMBER") "CRCW0402100KFKEDC")
        (field (name "CASE/PACKAGE") "0402")
      )
      (libsource (lib "CS_Library") (part "Resistor 0402"))
    )
    (comp (ref "R188")
      (value "10k")
      (footprint "0402_DSP")
      (fields
        (field (name "MANUFACTURER_PART_NUMBER") "CRCW0402100KFKEDC")
        (field (name "CASE/PACKAGE") "0402")
      )
      (libsource (lib "CS_Library") (part "Resistor 0402"))
    )
    (comp (ref "R189")
      (value "49.9")
      (footprint "0402_DSP")
      (fields (field (name "CASE/PACKAGE") "0402"))
      (libsource (lib "CS_Library") (part "Resistor 0402"))
    )
    (comp (ref "R190")
      (value "49.9")
      (footprint "0402_DSP")
      (fields (field (name "CASE/PACKAGE") "0402"))
      (libsource (lib "CS_Library") (part "Resistor 0402"))
    )
    (comp (ref "TP1")
      (value "~")
      (footprint "TestPoint_4952")
      (fields (field (name "MOUSER_PART_NUMBER") "534-4952"))
      (libsource (lib "CS_Library") (part "Test_Point"))
    )
    (comp (ref "TP2")
      (value "~")
      (footprint "TestPoint_4952")
      (fields (field (name "MOUSER_PART_NUMBER") "534-4952"))
      (libsource (lib "CS_Library") (part "Test_Point"))
    )
    (comp (ref "TP3")
      (value "~")
      (footprint "TestPoint_4952")
      (fields (field (name "MOUSER_PART_NUMBER") "534-4952"))
      (libsource (lib "CS_Library") (part "Test_Point"))
    )
    (comp (ref "TP4")
      (value "~")
      (footprint "TestPoint_4952")
      (fields (field (name "MOUSER_PART_NUMBER") "534-4952"))
      (libsource (lib "CS_Library") (part "Test_Point"))
    )
    (comp (ref "TP5")
      (value "~")
      (footprint "TestPoint_4952")
      (fields (field (name "MOUSER_PART_NUMBER") "534-4952"))
      (libsource (lib "CS_Library") (part "Test_Point"))
    )
    (comp (ref "TP6")
      (value "~")
      (footprint "TestPoint_4952")
      (fields (field (name "MOUSER_PART_NUMBER") "534-4952"))
      (libsource (lib "CS_Library") (part "Test_Point"))
    )
    (comp (ref "TP7")
      (value "~")
      (footprint "TestPoint_4952")
      (fields (field (name "MOUSER_PART_NUMBER") "534-4952"))
      (libsource (lib "CS_Library") (part "Test_Point"))
    )
    (comp (ref "TP8")
      (value "~")
      (footprint "TestPoint_4952")
      (fields (field (name "MOUSER_PART_NUMBER") "534-4952"))
      (libsource (lib "CS_Library") (part "Test_Point"))
    )
    (comp (ref "TP9")
      (value "~")
      (footprint "TestPoint_4952")
      (fields (field (name "MOUSER_PART_NUMBER") "534-4952"))
      (libsource (lib "CS_Library") (part "Test_Point"))
    )
    (comp (ref "TP10")
      (value "~")
      (footprint "TestPoint_4952")
      (fields (field (name "MOUSER_PART_NUMBER") "534-4952"))
      (libsource (lib "CS_Library") (part "Test_Point"))
    )
    (comp (ref "TP16")
      (value "~")
      (footprint "TestPoint_4952")
      (fields (field (name "MOUSER_PART_NUMBER") "534-4952"))
      (libsource (lib "CS_Library") (part "Test_Point"))
    )
    (comp (ref "TP17")
      (value "~")
      (footprint "TestPoint_4952")
      (fields (field (name "MOUSER_PART_NUMBER") "534-4952"))
      (libsource (lib "CS_Library") (part "Test_Point"))
    )
    (comp (ref "TP18")
      (value "~")
      (footprint "TestPoint_4952")
      (fields (field (name "MOUSER_PART_NUMBER") "534-4952"))
      (libsource (lib "CS_Library") (part "Test_Point"))
    )
    (comp (ref "TP19")
      (value "~")
      (footprint "TestPoint_4952")
      (fields (field (name "MOUSER_PART_NUMBER") "534-4952"))
      (libsource (lib "CS_Library") (part "Test_Point"))
    )
    (comp (ref "U1")
      (value "IC BUFFER INVERT 5.5V SOT23-5")
      (footprint "CS_Library:SOT95P280X145-5N")
      (description "Integrated Circuit: Buffer, Inverting 1 Element 1 Bit per Element 3-State Output SOT-23-5")
      (fields
        (field (name "MANUFACTURER_PART_NUMBER") "SN74LVC1G240DBVR")
        (field (name "MOUSER PART NUMBER") "595-SN74LVC1G240DBVR")
      )
      (libsource (lib "") (part "SN74LVC1G240DBVR_1"))
    )
    (comp (ref "U2")
      (value "IC TRANSLTR BIDIRECTIONAL 8VSSOP")
      (footprint "CS_Library:SOP50P310X90-8N")
      (description "Integrated Circuit: Voltage Level Translator Bidirectional 1 Circuit 2 Channel 24Mbps 8-VSSOP")
      (fields
        (field (name "MANUFACTURER_PART_NUMBER") "TXS0102QDCURQ1")
        (field (name "MOUSER PART NUMBER") "595-TXS0102QDCURQ1")
      )
      (libsource (lib "CS_Library") (part "TXS0102QDCURQ1"))
    )
    (comp (ref "U3")
      (value "74LVC1G14W5-7")
      (footprint "FP-SOT25-MFG")
      (description "IC INVERTER SCHMITT 1CH SOT25")
      (fields
        (field (name "MANUFACTURER") "Diodes Inc.")
        (field (name "OCTOPART") "https://octopart.com/74lvc1g14w5-7-diodes+inc.-19991867")
        (field (name "CASE/PACKAGE") "*")
      )
      (libsource (lib "") (part "164d2a6a28db1e3f567e29a018e26a0_1"))
    )
    (comp (ref "U4")
      (value "MCP2542FD-H_SN")
      (footprint "CS_Library:SOIC127P600X175-8N")
      (description "Integrated Circuit")
      (fields
        (field (name "MANUFACTURER_PART_NUMBER") "MCP2542FD-H/SN")
        (field (name "MOUSER PART NUMBER") "579-MCP2542FD-H/SN")
        (field (name "CASE/PACKAGE") "*")
      )
      (libsource (lib "CS_Library") (part "MCP2542FD-H_SN"))
    )
    (comp (ref "U5")
      (value "LTC4412HVIS6#TRPBF")
      (footprint "LT-S6-6-TSOT-23_L")
      (fields (field (name "MANUFACTURER") "Linear Technology") (field (name "CASE/PACKAGE") "*"))
      (libsource (lib "Altium Content Vault") (part "LT-LTC4412_HV-S6-6"))
    )
    (comp (ref "U6")
      (value "IC REG BUCK ADJ 1A DL 16MSOP")
      (footprint "CS_Library:SOP50P490X110-17N")
      (fields
        (field (name "MANUFACTURER_PART_NUMBER") "LTC3622HMSE-2#PBF")
        (field (name "MOUSER PART NUMBER") "584-LTC3622HMSE-2PBF")
      )
      (libsource (lib "CS_Library") (part "LTC3622HMSE-2#PBF"))
    )
    (comp (ref "U7")
      (value "74LVC1G14W5-7")
      (footprint "FP-SOT25-MFG")
      (description "IC INVERTER SCHMITT 1CH SOT25")
      (fields
        (field (name "MANUFACTURER") "Diodes Inc.")
        (field (name "OCTOPART") "https://octopart.com/74lvc1g14w5-7-diodes+inc.-19991867")
        (field (name "CASE/PACKAGE") "*")
      )
      (libsource (lib "Altium Content Vault") (part "164d2a6a28db1e3f567e29a018e26a0"))
    )
    (comp (ref "U8")
      (value "LTC4412HVIS6#TRPBF")
      (footprint "LT-S6-6-TSOT-23_L")
      (fields (field (name "MANUFACTURER") "Linear Technology") (field (name "CASE/PACKAGE") "*"))
      (libsource (lib "Altium Content Vault") (part "LT-LTC4412_HV-S6-6"))
    )
    (comp (ref "U9")
      (value "SENSOR Magnetometer WHEAT BRDG 8SOIC")
      (footprint "SOIC127P600X175-8N")
      (description "Integrated Circuit: Magnetoresistive Sensor Single Axis 8-SOIC")
      (fields (field (name "MANUFACTURER_PART_NUMBER") "AAH002-02E"))
      (libsource (lib "CS_Library") (part "AAH002-02E"))
    )
    (comp (ref "U10")
      (value "IC INST AMP 1 CIRCUIT 8MSOP")
      (footprint "CS_Library:SOP65P490X110-8N")
      (description "Integrated Circuit: Instrumentation Amplifier 1 Circuit Rail-to-Rail 8-MSOP")
      (fields
        (field (name "MANUFACTURER_PART_NUMBER") "AD8226BRMZ-R7")
        (field (name "MOUSER PART NUMBER") "584-AD8226BRMZ-R7")
      )
      (libsource (lib "CS_Library") (part "AD8226BRMZ-R7"))
    )
    (comp (ref "U11")
      (value "LTC4412HVIS6#TRPBF")
      (footprint "LT-S6-6-TSOT-23_L")
      (fields (field (name "MANUFACTURER") "Linear Technology") (field (name "CASE/PACKAGE") "*"))
      (libsource (lib "Altium Content Vault") (part "LT-LTC4412_HV-S6-6"))
    )
    (comp (ref "U12")
      (value "LTC4412HVIS6#TRPBF")
      (footprint "LT-S6-6-TSOT-23_L")
      (fields (field (name "MANUFACTURER") "Linear Technology") (field (name "CASE/PACKAGE") "*"))
      (libsource (lib "Altium Content Vault") (part "LT-LTC4412_HV-S6-6"))
    )
    (comp (ref "U13")
      (value "ADXL373Z_Eval")
      (footprint "ADXL373Z_EVAL")
      (libsource (lib "CS_Library") (part "ADXL373Z_Eval"))
    )
    (comp (ref "U14")
      (value "MMC5983_EVAL")
      (footprint "MMC5983_EVAL")
      (libsource (lib "CS_Library") (part "MMC5983_EVAL"))
    )
    (comp (ref "U15")
      (value "MT25QL128ABA8ESF-0AAT")
      (footprint "CS_Library:SOIC127P1032X265-16N")
      (description "Integrated Circuit")
      (fields (field (name "MOUSER PART NUMBER") "340-279635-TRAY"))
      (libsource (lib "CS_Library") (part "MT25QL128ABA8ESF-0AAT"))
    )
    (comp (ref "U16")
      (value "MCP6402-H/SN")
      (footprint "SOIC-SN8_L")
      (description "None")
      (fields (field (name "CASE/PACKAGE") "*"))
      (libsource (lib "Altium Content Vault") (part "AMP-OPA-MCP6402-IL8"))
    )
    (comp (ref "U17")
      (value "MT25QL128ABA8ESF-0AAT")
      (footprint "CS_Library:SOIC127P1032X265-16N")
      (description "Integrated Circuit")
      (fields (field (name "MOUSER PART NUMBER") "340-279635-TRAY"))
      (libsource (lib "CS_Library") (part "MT25QL128ABA8ESF-0AAT"))
    )
    (comp (ref "U18")
      (value "MT25QL128ABA8ESF-0AAT")
      (footprint "CS_Library:SOIC127P1032X265-16N")
      (description "Integrated Circuit")
      (fields (field (name "MOUSER PART NUMBER") "340-279635-TRAY"))
      (libsource (lib "CS_Library") (part "MT25QL128ABA8ESF-0AAT"))
    )
    (comp (ref "U19")
      (value "MT25QL128ABA8ESF-0AAT")
      (footprint "CS_Library:SOIC127P1032X265-16N")
      (description "Integrated Circuit")
      (fields (field (name "MOUSER PART NUMBER") "340-279635-TRAY"))
      (libsource (lib "CS_Library") (part "MT25QL128ABA8ESF-0AAT"))
    )
    (comp (ref "U20")
      (value "IC OPAMP GP 1 CIRCUIT SOT23-5")
      (footprint "CS_Library:SOT95P270X145-5N")
      (description "Integrated Circuit: General Purpose Amplifier 1 Circuit Rail-to-Rail SOT-23-5")
      (fields
        (field (name "MANUFACTURER_PART_NUMBER") "MCP6401T-E/OT")
        (field (name "MOUSER PART NUMBER") "579-MCP6401T-E/OT")
        (field (name "ARROW PART NUMBER") "MCP6401T-E/OT")
      )
      (libsource (lib "CS_Library") (part "MCP6401T-E_OT"))
    )
    (comp (ref "U21")
      (value "MT25QL128ABA8ESF-0AAT")
      (footprint "CS_Library:SOIC127P1032X265-16N")
      (description "Integrated Circuit")
      (fields (field (name "MOUSER PART NUMBER") "340-279635-TRAY"))
      (libsource (lib "CS_Library") (part "MT25QL128ABA8ESF-0AAT"))
    )
    (comp (ref "U22")
      (value "MT25QL128ABA8ESF-0AAT")
      (footprint "CS_Library:SOIC127P1032X265-16N")
      (description "Integrated Circuit")
      (fields (field (name "MOUSER PART NUMBER") "340-279635-TRAY"))
      (libsource (lib "CS_Library") (part "MT25QL128ABA8ESF-0AAT"))
    )
    (comp (ref "U23")
      (value "MT25QL128ABA8ESF-0AAT")
      (footprint "CS_Library:SOIC127P1032X265-16N")
      (description "Integrated Circuit")
      (fields (field (name "MOUSER PART NUMBER") "340-279635-TRAY"))
      (libsource (lib "CS_Library") (part "MT25QL128ABA8ESF-0AAT"))
    )
    (comp (ref "U24")
      (value "IC SWITCH SPDTX1 600MOHM SC70-6")
      (footprint "CS_Library:SOT65P210X110-6N")
      (description "Integrated Circuit: 1 Circuit IC Switch 2:1 600mOhm SC-70-6")
      (fields
        (field (name "MANUFACTURER_PART_NUMBER") "ADG849YKSZ-REEL")
        (field (name "MOUSER PART NUMBER") "584-ADG849YKSZ-R")
      )
      (libsource (lib "CS_Library") (part "ADG849YKSZ-REEL"))
    )
    (comp (ref "U25")
      (value "MT25QL128ABA8ESF-0AAT")
      (footprint "CS_Library:SOIC127P1032X265-16N")
      (description "Integrated Circuit")
      (fields (field (name "MOUSER PART NUMBER") "340-279635-TRAY"))
      (libsource (lib "CS_Library") (part "MT25QL128ABA8ESF-0AAT"))
    )
    (comp (ref "U26")
      (value "MCP6402-H/SN")
      (footprint "SOIC-SN8_L")
      (description "None")
      (fields (field (name "CASE/PACKAGE") "*"))
      (libsource (lib "Altium Content Vault") (part "AMP-OPA-MCP6402-IL8"))
    )
    (comp (ref "U27")
      (value "IC BUFFER INVERT 5.5V SOT23-5")
      (footprint "CS_Library:SOT95P280X145-5N")
      (description "Integrated Circuit: Buffer, Inverting 1 Element 1 Bit per Element 3-State Output SOT-23-5")
      (fields
        (field (name "MANUFACTURER_PART_NUMBER") "SN74LVC1G240DBVR")
        (field (name "MOUSER PART NUMBER") "595-SN74LVC1G240DBVR")
      )
      (libsource (lib "CS_Library") (part "SN74LVC1G240DBVR"))
    )
    (comp (ref "U28")
      (value "MT25QL128ABA8ESF-0AAT")
      (footprint "CS_Library:SOIC127P1032X265-16N")
      (description "Integrated Circuit")
      (fields (field (name "MOUSER PART NUMBER") "340-279635-TRAY"))
      (libsource (lib "CS_Library") (part "MT25QL128ABA8ESF-0AAT"))
    )
    (comp (ref "U29")
      (value "MT25QL128ABA8ESF-0AAT")
      (footprint "CS_Library:SOIC127P1032X265-16N")
      (description "Integrated Circuit")
      (fields (field (name "MOUSER PART NUMBER") "340-279635-TRAY"))
      (libsource (lib "CS_Library") (part "MT25QL128ABA8ESF-0AAT"))
    )
    (comp (ref "U30")
      (value "MT25QL128ABA8ESF-0AAT")
      (footprint "CS_Library:SOIC127P1032X265-16N")
      (description "Integrated Circuit")
      (fields (field (name "MOUSER PART NUMBER") "340-279635-TRAY"))
      (libsource (lib "CS_Library") (part "MT25QL128ABA8ESF-0AAT"))
    )
    (comp (ref "U31")
      (value "MT25QL128ABA8ESF-0AAT")
      (footprint "CS_Library:SOIC127P1032X265-16N")
      (description "Integrated Circuit")
      (fields (field (name "MOUSER PART NUMBER") "340-279635-TRAY"))
      (libsource (lib "CS_Library") (part "MT25QL128ABA8ESF-0AAT"))
    )
    (comp (ref "U32")
      (value "IC VREF SERIES 0.08% 8SOIC")
      (footprint "CS_Library:SOIC127P600X175-8N")
      (description "Integrated Circuit:Series Voltage Reference IC Fixed 2.5V V ±0.08% 5 mA 8-SOIC")
      (fields
        (field (name "MANUFACTURER_PART_NUMBER") "ADR291ERZ")
        (field (name "MOUSER PART NUMBER") "584-ADR291ERZ")
      )
      (libsource (lib "CS_Library") (part "ADR291ERZ"))
    )
    (comp (ref "U33")
      (value "IC ADC 12BIT SAR 20TSSOP")
      (footprint "CS_Library:SOP65P640X120-20N")
      (description "Integrated Circuit:12 Bit Analog to Digital Converter 8 Input 1 SAR 20-TSSOP")
      (fields
        (field (name "MANUFACTURER_PART_NUMBER") "AD7928WBRUZ-REEL")
        (field (name "MOUSER PART NUMBER") "584-AD7928WBRUZ-R")
      )
      (libsource (lib "CS_Library") (part "AD7928WBRUZ-REEL"))
    )
    (comp (ref "U34")
      (value "MT25QL128ABA8ESF-0AAT")
      (footprint "CS_Library:SOIC127P1032X265-16N")
      (description "Integrated Circuit")
      (fields (field (name "MOUSER PART NUMBER") "340-279635-TRAY"))
      (libsource (lib "CS_Library") (part "MT25QL128ABA8ESF-0AAT"))
    )
    (comp (ref "U35")
      (value "MT25QL128ABA8ESF-0AAT")
      (footprint "CS_Library:SOIC127P1032X265-16N")
      (description "Integrated Circuit")
      (fields (field (name "MOUSER PART NUMBER") "340-279635-TRAY"))
      (libsource (lib "CS_Library") (part "MT25QL128ABA8ESF-0AAT"))
    )
    (comp (ref "U36")
      (value "MT25QL128ABA8ESF-0AAT")
      (footprint "CS_Library:SOIC127P1032X265-16N")
      (description "Integrated Circuit")
      (fields (field (name "MOUSER PART NUMBER") "340-279635-TRAY"))
      (libsource (lib "CS_Library") (part "MT25QL128ABA8ESF-0AAT"))
    )
    (comp (ref "U37")
      (value "MT25QL128ABA8ESF-0AAT")
      (footprint "CS_Library:SOIC127P1032X265-16N")
      (description "Integrated Circuit")
      (fields (field (name "MOUSER PART NUMBER") "340-279635-TRAY"))
      (libsource (lib "CS_Library") (part "MT25QL128ABA8ESF-0AAT"))
    )
    (comp (ref "U38")
      (value "ADG732BCPZ")
      (footprint "CS_Library:QFN50P700X700X100-49N-D")
      (description "Integrated Circuit")
      (fields (field (name "MOUSER PART NUMBER") "584-ADG732BCPZ") (field (name "CASE/PACKAGE") "*"))
      (libsource (lib "CS_Library") (part "ADG732BCPZ"))
    )
    (comp (ref "U39")
      (value "23LC1024-E/SN")
      (footprint "FP-C04-057-SN-IPC_A")
      (description "IC SRAM 1MBIT SPI/QUAD I/O 8SOIC")
      (fields (field (name "CASE/PACKAGE") "*"))
      (libsource (lib "Altium Content Vault") (part "4e1693c1fb2d66f1849972f71519c99"))
    )
    (comp (ref "U40")
      (value "MT25QL128ABA8ESF-0AAT")
      (footprint "CS_Library:SOIC127P1032X265-16N")
      (description "Integrated Circuit")
      (fields (field (name "MOUSER PART NUMBER") "340-279635-TRAY"))
      (libsource (lib "CS_Library") (part "MT25QL128ABA8ESF-0AAT"))
    )
    (comp (ref "U41")
      (value "MT25QL128ABA8ESF-0AAT")
      (footprint "CS_Library:SOIC127P1032X265-16N")
      (description "Integrated Circuit")
      (fields (field (name "MOUSER PART NUMBER") "340-279635-TRAY"))
      (libsource (lib "CS_Library") (part "MT25QL128ABA8ESF-0AAT"))
    )
    (comp (ref "U42")
      (value "MT25QL128ABA8ESF-0AAT")
      (footprint "CS_Library:SOIC127P1032X265-16N")
      (description "Integrated Circuit")
      (fields (field (name "MOUSER PART NUMBER") "340-279635-TRAY"))
      (libsource (lib "CS_Library") (part "MT25QL128ABA8ESF-0AAT"))
    )
    (comp (ref "U43")
      (value "MT25QL128ABA8ESF-0AAT")
      (footprint "CS_Library:SOIC127P1032X265-16N")
      (description "Integrated Circuit")
      (fields (field (name "MOUSER PART NUMBER") "340-279635-TRAY"))
      (libsource (lib "CS_Library") (part "MT25QL128ABA8ESF-0AAT"))
    )
    (comp (ref "U44")
      (value "DSPIC33CK512MP605-I/PT")
      (footprint "QFP50P900X900X120-48N")
      (description "MCU")
      (fields (field (name "MOUSER_PART_NUMBER") "579-D33CK512MP605IPT") (field (name "CASE/PACKAGE") "*"))
      (libsource (lib "DSPIC33CK512MP605-I_PT") (part "DSPIC33CK512MP605-I_PT"))
    )
    (comp (ref "U45")
      (value "MT25QL128ABA8ESF-0AAT")
      (footprint "CS_Library:SOIC127P1032X265-16N")
      (description "Integrated Circuit")
      (fields (field (name "MOUSER PART NUMBER") "340-279635-TRAY"))
      (libsource (lib "CS_Library") (part "MT25QL128ABA8ESF-0AAT"))
    )
    (comp (ref "U46")
      (value "MT25QL128ABA8ESF-0AAT")
      (footprint "CS_Library:SOIC127P1032X265-16N")
      (description "Integrated Circuit")
      (fields (field (name "MOUSER PART NUMBER") "340-279635-TRAY"))
      (libsource (lib "CS_Library") (part "MT25QL128ABA8ESF-0AAT"))
    )
    (comp (ref "U47")
      (value "MT25QL128ABA8ESF-0AAT")
      (footprint "CS_Library:SOIC127P1032X265-16N")
      (description "Integrated Circuit")
      (fields (field (name "MOUSER PART NUMBER") "340-279635-TRAY"))
      (libsource (lib "CS_Library") (part "MT25QL128ABA8ESF-0AAT"))
    )
    (comp (ref "U48")
      (value "MT25QL128ABA8ESF-0AAT")
      (footprint "CS_Library:SOIC127P1032X265-16N")
      (description "Integrated Circuit")
      (fields (field (name "MOUSER PART NUMBER") "340-279635-TRAY"))
      (libsource (lib "CS_Library") (part "MT25QL128ABA8ESF-0AAT"))
    )
    (comp (ref "U50")
      (value "MCP6402-H/SN")
      (footprint "SOIC-SN8_L")
      (description "None")
      (fields (field (name "CASE/PACKAGE") "*"))
      (libsource (lib "Altium Content Vault") (part "AMP-OPA-MCP6402-IL8"))
    )
    (comp (ref "Y1")
      (value "Oscillators 8Mhz")
      (footprint "SIT8920BM1133S8000000G")
      (fields
        (field (name "MANUFACTURER_PART_NUMBER") "SIT8920BM-11-33S-8.000000G")
        (field (name "CASE/PACKAGE") "*")
      )
      (libsource (lib "SIT8920BM-11-33S-8") (part "SIT8920BM-11-33S-8.000000G"))
    )
  )
  (nets
    (net (code "1") (name "/3V3_MAG_1") (class "Default")
      (node (ref "C141") (pin "1") (pinfunction "1_1") (pintype "passive"))
      (node (ref "C46") (pin "2") (pinfunction "2_2") (pintype "passive"))
      (node (ref "C47") (pin "1") (pinfunction "1_1") (pintype "passive"))
      (node (ref "C49") (pin "1") (pinfunction "1_1") (pintype "passive"))
      (node (ref "Q11") (pin "2") (pinfunction "D2_1_2") (pintype "passive"))
      (node (ref "Q11") (pin "3") (pinfunction "D2_2_3") (pintype "passive"))
      (node (ref "R183") (pin "2") (pinfunction "2_2") (pintype "passive"))
      (node (ref "R96") (pin "1") (pinfunction "1_1") (pintype "passive"))
      (node (ref "U10") (pin "8") (pinfunction "+VS_8") (pintype "passive"))
      (node (ref "U20") (pin "5") (pinfunction "VDD_5") (pintype "passive"))
      (node (ref "U9") (pin "8") (pinfunction "VDD_8") (pintype "passive"))
    )
    (net (code "2") (name "/3V3_SWH") (class "Default")
      (node (ref "C129") (pin "1") (pinfunction "1_1") (pintype "passive"))
      (node (ref "Q10") (pin "2") (pinfunction "D2_1_2") (pintype "passive"))
      (node (ref "Q10") (pin "3") (pinfunction "D2_2_3") (pintype "passive"))
      (node (ref "R99") (pin "2") (pinfunction "2_2") (pintype "passive"))
      (node (ref "TP9") (pin "1") (pinfunction "1_1") (pintype "passive"))
      (node (ref "U2") (pin "6") (pinfunction "OE_6") (pintype "passive"))
    )
    (net (code "3") (name "/3V3_SWL") (class "Default")
      (node (ref "Q9") (pin "3") (pinfunction "C_3") (pintype "passive"))
      (node (ref "R100") (pin "1") (pinfunction "1_1") (pintype "passive"))
      (node (ref "TP10") (pin "1") (pinfunction "1_1") (pintype "passive"))
      (node (ref "U38") (pin "22") (pinfunction "~{EN}_22") (pintype "passive"))
    )
    (net (code "4") (name "/5V_IN") (class "Default")
      (node (ref "F5") (pin "2") (pinfunction "2_2") (pintype "passive"))
      (node (ref "J1") (pin "7") (pinfunction "7_7") (pintype "passive"))
    )
    (net (code "5") (name "/5V_IN_FUSED") (class "Default")
      (node (ref "C52") (pin "2") (pinfunction "2_2") (pintype "passive"))
      (node (ref "C53") (pin "1") (pinfunction "1_1") (pintype "passive"))
      (node (ref "F5") (pin "1") (pinfunction "1_1") (pintype "passive"))
      (node (ref "Q6") (pin "3") (pinfunction "DRAIN_3") (pintype "passive"))
      (node (ref "R39") (pin "2") (pinfunction "2_2") (pintype "passive"))
      (node (ref "U12") (pin "1") (pinfunction "VIN_1") (pintype "power_in"))
    )
    (net (code "6") (name "/5V_SW") (class "Default")
      (node (ref "C10") (pin "1") (pinfunction "1_1") (pintype "passive"))
      (node (ref "C128") (pin "1") (pinfunction "1_1") (pintype "passive"))
      (node (ref "C9") (pin "1") (pinfunction "1_1") (pintype "passive"))
      (node (ref "J5") (pin "1") (pinfunction "1_1") (pintype "passive"))
      (node (ref "J58") (pin "1") (pinfunction "1_1") (pintype "passive"))
      (node (ref "Q7") (pin "2") (pinfunction "D2_1_2") (pintype "passive"))
      (node (ref "Q7") (pin "3") (pinfunction "D2_2_3") (pintype "passive"))
      (node (ref "R4") (pin "2") (pinfunction "2_2") (pintype "passive"))
      (node (ref "R5") (pin "1") (pinfunction "1_1") (pintype "passive"))
      (node (ref "R98") (pin "2") (pinfunction "2_2") (pintype "passive"))
      (node (ref "TP8") (pin "1") (pinfunction "1_1") (pintype "passive"))
      (node (ref "U1") (pin "1") (pinfunction "~{OE}_1") (pintype "passive"))
      (node (ref "U4") (pin "3") (pinfunction "VDD_3") (pintype "passive"))
    )
    (net (code "7") (name "/ADC_REF_2500") (class "Default")
      (node (ref "C50") (pin "2") (pinfunction "2_2") (pintype "passive"))
      (node (ref "TP1") (pin "1") (pinfunction "1_1") (pintype "passive"))
      (node (ref "U32") (pin "6") (pinfunction "VOUT_6") (pintype "passive"))
      (node (ref "U33") (pin "7") (pinfunction "REFIN_7") (pintype "passive"))
    )
    (net (code "8") (name "/BAT1") (class "Default")
      (node (ref "F2") (pin "2") (pinfunction "2_2") (pintype "passive"))
      (node (ref "J1") (pin "1") (pinfunction "1_1") (pintype "passive"))
      (node (ref "J1") (pin "2") (pinfunction "2_2") (pintype "passive"))
    )
    (net (code "9") (name "/BAT2") (class "Default")
      (node (ref "F3") (pin "2") (pinfunction "2_2") (pintype "passive"))
      (node (ref "J1") (pin "3") (pinfunction "3_3") (pintype "passive"))
      (node (ref "J1") (pin "4") (pinfunction "4_4") (pintype "passive"))
    )
    (net (code "10") (name "/BAT3") (class "Default")
      (node (ref "F4") (pin "2") (pinfunction "2_2") (pintype "passive"))
      (node (ref "J1") (pin "5") (pinfunction "5_5") (pintype "passive"))
      (node (ref "J1") (pin "6") (pinfunction "6_6") (pintype "passive"))
    )
    (net (code "11") (name "/CANH") (class "Default")
      (node (ref "C6") (pin "1") (pinfunction "1_1") (pintype "passive"))
      (node (ref "D2") (pin "1") (pinfunction "K1_1") (pintype "passive"))
      (node (ref "J8") (pin "1") (pinfunction "1_1") (pintype "passive"))
      (node (ref "R3") (pin "2") (pinfunction "2_2") (pintype "passive"))
      (node (ref "U4") (pin "7") (pinfunction "CANH_7") (pintype "passive"))
    )
    (net (code "12") (name "/CANL") (class "Default")
      (node (ref "C15") (pin "1") (pinfunction "1_1") (pintype "passive"))
      (node (ref "D2") (pin "2") (pinfunction "K2_2") (pintype "passive"))
      (node (ref "J7") (pin "1") (pinfunction "1_1") (pintype "passive"))
      (node (ref "R3") (pin "1") (pinfunction "1_1") (pintype "passive"))
      (node (ref "U4") (pin "6") (pinfunction "CANL_6") (pintype "passive"))
    )
    (net (code "13") (name "/CAN_Enable") (class "Default")
      (node (ref "R7") (pin "2") (pinfunction "2_2") (pintype "passive"))
      (node (ref "U44") (pin "6") (pinfunction "ANN4/CMP5B/RP77/RD13_6") (pintype "passive"))
    )
    (net (code "14") (name "/CAN_IN_FUSED") (class "Default")
      (node (ref "C11") (pin "2") (pinfunction "2_2") (pintype "passive"))
      (node (ref "C5") (pin "2") (pinfunction "2_2") (pintype "passive"))
      (node (ref "C7") (pin "2") (pinfunction "2_2") (pintype "passive"))
      (node (ref "C8") (pin "1") (pinfunction "1_1") (pintype "passive"))
      (node (ref "D1") (pin "3") (pinfunction "A2_3") (pintype "passive"))
      (node (ref "D1") (pin "4") (pinfunction "A1_4") (pintype "passive"))
      (node (ref "R2") (pin "1") (pinfunction "1_1") (pintype "passive"))
      (node (ref "R44") (pin "2") (pinfunction "2_2") (pintype "passive"))
    )
    (net (code "15") (name "/CAN_PWR") (class "Default")
      (node (ref "F1") (pin "2") (pinfunction "2_2") (pintype "passive"))
      (node (ref "J6") (pin "1") (pinfunction "1_1") (pintype "passive"))
    )
    (net (code "16") (name "/CAN_RXD") (class "Default")
      (node (ref "U4") (pin "1") (pinfunction "TXD_1") (pintype "passive"))
      (node (ref "U44") (pin "2") (pinfunction "RP47/PWM1L/RB15_2") (pintype "passive"))
    )
    (net (code "17") (name "/CAN_TXD") (class "Default")
      (node (ref "U4") (pin "4") (pinfunction "RXD_4") (pintype "passive"))
      (node (ref "U44") (pin "1") (pinfunction "RP46/PWM1H/RB14_1") (pintype "passive"))
    )
    (net (code "18") (name "/COM_OVERRIDE") (class "Default")
      (node (ref "Q4") (pin "3") (pinfunction "C_3") (pintype "passive"))
      (node (ref "R8") (pin "2") (pinfunction "2_2") (pintype "passive"))
      (node (ref "TP2") (pin "1") (pinfunction "1_1") (pintype "passive"))
      (node (ref "U24") (pin "1") (pinfunction "IN_1") (pintype "passive"))
      (node (ref "U27") (pin "1") (pinfunction "~{OE}_1") (pintype "passive"))
    )
    (net (code "19") (name "/COM_SW") (class "Default")
      (node (ref "R10") (pin "2") (pinfunction "2_2") (pintype "passive"))
      (node (ref "U44") (pin "7") (pinfunction "AN12/ANN0/RP48/RC0_7") (pintype "passive"))
    )
    (net (code "20") (name "/CS_4K_Gyro") (class "Default")
      (node (ref "J25") (pin "1") (pinfunction "1_1") (pintype "passive"))
      (node (ref "U44") (pin "48") (pinfunction "RP45/PWM2L/RB13_48") (pintype "passive"))
    )
    (net (code "21") (name "/CS_CONT") (class "Default")
      (node (ref "U38") (pin "20") (pinfunction "~{CS}_20") (pintype "passive"))
      (node (ref "U44") (pin "40") (pinfunction "RP58/PWM7H/RC10_40") (pintype "passive"))
    )
    (net (code "22") (name "/CS_GYRO") (class "Default")
      (node (ref "J12") (pin "1") (pinfunction "1_1") (pintype "passive"))
      (node (ref "U44") (pin "38") (pinfunction "RP52/PWM5H/ASDA2/RC4_38") (pintype "passive"))
    )
    (net (code "23") (name "/CS_HG1") (class "Default")
      (node (ref "R19") (pin "1") (pinfunction "1_1") (pintype "passive"))
      (node (ref "U13") (pin "6") (pinfunction "CS_6") (pintype "passive"))
      (node (ref "U44") (pin "39") (pinfunction "RP53/PWM5L/ASCL2/RC5_39") (pintype "passive"))
    )
    (net (code "24") (name "/CS_LG1") (class "Default")
      (node (ref "J18") (pin "1") (pinfunction "1_1") (pintype "passive"))
      (node (ref "U44") (pin "24") (pinfunction "DACOUT2/AN16/CMP4C/ISRC2/_RP55/RC7_24") (pintype "passive"))
    )
    (net (code "25") (name "/CS_LG2") (class "Default")
      (node (ref "J17") (pin "1") (pinfunction "1_1") (pintype "passive"))
      (node (ref "U44") (pin "17") (pinfunction "AN17/ANN1/CMP4B/IBIAS1/_RP54/RC6_17") (pintype "passive"))
    )
    (net (code "26") (name "/CS_MAG") (class "Default")
      (node (ref "R40") (pin "2") (pinfunction "2_2") (pintype "passive"))
      (node (ref "U14") (pin "1") (pinfunction "CS_1") (pintype "passive"))
      (node (ref "U44") (pin "16") (pinfunction "OA3IN+/AN14/CMP2B/ISRC1/_RP50/RC2_16") (pintype "passive"))
    )
    (net (code "27") (name "/CS_MEM1") (class "Default")
      (node (ref "R26") (pin "1") (pinfunction "1_1") (pintype "passive"))
      (node (ref "U17") (pin "7") (pinfunction "~{SS}_7") (pintype "passive"))
      (node (ref "U38") (pin "11") (pinfunction "S2_11") (pintype "passive"))
    )
    (net (code "28") (name "/CS_MEM2") (class "Default")
      (node (ref "R55") (pin "1") (pinfunction "1_1") (pintype "passive"))
      (node (ref "U22") (pin "7") (pinfunction "~{SS}_7") (pintype "passive"))
      (node (ref "U38") (pin "10") (pinfunction "S3_10") (pintype "passive"))
    )
    (net (code "29") (name "/CS_MEM3") (class "Default")
      (node (ref "R75") (pin "1") (pinfunction "1_1") (pintype "passive"))
      (node (ref "U28") (pin "7") (pinfunction "~{SS}_7") (pintype "passive"))
      (node (ref "U38") (pin "9") (pinfunction "S4_9") (pintype "passive"))
    )
    (net (code "30") (name "/CS_MEM4") (class "Default")
      (node (ref "R106") (pin "1") (pinfunction "1_1") (pintype "passive"))
      (node (ref "U34") (pin "7") (pinfunction "~{SS}_7") (pintype "passive"))
      (node (ref "U38") (pin "8") (pinfunction "S5_8") (pintype "passive"))
    )
    (net (code "31") (name "/CS_MEM5") (class "Default")
      (node (ref "R123") (pin "1") (pinfunction "1_1") (pintype "passive"))
      (node (ref "U38") (pin "7") (pinfunction "S6_7") (pintype "passive"))
      (node (ref "U40") (pin "7") (pinfunction "~{SS}_7") (pintype "passive"))
    )
    (net (code "32") (name "/CS_MEM6") (class "Default")
      (node (ref "R153") (pin "1") (pinfunction "1_1") (pintype "passive"))
      (node (ref "U38") (pin "6") (pinfunction "S7_6") (pintype "passive"))
      (node (ref "U45") (pin "7") (pinfunction "~{SS}_7") (pintype "passive"))
    )
    (net (code "33") (name "/CS_MEM7") (class "Default")
      (node (ref "R22") (pin "1") (pinfunction "1_1") (pintype "passive"))
      (node (ref "U15") (pin "7") (pinfunction "~{SS}_7") (pintype "passive"))
      (node (ref "U38") (pin "5") (pinfunction "S8_5") (pintype "passive"))
    )
    (net (code "34") (name "/CS_MEM8") (class "Default")
      (node (ref "R47") (pin "1") (pinfunction "1_1") (pintype "passive"))
      (node (ref "U21") (pin "7") (pinfunction "~{SS}_7") (pintype "passive"))
      (node (ref "U38") (pin "4") (pinfunction "S9_4") (pintype "passive"))
    )
    (net (code "35") (name "/CS_MEM9") (class "Default")
      (node (ref "R79") (pin "1") (pinfunction "1_1") (pintype "passive"))
      (node (ref "U29") (pin "7") (pinfunction "~{SS}_7") (pintype "passive"))
      (node (ref "U38") (pin "3") (pinfunction "S10_3") (pintype "passive"))
    )
    (net (code "36") (name "/CS_MEM10") (class "Default")
      (node (ref "R110") (pin "1") (pinfunction "1_1") (pintype "passive"))
      (node (ref "U35") (pin "7") (pinfunction "~{SS}_7") (pintype "passive"))
      (node (ref "U38") (pin "2") (pinfunction "S11_2") (pintype "passive"))
    )
    (net (code "37") (name "/CS_MEM11") (class "Default")
      (node (ref "R127") (pin "1") (pinfunction "1_1") (pintype "passive"))
      (node (ref "U38") (pin "1") (pinfunction "S12_1") (pintype "passive"))
      (node (ref "U41") (pin "7") (pinfunction "~{SS}_7") (pintype "passive"))
    )
    (net (code "38") (name "/CS_MEM12") (class "Default")
      (node (ref "R146") (pin "1") (pinfunction "1_1") (pintype "passive"))
      (node (ref "U38") (pin "48") (pinfunction "S13_48") (pintype "passive"))
      (node (ref "U46") (pin "7") (pinfunction "~{SS}_7") (pintype "passive"))
    )
    (net (code "39") (name "/CS_MEM13") (class "Default")
      (node (ref "R30") (pin "1") (pinfunction "1_1") (pintype "passive"))
      (node (ref "U18") (pin "7") (pinfunction "~{SS}_7") (pintype "passive"))
      (node (ref "U38") (pin "47") (pinfunction "S14_47") (pintype "passive"))
    )
    (net (code "40") (name "/CS_MEM14") (class "Default")
      (node (ref "R59") (pin "1") (pinfunction "1_1") (pintype "passive"))
      (node (ref "U23") (pin "7") (pinfunction "~{SS}_7") (pintype "passive"))
      (node (ref "U38") (pin "46") (pinfunction "S15_46") (pintype "passive"))
    )
    (net (code "41") (name "/CS_MEM15") (class "Default")
      (node (ref "R83") (pin "1") (pinfunction "1_1") (pintype "passive"))
      (node (ref "U30") (pin "7") (pinfunction "~{SS}_7") (pintype "passive"))
      (node (ref "U38") (pin "45") (pinfunction "S16_45") (pintype "passive"))
    )
    (net (code "42") (name "/CS_MEM16") (class "Default")
      (node (ref "R114") (pin "1") (pinfunction "1_1") (pintype "passive"))
      (node (ref "U36") (pin "7") (pinfunction "~{SS}_7") (pintype "passive"))
      (node (ref "U38") (pin "25") (pinfunction "S17_25") (pintype "passive"))
    )
    (net (code "43") (name "/CS_MEM17") (class "Default")
      (node (ref "R131") (pin "1") (pinfunction "1_1") (pintype "passive"))
      (node (ref "U38") (pin "26") (pinfunction "S18_26") (pintype "passive"))
      (node (ref "U42") (pin "7") (pinfunction "~{SS}_7") (pintype "passive"))
    )
    (net (code "44") (name "/CS_MEM18") (class "Default")
      (node (ref "R154") (pin "1") (pinfunction "1_1") (pintype "passive"))
      (node (ref "U38") (pin "27") (pinfunction "S19_27") (pintype "passive"))
      (node (ref "U47") (pin "7") (pinfunction "~{SS}_7") (pintype "passive"))
    )
    (net (code "45") (name "/CS_MEM19") (class "Default")
      (node (ref "R34") (pin "1") (pinfunction "1_1") (pintype "passive"))
      (node (ref "U19") (pin "7") (pinfunction "~{SS}_7") (pintype "passive"))
      (node (ref "U38") (pin "28") (pinfunction "S20_28") (pintype "passive"))
    )
    (net (code "46") (name "/CS_MEM20") (class "Default")
      (node (ref "R63") (pin "1") (pinfunction "1_1") (pintype "passive"))
      (node (ref "U25") (pin "7") (pinfunction "~{SS}_7") (pintype "passive"))
      (node (ref "U38") (pin "29") (pinfunction "S21_29") (pintype "passive"))
    )
    (net (code "47") (name "/CS_MEM21") (class "Default")
      (node (ref "R87") (pin "1") (pinfunction "1_1") (pintype "passive"))
      (node (ref "U31") (pin "7") (pinfunction "~{SS}_7") (pintype "passive"))
      (node (ref "U38") (pin "30") (pinfunction "S22_30") (pintype "passive"))
    )
    (net (code "48") (name "/CS_MEM22") (class "Default")
      (node (ref "R118") (pin "1") (pinfunction "1_1") (pintype "passive"))
      (node (ref "U37") (pin "7") (pinfunction "~{SS}_7") (pintype "passive"))
      (node (ref "U38") (pin "31") (pinfunction "S23_31") (pintype "passive"))
    )
    (net (code "49") (name "/CS_MEM23") (class "Default")
      (node (ref "R135") (pin "1") (pinfunction "1_1") (pintype "passive"))
      (node (ref "U38") (pin "32") (pinfunction "S24_32") (pintype "passive"))
      (node (ref "U43") (pin "7") (pinfunction "~{SS}_7") (pintype "passive"))
    )
    (net (code "50") (name "/CS_MEM24") (class "Default")
      (node (ref "R155") (pin "1") (pinfunction "1_1") (pintype "passive"))
      (node (ref "U38") (pin "33") (pinfunction "S25_33") (pintype "passive"))
      (node (ref "U48") (pin "7") (pinfunction "~{SS}_7") (pintype "passive"))
    )
    (net (code "51") (name "/CS_SRAM1") (class "Default")
      (node (ref "R122") (pin "1") (pinfunction "1_1") (pintype "passive"))
      (node (ref "U39") (pin "1") (pinfunction "~{CS}_1") (pintype "passive"))
      (node (ref "U44") (pin "15") (pinfunction "OA3IN-/AN13/CMP1B/ISRC0/_RP49/RC1_15") (pintype "passive"))
    )
    (net (code "52") (name "/CS_VOLT") (class "Default")
      (node (ref "R54") (pin "1") (pinfunction "1_1") (pintype "passive"))
      (node (ref "U44") (pin "20") (pinfunction "AN15/ANN2/CMP2A/IBIAS2/_RP51/RC3_20") (pintype "passive"))
    )
    (net (code "53") (name "/CTL_CS_A0") (class "Default")
      (node (ref "U38") (pin "15") (pinfunction "A0_15") (pintype "passive"))
      (node (ref "U44") (pin "12") (pinfunction "OA3OUT/AN4/ANB1/ANB2/CMP3B/_IBIAS3/RA4_12") (pintype "passive"))
    )
    (net (code "54") (name "/CTL_CS_A1") (class "Default")
      (node (ref "U38") (pin "16") (pinfunction "A1_16") (pintype "passive"))
      (node (ref "U44") (pin "11") (pinfunction "DACOUT1/AN27/AN3/CMP1C/RA3_11") (pintype "passive"))
    )
    (net (code "55") (name "/CTL_CS_A2") (class "Default")
      (node (ref "U38") (pin "17") (pinfunction "A2_17") (pintype "passive"))
      (node (ref "U44") (pin "10") (pinfunction "OA1IN+/AN9/RA2_10") (pintype "passive"))
    )
    (net (code "56") (name "/CTL_CS_A3") (class "Default")
      (node (ref "U38") (pin "18") (pinfunction "A3_18") (pintype "passive"))
      (node (ref "U44") (pin "9") (pinfunction "OA1IN-/ANA1/RA1_9") (pintype "passive"))
    )
    (net (code "57") (name "/CTL_CS_A4") (class "Default")
      (node (ref "U38") (pin "19") (pinfunction "A4_19") (pintype "passive"))
      (node (ref "U44") (pin "8") (pinfunction "OA1OUT/AN0/CMP1A/IBIAS0/RA0_8") (pintype "passive"))
    )
    (net (code "58") (name "/Gyro_CONV") (class "Default")
      (node (ref "J13") (pin "1") (pinfunction "1_1") (pintype "passive"))
      (node (ref "U44") (pin "33") (pinfunction "PGD3/RP37/PWM6L/SDA2/RB5_33") (pintype "passive"))
    )
    (net (code "59") (name "/Gyro_Ref_2048") (class "Default")
      (node (ref "J2") (pin "1") (pinfunction "1_1") (pintype "passive"))
      (node (ref "R105") (pin "2") (pinfunction "2_2") (pintype "passive"))
    )
    (net (code "60") (name "/Gyro_Ref_4096") (class "Default")
      (node (ref "J11") (pin "1") (pinfunction "1_1") (pintype "passive"))
      (node (ref "R94") (pin "2") (pinfunction "2_2") (pintype "passive"))
    )
    (net (code "61") (name "/INT_Alert_2") (class "Default")
      (node (ref "R20") (pin "1") (pinfunction "1_1") (pintype "passive"))
      (node (ref "U13") (pin "5") (pinfunction "INT1_5") (pintype "passive"))
      (node (ref "U44") (pin "25") (pinfunction "OA2OUT/AN1/ANA0/CMP1D/RP34/SCL3/INT0/RB2_25") (pintype "passive"))
    )
    (net (code "62") (name "/Int_4K_Gyro") (class "Default")
      (node (ref "J27") (pin "1") (pinfunction "1_1") (pintype "passive"))
      (node (ref "U44") (pin "44") (pinfunction "RP65/PWM4H/RD1_44") (pintype "passive"))
    )
    (net (code "63") (name "/MAG_ANAL_1") (class "Default")
      (node (ref "C48") (pin "2") (pinfunction "2_2") (pintype "passive"))
      (node (ref "R73") (pin "1") (pinfunction "1_1") (pintype "passive"))
      (node (ref "TP5") (pin "1") (pinfunction "1_1") (pintype "passive"))
      (node (ref "U33") (pin "10") (pinfunction "VIN6_10") (pintype "passive"))
    )
    (net (code "64") (name "/MAG_ANAL_2") (class "Default")
      (node (ref "J21") (pin "1") (pinfunction "1_1") (pintype "passive"))
      (node (ref "U33") (pin "9") (pinfunction "VIN7_9") (pintype "passive"))
    )
    (net (code "65") (name "/MCLR") (class "Default")
      (node (ref "J3") (pin "1") (pinfunction "1_1") (pintype "passive"))
      (node (ref "R163") (pin "2") (pinfunction "2_2") (pintype "passive"))
      (node (ref "U44") (pin "5") (pinfunction "!MCLR_5") (pintype "passive"))
    )
    (net (code "66") (name "/MISO") (class "Default")
      (node (ref "U15") (pin "8") (pinfunction "DQ1_8") (pintype "passive"))
      (node (ref "U17") (pin "8") (pinfunction "DQ1_8") (pintype "passive"))
      (node (ref "U18") (pin "8") (pinfunction "DQ1_8") (pintype "passive"))
      (node (ref "U19") (pin "8") (pinfunction "DQ1_8") (pintype "passive"))
      (node (ref "U21") (pin "8") (pinfunction "DQ1_8") (pintype "passive"))
      (node (ref "U22") (pin "8") (pinfunction "DQ1_8") (pintype "passive"))
      (node (ref "U23") (pin "8") (pinfunction "DQ1_8") (pintype "passive"))
      (node (ref "U25") (pin "8") (pinfunction "DQ1_8") (pintype "passive"))
      (node (ref "U28") (pin "8") (pinfunction "DQ1_8") (pintype "passive"))
      (node (ref "U29") (pin "8") (pinfunction "DQ1_8") (pintype "passive"))
      (node (ref "U30") (pin "8") (pinfunction "DQ1_8") (pintype "passive"))
      (node (ref "U31") (pin "8") (pinfunction "DQ1_8") (pintype "passive"))
      (node (ref "U34") (pin "8") (pinfunction "DQ1_8") (pintype "passive"))
      (node (ref "U35") (pin "8") (pinfunction "DQ1_8") (pintype "passive"))
      (node (ref "U36") (pin "8") (pinfunction "DQ1_8") (pintype "passive"))
      (node (ref "U37") (pin "8") (pinfunction "DQ1_8") (pintype "passive"))
      (node (ref "U40") (pin "8") (pinfunction "DQ1_8") (pintype "passive"))
      (node (ref "U41") (pin "8") (pinfunction "DQ1_8") (pintype "passive"))
      (node (ref "U42") (pin "8") (pinfunction "DQ1_8") (pintype "passive"))
      (node (ref "U43") (pin "8") (pinfunction "DQ1_8") (pintype "passive"))
      (node (ref "U44") (pin "29") (pinfunction "RP57/ASCL1/SDI2/RC9_29") (pintype "passive"))
      (node (ref "U45") (pin "8") (pinfunction "DQ1_8") (pintype "passive"))
      (node (ref "U46") (pin "8") (pinfunction "DQ1_8") (pintype "passive"))
      (node (ref "U47") (pin "8") (pinfunction "DQ1_8") (pintype "passive"))
      (node (ref "U48") (pin "8") (pinfunction "DQ1_8") (pintype "passive"))
    )
    (net (code "67") (name "/MISO1") (class "Default")
      (node (ref "J14") (pin "1") (pinfunction "1_1") (pintype "passive"))
      (node (ref "R51") (pin "1") (pinfunction "1_1") (pintype "passive"))
      (node (ref "U13") (pin "7") (pinfunction "MISO_7") (pintype "passive"))
      (node (ref "U14") (pin "8") (pinfunction "SDO_8") (pintype "passive"))
      (node (ref "U39") (pin "2") (pinfunction "SO/SIO1_2") (pintype "passive"))
      (node (ref "U44") (pin "4") (pinfunction "RP61/PWM8L/RC13_4") (pintype "passive"))
    )
    (net (code "68") (name "/MISO2") (class "Default")
      (node (ref "J22") (pin "1") (pinfunction "1_1") (pintype "passive"))
      (node (ref "U44") (pin "45") (pinfunction "TMS/RP42/PWM3H/RB10_45") (pintype "passive"))
    )
    (net (code "69") (name "/MOSI") (class "Default")
      (node (ref "U15") (pin "15") (pinfunction "DQ0_15") (pintype "passive"))
      (node (ref "U17") (pin "15") (pinfunction "DQ0_15") (pintype "passive"))
      (node (ref "U18") (pin "15") (pinfunction "DQ0_15") (pintype "passive"))
      (node (ref "U19") (pin "15") (pinfunction "DQ0_15") (pintype "passive"))
      (node (ref "U21") (pin "15") (pinfunction "DQ0_15") (pintype "passive"))
      (node (ref "U22") (pin "15") (pinfunction "DQ0_15") (pintype "passive"))
      (node (ref "U23") (pin "15") (pinfunction "DQ0_15") (pintype "passive"))
      (node (ref "U25") (pin "15") (pinfunction "DQ0_15") (pintype "passive"))
      (node (ref "U28") (pin "15") (pinfunction "DQ0_15") (pintype "passive"))
      (node (ref "U29") (pin "15") (pinfunction "DQ0_15") (pintype "passive"))
      (node (ref "U30") (pin "15") (pinfunction "DQ0_15") (pintype "passive"))
      (node (ref "U31") (pin "15") (pinfunction "DQ0_15") (pintype "passive"))
      (node (ref "U34") (pin "15") (pinfunction "DQ0_15") (pintype "passive"))
      (node (ref "U35") (pin "15") (pinfunction "DQ0_15") (pintype "passive"))
      (node (ref "U36") (pin "15") (pinfunction "DQ0_15") (pintype "passive"))
      (node (ref "U37") (pin "15") (pinfunction "DQ0_15") (pintype "passive"))
      (node (ref "U40") (pin "15") (pinfunction "DQ0_15") (pintype "passive"))
      (node (ref "U41") (pin "15") (pinfunction "DQ0_15") (pintype "passive"))
      (node (ref "U42") (pin "15") (pinfunction "DQ0_15") (pintype "passive"))
      (node (ref "U43") (pin "15") (pinfunction "DQ0_15") (pintype "passive"))
      (node (ref "U44") (pin "30") (pinfunction "RP72/SDO2/PCI19/RD8_30") (pintype "passive"))
      (node (ref "U45") (pin "15") (pinfunction "DQ0_15") (pintype "passive"))
      (node (ref "U46") (pin "15") (pinfunction "DQ0_15") (pintype "passive"))
      (node (ref "U47") (pin "15") (pinfunction "DQ0_15") (pintype "passive"))
      (node (ref "U48") (pin "15") (pinfunction "DQ0_15") (pintype "passive"))
    )
    (net (code "70") (name "/MOSI1") (class "Default")
      (node (ref "J16") (pin "1") (pinfunction "1_1") (pintype "passive"))
      (node (ref "R52") (pin "1") (pinfunction "1_1") (pintype "passive"))
      (node (ref "U13") (pin "8") (pinfunction "MOSI_8") (pintype "passive"))
      (node (ref "U14") (pin "7") (pinfunction "SDA_7") (pintype "passive"))
      (node (ref "U39") (pin "5") (pinfunction "SI/SIO0_5") (pintype "passive"))
      (node (ref "U44") (pin "3") (pinfunction "RP60/PWM8H/RC12_3") (pintype "passive"))
    )
    (net (code "71") (name "/MOSI2") (class "Default")
      (node (ref "J23") (pin "1") (pinfunction "1_1") (pintype "passive"))
      (node (ref "U44") (pin "46") (pinfunction "TCK/RP43/PWM3L/RB11_46") (pintype "passive"))
    )
    (net (code "72") (name "/OSC") (class "Default")
      (node (ref "R140") (pin "1") (pinfunction "1_1") (pintype "passive"))
      (node (ref "U44") (pin "21") (pinfunction "OSCI/CLKI/AN5/RP32/RB0_21") (pintype "passive"))
    )
    (net (code "73") (name "/PGEC1") (class "Default")
      (node (ref "J3") (pin "5") (pinfunction "5_5") (pintype "passive"))
      (node (ref "U44") (pin "37") (pinfunction "PGC1/AN11/CMP5A/RP41/SDA1/RB9_37") (pintype "passive"))
    )
    (net (code "74") (name "/PGED1") (class "Default")
      (node (ref "J3") (pin "4") (pinfunction "4_4") (pintype "passive"))
      (node (ref "U44") (pin "36") (pinfunction "PGD1/AN10/CMP6A/RP40/SCL1/RB8_36") (pintype "passive"))
    )
    (net (code "75") (name "/POWER_SW") (class "Default")
      (node (ref "D7") (pin "2") (pinfunction "A_2") (pintype "passive"))
      (node (ref "J26") (pin "1") (pinfunction "1_1") (pintype "passive"))
      (node (ref "R101") (pin "2") (pinfunction "2_2") (pintype "passive"))
      (node (ref "R175") (pin "2") (pinfunction "2_2") (pintype "passive"))
      (node (ref "R184") (pin "2") (pinfunction "2_2") (pintype "passive"))
      (node (ref "U44") (pin "23") (pinfunction "AN18/ANC2/CMP3C/ISRC3/RP74/_RD10_23") (pintype "passive"))
    )
    (net (code "76") (name "/QBUS") (class "Default")
      (node (ref "J1") (pin "10") (pinfunction "10_10") (pintype "passive"))
      (node (ref "R17") (pin "1") (pinfunction "1_1") (pintype "passive"))
    )
    (net (code "77") (name "/SCK") (class "Default")
      (node (ref "U15") (pin "16") (pinfunction "CLK_16") (pintype "passive"))
      (node (ref "U17") (pin "16") (pinfunction "CLK_16") (pintype "passive"))
      (node (ref "U18") (pin "16") (pinfunction "CLK_16") (pintype "passive"))
      (node (ref "U19") (pin "16") (pinfunction "CLK_16") (pintype "passive"))
      (node (ref "U21") (pin "16") (pinfunction "CLK_16") (pintype "passive"))
      (node (ref "U22") (pin "16") (pinfunction "CLK_16") (pintype "passive"))
      (node (ref "U23") (pin "16") (pinfunction "CLK_16") (pintype "passive"))
      (node (ref "U25") (pin "16") (pinfunction "CLK_16") (pintype "passive"))
      (node (ref "U28") (pin "16") (pinfunction "CLK_16") (pintype "passive"))
      (node (ref "U29") (pin "16") (pinfunction "CLK_16") (pintype "passive"))
      (node (ref "U30") (pin "16") (pinfunction "CLK_16") (pintype "passive"))
      (node (ref "U31") (pin "16") (pinfunction "CLK_16") (pintype "passive"))
      (node (ref "U34") (pin "16") (pinfunction "CLK_16") (pintype "passive"))
      (node (ref "U35") (pin "16") (pinfunction "CLK_16") (pintype "passive"))
      (node (ref "U36") (pin "16") (pinfunction "CLK_16") (pintype "passive"))
      (node (ref "U37") (pin "16") (pinfunction "CLK_16") (pintype "passive"))
      (node (ref "U40") (pin "16") (pinfunction "CLK_16") (pintype "passive"))
      (node (ref "U41") (pin "16") (pinfunction "CLK_16") (pintype "passive"))
      (node (ref "U42") (pin "16") (pinfunction "CLK_16") (pintype "passive"))
      (node (ref "U43") (pin "16") (pinfunction "CLK_16") (pintype "passive"))
      (node (ref "U44") (pin "28") (pinfunction "RP56/ASDA1/SCK2/RC8_28") (pintype "passive"))
      (node (ref "U45") (pin "16") (pinfunction "CLK_16") (pintype "passive"))
      (node (ref "U46") (pin "16") (pinfunction "CLK_16") (pintype "passive"))
      (node (ref "U47") (pin "16") (pinfunction "CLK_16") (pintype "passive"))
      (node (ref "U48") (pin "16") (pinfunction "CLK_16") (pintype "passive"))
    )
    (net (code "78") (name "/SCK1") (class "Default")
      (node (ref "J15") (pin "1") (pinfunction "1_1") (pintype "passive"))
      (node (ref "R53") (pin "1") (pinfunction "1_1") (pintype "passive"))
      (node (ref "U13") (pin "9") (pinfunction "SCK_9") (pintype "passive"))
      (node (ref "U14") (pin "6") (pinfunction "SCL_6") (pintype "passive"))
      (node (ref "U39") (pin "6") (pinfunction "SCK_6") (pintype "passive"))
      (node (ref "U44") (pin "41") (pinfunction "RP59/PWM7L/RC11_41") (pintype "passive"))
    )
    (net (code "79") (name "/SCK2") (class "Default")
      (node (ref "J24") (pin "1") (pinfunction "1_1") (pintype "passive"))
      (node (ref "U44") (pin "47") (pinfunction "TDI/RP44/PWM2H/RB12_47") (pintype "passive"))
    )
    (net (code "80") (name "/UART1_RX_3V3") (class "Default")
      (node (ref "R189") (pin "2") (pinfunction "2_2") (pintype "passive"))
      (node (ref "U2") (pin "4") (pinfunction "A2_4") (pintype "passive"))
    )
    (net (code "81") (name "/UART1_RX_5V") (class "Default")
      (node (ref "U2") (pin "1") (pinfunction "B2_1") (pintype "passive"))
      (node (ref "U27") (pin "2") (pinfunction "A_2") (pintype "passive"))
    )
    (net (code "82") (name "/UART1_TX_3V3") (class "Default")
      (node (ref "R190") (pin "2") (pinfunction "2_2") (pintype "passive"))
      (node (ref "U2") (pin "5") (pinfunction "A1_5") (pintype "passive"))
    )
    (net (code "83") (name "/UART1_TX_5V") (class "Default")
      (node (ref "U1") (pin "4") (pinfunction "Y_4") (pintype "output"))
      (node (ref "U2") (pin "8") (pinfunction "B1_8") (pintype "passive"))
    )
    (net (code "84") (name "/UART2_RX_3V3") (class "Default")
      (node (ref "J10") (pin "1") (pinfunction "1_1") (pintype "passive"))
      (node (ref "J54") (pin "1") (pinfunction "1_1") (pintype "passive"))
      (node (ref "U44") (pin "34") (pinfunction "PGC3/RP38/PWM6H/SCL2/RB6_34") (pintype "passive"))
    )
    (net (code "85") (name "/UART2_TX_3V3") (class "Default")
      (node (ref "J55") (pin "1") (pinfunction "1_1") (pintype "passive"))
      (node (ref "J9") (pin "1") (pinfunction "1_1") (pintype "passive"))
      (node (ref "R188") (pin "2") (pinfunction "2_2") (pintype "passive"))
      (node (ref "U44") (pin "35") (pinfunction "TDO/AN2/AN26/CMP3A/RP39/_SDA3/RB7_35") (pintype "passive"))
    )
    (net (code "86") (name "/UART_DT_RX_5V_EXT") (class "Default")
      (node (ref "J1") (pin "9") (pinfunction "9_9") (pintype "passive"))
      (node (ref "U3") (pin "4") (pinfunction "Y_4") (pintype "passive"))
    )
    (net (code "87") (name "/UART_DT_TX_5V_EXT") (class "Default")
      (node (ref "J1") (pin "8") (pinfunction "8_8") (pintype "passive"))
      (node (ref "U7") (pin "2") (pinfunction "A_2") (pintype "passive"))
    )
    (net (code "88") (name "/VBAT1") (class "Default")
      (node (ref "C16") (pin "2") (pinfunction "2_2") (pintype "passive"))
      (node (ref "C17") (pin "1") (pinfunction "1_1") (pintype "passive"))
      (node (ref "F2") (pin "1") (pinfunction "1_1") (pintype "passive"))
      (node (ref "Q1") (pin "3") (pinfunction "DRAIN_3") (pintype "passive"))
      (node (ref "U5") (pin "1") (pinfunction "VIN_1") (pintype "power_in"))
    )
    (net (code "89") (name "/VBAT2") (class "Default")
      (node (ref "C23") (pin "2") (pinfunction "2_2") (pintype "passive"))
      (node (ref "C24") (pin "1") (pinfunction "1_1") (pintype "passive"))
      (node (ref "F3") (pin "1") (pinfunction "1_1") (pintype "passive"))
      (node (ref "Q3") (pin "3") (pinfunction "DRAIN_3") (pintype "passive"))
      (node (ref "U8") (pin "1") (pinfunction "VIN_1") (pintype "power_in"))
    )
    (net (code "90") (name "/VBAT3") (class "Default")
      (node (ref "C34") (pin "2") (pinfunction "2_2") (pintype "passive"))
      (node (ref "C35") (pin "1") (pinfunction "1_1") (pintype "passive"))
      (node (ref "F4") (pin "1") (pinfunction "1_1") (pintype "passive"))
      (node (ref "Q5") (pin "3") (pinfunction "DRAIN_3") (pintype "passive"))
      (node (ref "U11") (pin "1") (pinfunction "VIN_1") (pintype "power_in"))
    )
    (net (code "91") (name "/VOLT_IN_5V") (class "Default")
      (node (ref "C38") (pin "2") (pinfunction "2_2") (pintype "passive"))
      (node (ref "C39") (pin "1") (pinfunction "1_1") (pintype "passive"))
      (node (ref "C40") (pin "1") (pinfunction "1_1") (pintype "passive"))
      (node (ref "D4") (pin "2") (pinfunction "A_2") (pintype "passive"))
      (node (ref "L5") (pin "2") (pinfunction "2_2") (pintype "passive"))
      (node (ref "R67") (pin "1") (pinfunction "1_1") (pintype "passive"))
      (node (ref "R72") (pin "2") (pinfunction "2_2") (pintype "passive"))
      (node (ref "TP17") (pin "1") (pinfunction "1_1") (pintype "passive"))
      (node (ref "U6") (pin "1") (pinfunction "VIN1_1") (pintype "passive"))
      (node (ref "U6") (pin "14") (pinfunction "RUN1_14") (pintype "passive"))
    )
    (net (code "92") (name "/VOLT_IN_BAT") (class "Default")
      (node (ref "C13") (pin "2") (pinfunction "2_2") (pintype "passive"))
      (node (ref "C20") (pin "1") (pinfunction "1_1") (pintype "passive"))
      (node (ref "C21") (pin "1") (pinfunction "1_1") (pintype "passive"))
      (node (ref "D3") (pin "2") (pinfunction "A_2") (pintype "passive"))
      (node (ref "L3") (pin "2") (pinfunction "2_2") (pintype "passive"))
      (node (ref "R16") (pin "1") (pinfunction "1_1") (pintype "passive"))
      (node (ref "R69") (pin "2") (pinfunction "2_2") (pintype "passive"))
      (node (ref "TP16") (pin "1") (pinfunction "1_1") (pintype "passive"))
      (node (ref "U6") (pin "10") (pinfunction "RUN2_10") (pintype "passive"))
      (node (ref "U6") (pin "8") (pinfunction "VIN2_8") (pintype "passive"))
    )
    (net (code "93") (name "/XTAL_ENABLE") (class "Default")
      (node (ref "R141") (pin "2") (pinfunction "2_2") (pintype "passive"))
      (node (ref "U44") (pin "22") (pinfunction "OSCO/CLKO/AN6/RP33/RB1_22") (pintype "passive"))
    )
    (net (code "94") (name "3V3") (class "Default")
      (node (ref "C100") (pin "2") (pinfunction "2_2") (pintype "passive"))
      (node (ref "C101") (pin "2") (pinfunction "2_2") (pintype "passive"))
      (node (ref "C102") (pin "2") (pinfunction "2_2") (pintype "passive"))
      (node (ref "C103") (pin "2") (pinfunction "2_2") (pintype "passive"))
      (node (ref "C104") (pin "2") (pinfunction "2_2") (pintype "passive"))
      (node (ref "C105") (pin "2") (pinfunction "2_2") (pintype "passive"))
      (node (ref "C106") (pin "2") (pinfunction "2_2") (pintype "passive"))
      (node (ref "C107") (pin "2") (pinfunction "2_2") (pintype "passive"))
      (node (ref "C108") (pin "2") (pinfunction "2_2") (pintype "passive"))
      (node (ref "C109") (pin "2") (pinfunction "2_2") (pintype "passive"))
      (node (ref "C110") (pin "2") (pinfunction "2_2") (pintype "passive"))
      (node (ref "C111") (pin "2") (pinfunction "2_2") (pintype "passive"))
      (node (ref "C112") (pin "2") (pinfunction "2_2") (pintype "passive"))
      (node (ref "C113") (pin "2") (pinfunction "2_2") (pintype "passive"))
      (node (ref "C114") (pin "2") (pinfunction "2_2") (pintype "passive"))
      (node (ref "C115") (pin "2") (pinfunction "2_2") (pintype "passive"))
      (node (ref "C14") (pin "1") (pinfunction "1_1") (pintype "passive"))
      (node (ref "C27") (pin "2") (pinfunction "2_2") (pintype "passive"))
      (node (ref "C28") (pin "2") (pinfunction "2_2") (pintype "passive"))
      (node (ref "C29") (pin "2") (pinfunction "2_2") (pintype "passive"))
      (node (ref "C3") (pin "2") (pinfunction "2_2") (pintype "passive"))
      (node (ref "C30") (pin "1") (pinfunction "1_1") (pintype "passive"))
      (node (ref "C31") (pin "2") (pinfunction "2_2") (pintype "passive"))
      (node (ref "C32") (pin "1") (pinfunction "1_1") (pintype "passive"))
      (node (ref "C54") (pin "2") (pinfunction "2_2") (pintype "passive"))
      (node (ref "C55") (pin "1") (pinfunction "1_1") (pintype "passive"))
      (node (ref "C56") (pin "2") (pinfunction "2_2") (pintype "passive"))
      (node (ref "C57") (pin "2") (pinfunction "2_2") (pintype "passive"))
      (node (ref "C58") (pin "2") (pinfunction "2_2") (pintype "passive"))
      (node (ref "C60") (pin "2") (pinfunction "2_2") (pintype "passive"))
      (node (ref "C61") (pin "2") (pinfunction "2_2") (pintype "passive"))
      (node (ref "C68") (pin "2") (pinfunction "2_2") (pintype "passive"))
      (node (ref "C70") (pin "2") (pinfunction "2_2") (pintype "passive"))
      (node (ref "C71") (pin "2") (pinfunction "2_2") (pintype "passive"))
      (node (ref "C73") (pin "2") (pinfunction "2_2") (pintype "passive"))
      (node (ref "C75") (pin "2") (pinfunction "2_2") (pintype "passive"))
      (node (ref "C79") (pin "2") (pinfunction "2_2") (pintype "passive"))
      (node (ref "C80") (pin "2") (pinfunction "2_2") (pintype "passive"))
      (node (ref "C81") (pin "2") (pinfunction "2_2") (pintype "passive"))
      (node (ref "C82") (pin "2") (pinfunction "2_2") (pintype "passive"))
      (node (ref "C84") (pin "2") (pinfunction "2_2") (pintype "passive"))
      (node (ref "C85") (pin "2") (pinfunction "2_2") (pintype "passive"))
      (node (ref "C86") (pin "2") (pinfunction "2_2") (pintype "passive"))
      (node (ref "C87") (pin "2") (pinfunction "2_2") (pintype "passive"))
      (node (ref "C88") (pin "2") (pinfunction "2_2") (pintype "passive"))
      (node (ref "C89") (pin "2") (pinfunction "2_2") (pintype "passive"))
      (node (ref "C94") (pin "2") (pinfunction "2_2") (pintype "passive"))
      (node (ref "C95") (pin "2") (pinfunction "2_2") (pintype "passive"))
      (node (ref "C96") (pin "2") (pinfunction "2_2") (pintype "passive"))
      (node (ref "C97") (pin "2") (pinfunction "2_2") (pintype "passive"))
      (node (ref "C99") (pin "2") (pinfunction "2_2") (pintype "passive"))
      (node (ref "J19") (pin "1") (pinfunction "1_1") (pintype "passive"))
      (node (ref "J3") (pin "2") (pinfunction "2_2") (pintype "passive"))
      (node (ref "J4") (pin "1") (pinfunction "1_1") (pintype "passive"))
      (node (ref "J56") (pin "1") (pinfunction "1_1") (pintype "passive"))
      (node (ref "L2") (pin "2") (pinfunction "2_2") (pintype "passive"))
      (node (ref "Q10") (pin "4") (pinfunction "S2_4") (pintype "passive"))
      (node (ref "Q11") (pin "4") (pinfunction "S2_4") (pintype "passive"))
      (node (ref "R100") (pin "2") (pinfunction "2_2") (pintype "passive"))
      (node (ref "R106") (pin "2") (pinfunction "2_2") (pintype "passive"))
      (node (ref "R107") (pin "2") (pinfunction "2_2") (pintype "passive"))
      (node (ref "R108") (pin "2") (pinfunction "2_2") (pintype "passive"))
      (node (ref "R109") (pin "2") (pinfunction "2_2") (pintype "passive"))
      (node (ref "R110") (pin "2") (pinfunction "2_2") (pintype "passive"))
      (node (ref "R111") (pin "2") (pinfunction "2_2") (pintype "passive"))
      (node (ref "R112") (pin "2") (pinfunction "2_2") (pintype "passive"))
      (node (ref "R113") (pin "2") (pinfunction "2_2") (pintype "passive"))
      (node (ref "R114") (pin "2") (pinfunction "2_2") (pintype "passive"))
      (node (ref "R115") (pin "2") (pinfunction "2_2") (pintype "passive"))
      (node (ref "R116") (pin "2") (pinfunction "2_2") (pintype "passive"))
      (node (ref "R117") (pin "2") (pinfunction "2_2") (pintype "passive"))
      (node (ref "R118") (pin "2") (pinfunction "2_2") (pintype "passive"))
      (node (ref "R119") (pin "2") (pinfunction "2_2") (pintype "passive"))
      (node (ref "R120") (pin "2") (pinfunction "2_2") (pintype "passive"))
      (node (ref "R121") (pin "2") (pinfunction "2_2") (pintype "passive"))
      (node (ref "R122") (pin "2") (pinfunction "2_2") (pintype "passive"))
      (node (ref "R123") (pin "2") (pinfunction "2_2") (pintype "passive"))
      (node (ref "R124") (pin "2") (pinfunction "2_2") (pintype "passive"))
      (node (ref "R125") (pin "2") (pinfunction "2_2") (pintype "passive"))
      (node (ref "R126") (pin "2") (pinfunction "2_2") (pintype "passive"))
      (node (ref "R127") (pin "2") (pinfunction "2_2") (pintype "passive"))
      (node (ref "R128") (pin "2") (pinfunction "2_2") (pintype "passive"))
      (node (ref "R129") (pin "2") (pinfunction "2_2") (pintype "passive"))
      (node (ref "R13") (pin "1") (pinfunction "1_1") (pintype "passive"))
      (node (ref "R130") (pin "2") (pinfunction "2_2") (pintype "passive"))
      (node (ref "R131") (pin "2") (pinfunction "2_2") (pintype "passive"))
      (node (ref "R132") (pin "2") (pinfunction "2_2") (pintype "passive"))
      (node (ref "R133") (pin "2") (pinfunction "2_2") (pintype "passive"))
      (node (ref "R134") (pin "2") (pinfunction "2_2") (pintype "passive"))
      (node (ref "R135") (pin "2") (pinfunction "2_2") (pintype "passive"))
      (node (ref "R136") (pin "2") (pinfunction "2_2") (pintype "passive"))
      (node (ref "R137") (pin "2") (pinfunction "2_2") (pintype "passive"))
      (node (ref "R138") (pin "2") (pinfunction "2_2") (pintype "passive"))
      (node (ref "R139") (pin "2") (pinfunction "2_2") (pintype "passive"))
      (node (ref "R143") (pin "2") (pinfunction "2_2") (pintype "passive"))
      (node (ref "R144") (pin "2") (pinfunction "2_2") (pintype "passive"))
      (node (ref "R145") (pin "2") (pinfunction "2_2") (pintype "passive"))
      (node (ref "R146") (pin "2") (pinfunction "2_2") (pintype "passive"))
      (node (ref "R147") (pin "2") (pinfunction "2_2") (pintype "passive"))
      (node (ref "R148") (pin "2") (pinfunction "2_2") (pintype "passive"))
      (node (ref "R149") (pin "2") (pinfunction "2_2") (pintype "passive"))
      (node (ref "R150") (pin "2") (pinfunction "2_2") (pintype "passive"))
      (node (ref "R151") (pin "2") (pinfunction "2_2") (pintype "passive"))
      (node (ref "R152") (pin "2") (pinfunction "2_2") (pintype "passive"))
      (node (ref "R153") (pin "2") (pinfunction "2_2") (pintype "passive"))
      (node (ref "R154") (pin "2") (pinfunction "2_2") (pintype "passive"))
      (node (ref "R155") (pin "2") (pinfunction "2_2") (pintype "passive"))
      (node (ref "R156") (pin "2") (pinfunction "2_2") (pintype "passive"))
      (node (ref "R157") (pin "2") (pinfunction "2_2") (pintype "passive"))
      (node (ref "R158") (pin "2") (pinfunction "2_2") (pintype "passive"))
      (node (ref "R161") (pin "2") (pinfunction "2_2") (pintype "passive"))
      (node (ref "R174") (pin "1") (pinfunction "1_1") (pintype "passive"))
      (node (ref "R182") (pin "1") (pinfunction "1_1") (pintype "passive"))
      (node (ref "R188") (pin "1") (pinfunction "1_1") (pintype "passive"))
      (node (ref "R19") (pin "2") (pinfunction "2_2") (pintype "passive"))
      (node (ref "R20") (pin "2") (pinfunction "2_2") (pintype "passive"))
      (node (ref "R22") (pin "2") (pinfunction "2_2") (pintype "passive"))
      (node (ref "R23") (pin "2") (pinfunction "2_2") (pintype "passive"))
      (node (ref "R24") (pin "2") (pinfunction "2_2") (pintype "passive"))
      (node (ref "R25") (pin "2") (pinfunction "2_2") (pintype "passive"))
      (node (ref "R26") (pin "2") (pinfunction "2_2") (pintype "passive"))
      (node (ref "R27") (pin "2") (pinfunction "2_2") (pintype "passive"))
      (node (ref "R28") (pin "2") (pinfunction "2_2") (pintype "passive"))
      (node (ref "R29") (pin "2") (pinfunction "2_2") (pintype "passive"))
      (node (ref "R30") (pin "2") (pinfunction "2_2") (pintype "passive"))
      (node (ref "R31") (pin "2") (pinfunction "2_2") (pintype "passive"))
      (node (ref "R32") (pin "2") (pinfunction "2_2") (pintype "passive"))
      (node (ref "R33") (pin "2") (pinfunction "2_2") (pintype "passive"))
      (node (ref "R34") (pin "2") (pinfunction "2_2") (pintype "passive"))
      (node (ref "R35") (pin "2") (pinfunction "2_2") (pintype "passive"))
      (node (ref "R36") (pin "2") (pinfunction "2_2") (pintype "passive"))
      (node (ref "R37") (pin "2") (pinfunction "2_2") (pintype "passive"))
      (node (ref "R40") (pin "1") (pinfunction "1_1") (pintype "passive"))
      (node (ref "R46") (pin "1") (pinfunction "1_1") (pintype "passive"))
      (node (ref "R47") (pin "2") (pinfunction "2_2") (pintype "passive"))
      (node (ref "R48") (pin "2") (pinfunction "2_2") (pintype "passive"))
      (node (ref "R49") (pin "2") (pinfunction "2_2") (pintype "passive"))
      (node (ref "R50") (pin "2") (pinfunction "2_2") (pintype "passive"))
      (node (ref "R55") (pin "2") (pinfunction "2_2") (pintype "passive"))
      (node (ref "R56") (pin "2") (pinfunction "2_2") (pintype "passive"))
      (node (ref "R57") (pin "2") (pinfunction "2_2") (pintype "passive"))
      (node (ref "R58") (pin "2") (pinfunction "2_2") (pintype "passive"))
      (node (ref "R59") (pin "2") (pinfunction "2_2") (pintype "passive"))
      (node (ref "R60") (pin "2") (pinfunction "2_2") (pintype "passive"))
      (node (ref "R61") (pin "2") (pinfunction "2_2") (pintype "passive"))
      (node (ref "R62") (pin "2") (pinfunction "2_2") (pintype "passive"))
      (node (ref "R63") (pin "2") (pinfunction "2_2") (pintype "passive"))
      (node (ref "R64") (pin "2") (pinfunction "2_2") (pintype "passive"))
      (node (ref "R65") (pin "2") (pinfunction "2_2") (pintype "passive"))
      (node (ref "R66") (pin "2") (pinfunction "2_2") (pintype "passive"))
      (node (ref "R75") (pin "2") (pinfunction "2_2") (pintype "passive"))
      (node (ref "R76") (pin "2") (pinfunction "2_2") (pintype "passive"))
      (node (ref "R77") (pin "2") (pinfunction "2_2") (pintype "passive"))
      (node (ref "R78") (pin "2") (pinfunction "2_2") (pintype "passive"))
      (node (ref "R79") (pin "2") (pinfunction "2_2") (pintype "passive"))
      (node (ref "R80") (pin "2") (pinfunction "2_2") (pintype "passive"))
      (node (ref "R81") (pin "2") (pinfunction "2_2") (pintype "passive"))
      (node (ref "R82") (pin "2") (pinfunction "2_2") (pintype "passive"))
      (node (ref "R83") (pin "2") (pinfunction "2_2") (pintype "passive"))
      (node (ref "R84") (pin "2") (pinfunction "2_2") (pintype "passive"))
      (node (ref "R85") (pin "2") (pinfunction "2_2") (pintype "passive"))
      (node (ref "R86") (pin "2") (pinfunction "2_2") (pintype "passive"))
      (node (ref "R87") (pin "2") (pinfunction "2_2") (pintype "passive"))
      (node (ref "R88") (pin "2") (pinfunction "2_2") (pintype "passive"))
      (node (ref "R89") (pin "2") (pinfunction "2_2") (pintype "passive"))
      (node (ref "R90") (pin "2") (pinfunction "2_2") (pintype "passive"))
      (node (ref "TP19") (pin "1") (pinfunction "1_1") (pintype "passive"))
      (node (ref "U13") (pin "1") (pinfunction "VS_1") (pintype "passive"))
      (node (ref "U13") (pin "2") (pinfunction "VIO_2") (pintype "passive"))
      (node (ref "U14") (pin "2") (pinfunction "VIO_2") (pintype "passive"))
      (node (ref "U14") (pin "3") (pinfunction "VDD_3") (pintype "passive"))
      (node (ref "U15") (pin "2") (pinfunction "VCC_2") (pintype "passive"))
      (node (ref "U16") (pin "8") (pinfunction "VDD_8") (pintype "power_in"))
      (node (ref "U17") (pin "2") (pinfunction "VCC_2") (pintype "passive"))
      (node (ref "U18") (pin "2") (pinfunction "VCC_2") (pintype "passive"))
      (node (ref "U19") (pin "2") (pinfunction "VCC_2") (pintype "passive"))
      (node (ref "U2") (pin "3") (pinfunction "VCCA_3") (pintype "passive"))
      (node (ref "U21") (pin "2") (pinfunction "VCC_2") (pintype "passive"))
      (node (ref "U22") (pin "2") (pinfunction "VCC_2") (pintype "passive"))
      (node (ref "U23") (pin "2") (pinfunction "VCC_2") (pintype "passive"))
      (node (ref "U25") (pin "2") (pinfunction "VCC_2") (pintype "passive"))
      (node (ref "U26") (pin "8") (pinfunction "VDD_8") (pintype "power_in"))
      (node (ref "U28") (pin "2") (pinfunction "VCC_2") (pintype "passive"))
      (node (ref "U29") (pin "2") (pinfunction "VCC_2") (pintype "passive"))
      (node (ref "U30") (pin "2") (pinfunction "VCC_2") (pintype "passive"))
      (node (ref "U31") (pin "2") (pinfunction "VCC_2") (pintype "passive"))
      (node (ref "U32") (pin "2") (pinfunction "VIN_2") (pintype "passive"))
      (node (ref "U33") (pin "19") (pinfunction "VDRIVE_19") (pintype "passive"))
      (node (ref "U33") (pin "5") (pinfunction "VDD_5") (pintype "passive"))
      (node (ref "U33") (pin "6") (pinfunction "VDD_6") (pintype "passive"))
      (node (ref "U34") (pin "2") (pinfunction "VCC_2") (pintype "passive"))
      (node (ref "U35") (pin "2") (pinfunction "VCC_2") (pintype "passive"))
      (node (ref "U36") (pin "2") (pinfunction "VCC_2") (pintype "passive"))
      (node (ref "U37") (pin "2") (pinfunction "VCC_2") (pintype "passive"))
      (node (ref "U38") (pin "13") (pinfunction "VDD_1_13") (pintype "passive"))
      (node (ref "U38") (pin "14") (pinfunction "VDD_2_14") (pintype "passive"))
      (node (ref "U39") (pin "7") (pinfunction "~{HOLD}/SIO3_7") (pintype "passive"))
      (node (ref "U39") (pin "8") (pinfunction "VCC_8") (pintype "passive"))
      (node (ref "U4") (pin "5") (pinfunction "VIO_5") (pintype "passive"))
      (node (ref "U40") (pin "2") (pinfunction "VCC_2") (pintype "passive"))
      (node (ref "U41") (pin "2") (pinfunction "VCC_2") (pintype "passive"))
      (node (ref "U42") (pin "2") (pinfunction "VCC_2") (pintype "passive"))
      (node (ref "U43") (pin "2") (pinfunction "VCC_2") (pintype "passive"))
      (node (ref "U44") (pin "13") (pinfunction "AVDD_13") (pintype "passive"))
      (node (ref "U44") (pin "18") (pinfunction "VDD_1_18") (pintype "passive"))
      (node (ref "U44") (pin "32") (pinfunction "VDD_2_32") (pintype "passive"))
      (node (ref "U44") (pin "43") (pinfunction "VDD_3_43") (pintype "passive"))
      (node (ref "U45") (pin "2") (pinfunction "VCC_2") (pintype "passive"))
      (node (ref "U46") (pin "2") (pinfunction "VCC_2") (pintype "passive"))
      (node (ref "U47") (pin "2") (pinfunction "VCC_2") (pintype "passive"))
      (node (ref "U48") (pin "2") (pinfunction "VCC_2") (pintype "passive"))
      (node (ref "U50") (pin "8") (pinfunction "VDD_8") (pintype "power_in"))
      (node (ref "Y1") (pin "4") (pinfunction "VDD_4") (pintype "passive"))
    )
    (net (code "95") (name "5V") (class "Default")
      (node (ref "C25") (pin "2") (pinfunction "2_2") (pintype "passive"))
      (node (ref "C26") (pin "2") (pinfunction "2_2") (pintype "passive"))
      (node (ref "C4") (pin "2") (pinfunction "2_2") (pintype "passive"))
      (node (ref "L1") (pin "1") (pinfunction "1_1") (pintype "passive"))
      (node (ref "Q7") (pin "4") (pinfunction "S2_4") (pintype "passive"))
      (node (ref "R1") (pin "2") (pinfunction "2_2") (pintype "passive"))
      (node (ref "R12") (pin "1") (pinfunction "1_1") (pintype "passive"))
      (node (ref "R172") (pin "1") (pinfunction "1_1") (pintype "passive"))
      (node (ref "R21") (pin "2") (pinfunction "2_2") (pintype "passive"))
      (node (ref "R42") (pin "2") (pinfunction "2_2") (pintype "passive"))
      (node (ref "R6") (pin "2") (pinfunction "2_2") (pintype "passive"))
      (node (ref "R8") (pin "1") (pinfunction "1_1") (pintype "passive"))
      (node (ref "R91") (pin "2") (pinfunction "2_2") (pintype "passive"))
      (node (ref "TP18") (pin "1") (pinfunction "1_1") (pintype "passive"))
      (node (ref "U2") (pin "7") (pinfunction "VCCB(HV)_7") (pintype "power_in"))
    )
    (net (code "96") (name "GND") (class "Default")
      (node (ref "C1") (pin "1") (pinfunction "1_1") (pintype "passive"))
      (node (ref "C10") (pin "2") (pinfunction "2_2") (pintype "passive"))
      (node (ref "C100") (pin "1") (pinfunction "1_1") (pintype "passive"))
      (node (ref "C101") (pin "1") (pinfunction "1_1") (pintype "passive"))
      (node (ref "C102") (pin "1") (pinfunction "1_1") (pintype "passive"))
      (node (ref "C103") (pin "1") (pinfunction "1_1") (pintype "passive"))
      (node (ref "C104") (pin "1") (pinfunction "1_1") (pintype "passive"))
      (node (ref "C105") (pin "1") (pinfunction "1_1") (pintype "passive"))
      (node (ref "C106") (pin "1") (pinfunction "1_1") (pintype "passive"))
      (node (ref "C107") (pin "1") (pinfunction "1_1") (pintype "passive"))
      (node (ref "C108") (pin "1") (pinfunction "1_1") (pintype "passive"))
      (node (ref "C109") (pin "1") (pinfunction "1_1") (pintype "passive"))
      (node (ref "C11") (pin "1") (pinfunction "1_1") (pintype "passive"))
      (node (ref "C110") (pin "1") (pinfunction "1_1") (pintype "passive"))
      (node (ref "C111") (pin "1") (pinfunction "1_1") (pintype "passive"))
      (node (ref "C112") (pin "1") (pinfunction "1_1") (pintype "passive"))
      (node (ref "C113") (pin "1") (pinfunction "1_1") (pintype "passive"))
      (node (ref "C114") (pin "1") (pinfunction "1_1") (pintype "passive"))
      (node (ref "C115") (pin "1") (pinfunction "1_1") (pintype "passive"))
      (node (ref "C116") (pin "1") (pinfunction "1_1") (pintype "passive"))
      (node (ref "C117") (pin "1") (pinfunction "1_1") (pintype "passive"))
      (node (ref "C12") (pin "1") (pinfunction "1_1") (pintype "passive"))
      (node (ref "C13") (pin "1") (pinfunction "1_1") (pintype "passive"))
      (node (ref "C14") (pin "2") (pinfunction "2_2") (pintype "passive"))
      (node (ref "C15") (pin "2") (pinfunction "2_2") (pintype "passive"))
      (node (ref "C16") (pin "1") (pinfunction "1_1") (pintype "passive"))
      (node (ref "C17") (pin "2") (pinfunction "2_2") (pintype "passive"))
      (node (ref "C18") (pin "1") (pinfunction "1_1") (pintype "passive"))
      (node (ref "C19") (pin "2") (pinfunction "2_2") (pintype "passive"))
      (node (ref "C2") (pin "2") (pinfunction "2_2") (pintype "passive"))
      (node (ref "C20") (pin "2") (pinfunction "2_2") (pintype "passive"))
      (node (ref "C21") (pin "2") (pinfunction "2_2") (pintype "passive"))
      (node (ref "C22") (pin "2") (pinfunction "2_2") (pintype "passive"))
      (node (ref "C23") (pin "1") (pinfunction "1_1") (pintype "passive"))
      (node (ref "C24") (pin "2") (pinfunction "2_2") (pintype "passive"))
      (node (ref "C25") (pin "1") (pinfunction "1_1") (pintype "passive"))
      (node (ref "C28") (pin "1") (pinfunction "1_1") (pintype "passive"))
      (node (ref "C29") (pin "1") (pinfunction "1_1") (pintype "passive"))
      (node (ref "C3") (pin "1") (pinfunction "1_1") (pintype "passive"))
      (node (ref "C30") (pin "2") (pinfunction "2_2") (pintype "passive"))
      (node (ref "C33") (pin "1") (pinfunction "1_1") (pintype "passive"))
      (node (ref "C34") (pin "1") (pinfunction "1_1") (pintype "passive"))
      (node (ref "C35") (pin "2") (pinfunction "2_2") (pintype "passive"))
      (node (ref "C36") (pin "1") (pinfunction "1_1") (pintype "passive"))
      (node (ref "C37") (pin "1") (pinfunction "1_1") (pintype "passive"))
      (node (ref "C38") (pin "1") (pinfunction "1_1") (pintype "passive"))
      (node (ref "C39") (pin "2") (pinfunction "2_2") (pintype "passive"))
      (node (ref "C4") (pin "1") (pinfunction "1_1") (pintype "passive"))
      (node (ref "C40") (pin "2") (pinfunction "2_2") (pintype "passive"))
      (node (ref "C41") (pin "1") (pinfunction "1_1") (pintype "passive"))
      (node (ref "C42") (pin "1") (pinfunction "1_1") (pintype "passive"))
      (node (ref "C43") (pin "2") (pinfunction "2_2") (pintype "passive"))
      (node (ref "C44") (pin "1") (pinfunction "1_1") (pintype "passive"))
      (node (ref "C45") (pin "2") (pinfunction "2_2") (pintype "passive"))
      (node (ref "C46") (pin "1") (pinfunction "1_1") (pintype "passive"))
      (node (ref "C47") (pin "2") (pinfunction "2_2") (pintype "passive"))
      (node (ref "C48") (pin "1") (pinfunction "1_1") (pintype "passive"))
      (node (ref "C49") (pin "2") (pinfunction "2_2") (pintype "passive"))
      (node (ref "C5") (pin "1") (pinfunction "1_1") (pintype "passive"))
      (node (ref "C50") (pin "1") (pinfunction "1_1") (pintype "passive"))
      (node (ref "C52") (pin "1") (pinfunction "1_1") (pintype "passive"))
      (node (ref "C53") (pin "2") (pinfunction "2_2") (pintype "passive"))
      (node (ref "C54") (pin "1") (pinfunction "1_1") (pintype "passive"))
      (node (ref "C55") (pin "2") (pinfunction "2_2") (pintype "passive"))
      (node (ref "C56") (pin "1") (pinfunction "1_1") (pintype "passive"))
      (node (ref "C57") (pin "1") (pinfunction "1_1") (pintype "passive"))
      (node (ref "C58") (pin "1") (pinfunction "1_1") (pintype "passive"))
      (node (ref "C6") (pin "2") (pinfunction "2_2") (pintype "passive"))
      (node (ref "C60") (pin "1") (pinfunction "1_1") (pintype "passive"))
      (node (ref "C61") (pin "1") (pinfunction "1_1") (pintype "passive"))
      (node (ref "C62") (pin "1") (pinfunction "1_1") (pintype "passive"))
      (node (ref "C65") (pin "1") (pinfunction "1_1") (pintype "passive"))
      (node (ref "C67") (pin "1") (pinfunction "1_1") (pintype "passive"))
      (node (ref "C68") (pin "1") (pinfunction "1_1") (pintype "passive"))
      (node (ref "C69") (pin "2") (pinfunction "2_2") (pintype "passive"))
      (node (ref "C7") (pin "1") (pinfunction "1_1") (pintype "passive"))
      (node (ref "C70") (pin "1") (pinfunction "1_1") (pintype "passive"))
      (node (ref "C71") (pin "1") (pinfunction "1_1") (pintype "passive"))
      (node (ref "C73") (pin "1") (pinfunction "1_1") (pintype "passive"))
      (node (ref "C75") (pin "1") (pinfunction "1_1") (pintype "passive"))
      (node (ref "C77") (pin "1") (pinfunction "1_1") (pintype "passive"))
      (node (ref "C79") (pin "1") (pinfunction "1_1") (pintype "passive"))
      (node (ref "C8") (pin "2") (pinfunction "2_2") (pintype "passive"))
      (node (ref "C80") (pin "1") (pinfunction "1_1") (pintype "passive"))
      (node (ref "C81") (pin "1") (pinfunction "1_1") (pintype "passive"))
      (node (ref "C82") (pin "1") (pinfunction "1_1") (pintype "passive"))
      (node (ref "C83") (pin "1") (pinfunction "1_1") (pintype "passive"))
      (node (ref "C84") (pin "1") (pinfunction "1_1") (pintype "passive"))
      (node (ref "C85") (pin "1") (pinfunction "1_1") (pintype "passive"))
      (node (ref "C86") (pin "1") (pinfunction "1_1") (pintype "passive"))
      (node (ref "C87") (pin "1") (pinfunction "1_1") (pintype "passive"))
      (node (ref "C88") (pin "1") (pinfunction "1_1") (pintype "passive"))
      (node (ref "C89") (pin "1") (pinfunction "1_1") (pintype "passive"))
      (node (ref "C9") (pin "2") (pinfunction "2_2") (pintype "passive"))
      (node (ref "C93") (pin "1") (pinfunction "1_1") (pintype "passive"))
      (node (ref "C94") (pin "1") (pinfunction "1_1") (pintype "passive"))
      (node (ref "C95") (pin "1") (pinfunction "1_1") (pintype "passive"))
      (node (ref "C96") (pin "1") (pinfunction "1_1") (pintype "passive"))
      (node (ref "C97") (pin "1") (pinfunction "1_1") (pintype "passive"))
      (node (ref "C99") (pin "1") (pinfunction "1_1") (pintype "passive"))
      (node (ref "D2") (pin "3") (pinfunction "CC_3") (pintype "passive"))
      (node (ref "J1") (pin "11") (pinfunction "11_11") (pintype "passive"))
      (node (ref "J1") (pin "12") (pinfunction "12_12") (pintype "passive"))
      (node (ref "J1") (pin "13") (pinfunction "13_13") (pintype "passive"))
      (node (ref "J1") (pin "14") (pinfunction "14_14") (pintype "passive"))
      (node (ref "J1") (pin "15") (pinfunction "15_15") (pintype "passive"))
      (node (ref "J3") (pin "3") (pinfunction "3_3") (pintype "passive"))
      (node (ref "J52") (pin "1") (pinfunction "1_1") (pintype "passive"))
      (node (ref "J53") (pin "1") (pinfunction "1_1") (pintype "passive"))
      (node (ref "J57") (pin "1") (pinfunction "1_1") (pintype "passive"))
      (node (ref "Q10") (pin "1") (pinfunction "R2_1") (pintype "passive"))
      (node (ref "Q11") (pin "1") (pinfunction "R2_1") (pintype "passive"))
      (node (ref "Q2") (pin "2") (pinfunction "E_2") (pintype "passive"))
      (node (ref "Q4") (pin "2") (pinfunction "E_2") (pintype "passive"))
      (node (ref "Q7") (pin "1") (pinfunction "R2_1") (pintype "passive"))
      (node (ref "Q8") (pin "2") (pinfunction "E_2") (pintype "passive"))
      (node (ref "Q9") (pin "2") (pinfunction "E_2") (pintype "passive"))
      (node (ref "R102") (pin "2") (pinfunction "2_2") (pintype "passive"))
      (node (ref "R11") (pin "2") (pinfunction "2_2") (pintype "passive"))
      (node (ref "R14") (pin "1") (pinfunction "1_1") (pintype "passive"))
      (node (ref "R142") (pin "2") (pinfunction "2_2") (pintype "passive"))
      (node (ref "R15") (pin "1") (pinfunction "1_1") (pintype "passive"))
      (node (ref "R164") (pin "1") (pinfunction "1_1") (pintype "passive"))
      (node (ref "R18") (pin "2") (pinfunction "2_2") (pintype "passive"))
      (node (ref "R183") (pin "1") (pinfunction "1_1") (pintype "passive"))
      (node (ref "R41") (pin "1") (pinfunction "1_1") (pintype "passive"))
      (node (ref "R45") (pin "1") (pinfunction "1_1") (pintype "passive"))
      (node (ref "R70") (pin "1") (pinfunction "1_1") (pintype "passive"))
      (node (ref "R74") (pin "1") (pinfunction "1_1") (pintype "passive"))
      (node (ref "R9") (pin "2") (pinfunction "2_2") (pintype "passive"))
      (node (ref "R95") (pin "1") (pinfunction "1_1") (pintype "passive"))
      (node (ref "R97") (pin "2") (pinfunction "2_2") (pintype "passive"))
      (node (ref "R98") (pin "1") (pinfunction "1_1") (pintype "passive"))
      (node (ref "R99") (pin "1") (pinfunction "1_1") (pintype "passive"))
      (node (ref "U1") (pin "3") (pinfunction "GND_3") (pintype "power_in"))
      (node (ref "U10") (pin "5") (pinfunction "-VS_5") (pintype "passive"))
      (node (ref "U11") (pin "2") (pinfunction "GND_2") (pintype "power_in"))
      (node (ref "U11") (pin "3") (pinfunction "CTL_3") (pintype "input"))
      (node (ref "U12") (pin "2") (pinfunction "GND_2") (pintype "power_in"))
      (node (ref "U12") (pin "3") (pinfunction "CTL_3") (pintype "input"))
      (node (ref "U13") (pin "10") (pinfunction "GND_10") (pintype "passive"))
      (node (ref "U14") (pin "4") (pinfunction "GND_4") (pintype "passive"))
      (node (ref "U15") (pin "10") (pinfunction "VSS_10") (pintype "passive"))
      (node (ref "U16") (pin "4") (pinfunction "VSS_4") (pintype "power_in"))
      (node (ref "U17") (pin "10") (pinfunction "VSS_10") (pintype "passive"))
      (node (ref "U18") (pin "10") (pinfunction "VSS_10") (pintype "passive"))
      (node (ref "U19") (pin "10") (pinfunction "VSS_10") (pintype "passive"))
      (node (ref "U2") (pin "2") (pinfunction "GND_2") (pintype "power_in"))
      (node (ref "U20") (pin "2") (pinfunction "VSS_2") (pintype "passive"))
      (node (ref "U21") (pin "10") (pinfunction "VSS_10") (pintype "passive"))
      (node (ref "U22") (pin "10") (pinfunction "VSS_10") (pintype "passive"))
      (node (ref "U23") (pin "10") (pinfunction "VSS_10") (pintype "passive"))
      (node (ref "U24") (pin "3") (pinfunction "GND_3") (pintype "passive"))
      (node (ref "U25") (pin "10") (pinfunction "VSS_10") (pintype "passive"))
      (node (ref "U26") (pin "4") (pinfunction "VSS_4") (pintype "power_in"))
      (node (ref "U27") (pin "3") (pinfunction "GND_3") (pintype "power_in"))
      (node (ref "U28") (pin "10") (pinfunction "VSS_10") (pintype "passive"))
      (node (ref "U29") (pin "10") (pinfunction "VSS_10") (pintype "passive"))
      (node (ref "U3") (pin "3") (pinfunction "GND_3") (pintype "power_in"))
      (node (ref "U30") (pin "10") (pinfunction "VSS_10") (pintype "passive"))
      (node (ref "U31") (pin "10") (pinfunction "VSS_10") (pintype "passive"))
      (node (ref "U32") (pin "4") (pinfunction "GND_4") (pintype "passive"))
      (node (ref "U33") (pin "17") (pinfunction "AGND_3_17") (pintype "passive"))
      (node (ref "U33") (pin "20") (pinfunction "AGND_4_20") (pintype "passive"))
      (node (ref "U33") (pin "4") (pinfunction "AGND_1_4") (pintype "passive"))
      (node (ref "U33") (pin "8") (pinfunction "AGND_2_8") (pintype "passive"))
      (node (ref "U34") (pin "10") (pinfunction "VSS_10") (pintype "passive"))
      (node (ref "U35") (pin "10") (pinfunction "VSS_10") (pintype "passive"))
      (node (ref "U36") (pin "10") (pinfunction "VSS_10") (pintype "passive"))
      (node (ref "U37") (pin "10") (pinfunction "VSS_10") (pintype "passive"))
      (node (ref "U38") (pin "21") (pinfunction "~{WR}_21") (pintype "passive"))
      (node (ref "U38") (pin "23") (pinfunction "GND_23") (pintype "passive"))
      (node (ref "U38") (pin "24") (pinfunction "VSS_24") (pintype "passive"))
      (node (ref "U38") (pin "43") (pinfunction "D_43") (pintype "passive"))
      (node (ref "U38") (pin "49") (pinfunction "EP_49") (pintype "passive"))
      (node (ref "U39") (pin "4") (pinfunction "VSS_4") (pintype "power_in"))
      (node (ref "U4") (pin "2") (pinfunction "VSS_2") (pintype "passive"))
      (node (ref "U40") (pin "10") (pinfunction "VSS_10") (pintype "passive"))
      (node (ref "U41") (pin "10") (pinfunction "VSS_10") (pintype "passive"))
      (node (ref "U42") (pin "10") (pinfunction "VSS_10") (pintype "passive"))
      (node (ref "U43") (pin "10") (pinfunction "VSS_10") (pintype "passive"))
      (node (ref "U44") (pin "14") (pinfunction "AVSS_14") (pintype "passive"))
      (node (ref "U44") (pin "19") (pinfunction "VSS_1_19") (pintype "passive"))
      (node (ref "U44") (pin "31") (pinfunction "VSS_2_31") (pintype "passive"))
      (node (ref "U44") (pin "42") (pinfunction "VSS_3_42") (pintype "passive"))
      (node (ref "U45") (pin "10") (pinfunction "VSS_10") (pintype "passive"))
      (node (ref "U46") (pin "10") (pinfunction "VSS_10") (pintype "passive"))
      (node (ref "U47") (pin "10") (pinfunction "VSS_10") (pintype "passive"))
      (node (ref "U48") (pin "10") (pinfunction "VSS_10") (pintype "passive"))
      (node (ref "U5") (pin "2") (pinfunction "GND_2") (pintype "power_in"))
      (node (ref "U5") (pin "3") (pinfunction "CTL_3") (pintype "input"))
      (node (ref "U50") (pin "4") (pinfunction "VSS_4") (pintype "power_in"))
      (node (ref "U6") (pin "17") (pinfunction "GND_17") (pintype "passive"))
      (node (ref "U6") (pin "4") (pinfunction "MODE/SYNC_4") (pintype "passive"))
      (node (ref "U6") (pin "5") (pinfunction "PHASE_5") (pintype "passive"))
      (node (ref "U6") (pin "7") (pinfunction "ILIM_7") (pintype "passive"))
      (node (ref "U7") (pin "3") (pinfunction "GND_3") (pintype "power_in"))
      (node (ref "U8") (pin "2") (pinfunction "GND_2") (pintype "power_in"))
      (node (ref "U8") (pin "3") (pinfunction "CTL_3") (pintype "input"))
      (node (ref "U9") (pin "4") (pinfunction "GND_4") (pintype "passive"))
      (node (ref "Y1") (pin "2") (pinfunction "GND_2") (pintype "passive"))
    )
    (net (code "97") (name "Net-(C31-Pad1)") (class "Default")
      (node (ref "C31") (pin "1") (pinfunction "1_1") (pintype "passive"))
      (node (ref "C32") (pin "2") (pinfunction "2_2") (pintype "passive"))
      (node (ref "U13") (pin "3") (pinfunction "GND_3") (pintype "passive"))
    )
    (net (code "98") (name "Net-(C36-Pad2)") (class "Default")
      (node (ref "C36") (pin "2") (pinfunction "2_2") (pintype "passive"))
      (node (ref "R16") (pin "2") (pinfunction "2_2") (pintype "passive"))
    )
    (net (code "99") (name "Net-(C41-Pad2)") (class "Default")
      (node (ref "C41") (pin "2") (pinfunction "2_2") (pintype "passive"))
      (node (ref "R67") (pin "2") (pinfunction "2_2") (pintype "passive"))
    )
    (net (code "100") (name "Net-(C116-Pad2)") (class "Default")
      (node (ref "C116") (pin "2") (pinfunction "2_2") (pintype "passive"))
      (node (ref "R161") (pin "1") (pinfunction "1_1") (pintype "passive"))
      (node (ref "R163") (pin "1") (pinfunction "1_1") (pintype "passive"))
    )
    (net (code "101") (name "Net-(D1-K1)") (class "Default")
      (node (ref "C12") (pin "2") (pinfunction "2_2") (pintype "passive"))
      (node (ref "D1") (pin "1") (pinfunction "K1_1") (pintype "passive"))
      (node (ref "L3") (pin "1") (pinfunction "1_1") (pintype "passive"))
      (node (ref "Q1") (pin "2") (pinfunction "SOURCE_2") (pintype "passive"))
      (node (ref "Q3") (pin "2") (pinfunction "SOURCE_2") (pintype "passive"))
      (node (ref "Q5") (pin "2") (pinfunction "SOURCE_2") (pintype "passive"))
      (node (ref "U11") (pin "6") (pinfunction "SENSE_6") (pintype "input"))
      (node (ref "U5") (pin "6") (pinfunction "SENSE_6") (pintype "input"))
      (node (ref "U8") (pin "6") (pinfunction "SENSE_6") (pintype "input"))
    )
    (net (code "102") (name "Net-(D1-K2)") (class "Default")
      (node (ref "C37") (pin "2") (pinfunction "2_2") (pintype "passive"))
      (node (ref "D1") (pin "2") (pinfunction "K2_2") (pintype "passive"))
      (node (ref "L5") (pin "1") (pinfunction "1_1") (pintype "passive"))
      (node (ref "Q6") (pin "2") (pinfunction "SOURCE_2") (pintype "passive"))
      (node (ref "U12") (pin "6") (pinfunction "SENSE_6") (pintype "input"))
    )
    (net (code "103") (name "Net-(D3-K)") (class "Default")
      (node (ref "D3") (pin "1") (pinfunction "K_1") (pintype "passive"))
      (node (ref "D4") (pin "1") (pinfunction "K_1") (pintype "passive"))
      (node (ref "U6") (pin "2") (pinfunction "SVIN_2") (pintype "passive"))
    )
    (net (code "104") (name "Net-(D5-A)") (class "Default")
      (node (ref "D5") (pin "2") (pinfunction "A_2") (pintype "passive"))
      (node (ref "U7") (pin "4") (pinfunction "Y_4") (pintype "passive"))
    )
    (net (code "105") (name "Net-(D5-C)") (class "Default")
      (node (ref "D5") (pin "1") (pinfunction "C_1") (pintype "passive"))
      (node (ref "U24") (pin "6") (pinfunction "S2_6") (pintype "passive"))
    )
    (net (code "106") (name "Net-(D6-A)") (class "Default")
      (node (ref "D6") (pin "2") (pinfunction "A_2") (pintype "passive"))
      (node (ref "U27") (pin "4") (pinfunction "Y_4") (pintype "passive"))
    )
    (net (code "107") (name "Net-(D6-C)") (class "Default")
      (node (ref "D6") (pin "1") (pinfunction "C_1") (pintype "passive"))
      (node (ref "U24") (pin "4") (pinfunction "S1_4") (pintype "passive"))
    )
    (net (code "108") (name "Net-(D7-K)") (class "Default")
      (node (ref "D7") (pin "1") (pinfunction "K_1") (pintype "passive"))
      (node (ref "R173") (pin "2") (pinfunction "2_2") (pintype "passive"))
    )
    (net (code "109") (name "Net-(F1-Pad1)") (class "Default")
      (node (ref "F1") (pin "1") (pinfunction "1_1") (pintype "passive"))
      (node (ref "L4") (pin "1") (pinfunction "1_1") (pintype "passive"))
    )
    (net (code "110") (name "Net-(L4-Pad2)") (class "Default")
      (node (ref "L4") (pin "2") (pinfunction "2_2") (pintype "passive"))
      (node (ref "R2") (pin "2") (pinfunction "2_2") (pintype "passive"))
    )
    (net (code "111") (name "Net-(Q1-GATE)") (class "Default")
      (node (ref "Q1") (pin "1") (pinfunction "GATE_1") (pintype "passive"))
      (node (ref "U5") (pin "5") (pinfunction "GATE_5") (pintype "output"))
    )
    (net (code "112") (name "Net-(Q2-B)") (class "Default")
      (node (ref "Q2") (pin "1") (pinfunction "B_1") (pintype "passive"))
      (node (ref "R7") (pin "1") (pinfunction "1_1") (pintype "passive"))
      (node (ref "R9") (pin "1") (pinfunction "1_1") (pintype "passive"))
    )
    (net (code "113") (name "Net-(Q2-C)") (class "Default")
      (node (ref "Q2") (pin "3") (pinfunction "C_3") (pintype "passive"))
      (node (ref "R5") (pin "2") (pinfunction "2_2") (pintype "passive"))
      (node (ref "U4") (pin "8") (pinfunction "STBY_8") (pintype "passive"))
    )
    (net (code "114") (name "Net-(Q3-GATE)") (class "Default")
      (node (ref "Q3") (pin "1") (pinfunction "GATE_1") (pintype "passive"))
      (node (ref "U8") (pin "5") (pinfunction "GATE_5") (pintype "output"))
    )
    (net (code "115") (name "Net-(Q4-B)") (class "Default")
      (node (ref "Q4") (pin "1") (pinfunction "B_1") (pintype "passive"))
      (node (ref "R10") (pin "1") (pinfunction "1_1") (pintype "passive"))
      (node (ref "R11") (pin "1") (pinfunction "1_1") (pintype "passive"))
      (node (ref "TP3") (pin "1") (pinfunction "1_1") (pintype "passive"))
    )
    (net (code "116") (name "Net-(Q5-GATE)") (class "Default")
      (node (ref "Q5") (pin "1") (pinfunction "GATE_1") (pintype "passive"))
      (node (ref "U11") (pin "5") (pinfunction "GATE_5") (pintype "output"))
    )
    (net (code "117") (name "Net-(Q6-GATE)") (class "Default")
      (node (ref "Q6") (pin "1") (pinfunction "GATE_1") (pintype "passive"))
      (node (ref "U12") (pin "5") (pinfunction "GATE_5") (pintype "output"))
    )
    (net (code "118") (name "Net-(Q7-ON{slash}OFF)") (class "Default")
      (node (ref "Q7") (pin "5") (pinfunction "ON/OFF_5") (pintype "passive"))
      (node (ref "R173") (pin "1") (pinfunction "1_1") (pintype "passive"))
    )
    (net (code "119") (name "Net-(Q7-R1_C1)") (class "Default")
      (node (ref "C128") (pin "2") (pinfunction "2_2") (pintype "passive"))
      (node (ref "Q7") (pin "6") (pinfunction "R1_C1_6") (pintype "passive"))
      (node (ref "R172") (pin "2") (pinfunction "2_2") (pintype "passive"))
    )
    (net (code "120") (name "Net-(Q8-B)") (class "Default")
      (node (ref "Q8") (pin "1") (pinfunction "B_1") (pintype "passive"))
      (node (ref "R141") (pin "1") (pinfunction "1_1") (pintype "passive"))
      (node (ref "R142") (pin "1") (pinfunction "1_1") (pintype "passive"))
    )
    (net (code "121") (name "Net-(Q8-C)") (class "Default")
      (node (ref "Q8") (pin "3") (pinfunction "C_3") (pintype "passive"))
      (node (ref "R139") (pin "1") (pinfunction "1_1") (pintype "passive"))
      (node (ref "Y1") (pin "1") (pinfunction "!ST_1") (pintype "passive"))
    )
    (net (code "122") (name "Net-(Q9-B)") (class "Default")
      (node (ref "Q9") (pin "1") (pinfunction "B_1") (pintype "passive"))
      (node (ref "R101") (pin "1") (pinfunction "1_1") (pintype "passive"))
      (node (ref "R102") (pin "1") (pinfunction "1_1") (pintype "passive"))
    )
    (net (code "123") (name "Net-(Q10-ON{slash}OFF)") (class "Default")
      (node (ref "Q10") (pin "5") (pinfunction "ON/OFF_5") (pintype "passive"))
      (node (ref "R175") (pin "1") (pinfunction "1_1") (pintype "passive"))
    )
    (net (code "124") (name "Net-(Q10-R1_C1)") (class "Default")
      (node (ref "C129") (pin "2") (pinfunction "2_2") (pintype "passive"))
      (node (ref "Q10") (pin "6") (pinfunction "R1_C1_6") (pintype "passive"))
      (node (ref "R174") (pin "2") (pinfunction "2_2") (pintype "passive"))
    )
    (net (code "125") (name "Net-(Q11-ON{slash}OFF)") (class "Default")
      (node (ref "Q11") (pin "5") (pinfunction "ON/OFF_5") (pintype "passive"))
      (node (ref "R184") (pin "1") (pinfunction "1_1") (pintype "passive"))
    )
    (net (code "126") (name "Net-(Q11-R1_C1)") (class "Default")
      (node (ref "C141") (pin "2") (pinfunction "2_2") (pintype "passive"))
      (node (ref "Q11") (pin "6") (pinfunction "R1_C1_6") (pintype "passive"))
      (node (ref "R182") (pin "2") (pinfunction "2_2") (pintype "passive"))
    )
    (net (code "127") (name "Net-(U1-A)") (class "Default")
      (node (ref "C33") (pin "2") (pinfunction "2_2") (pintype "passive"))
      (node (ref "R17") (pin "2") (pinfunction "2_2") (pintype "passive"))
      (node (ref "R18") (pin "1") (pinfunction "1_1") (pintype "passive"))
      (node (ref "U1") (pin "2") (pinfunction "A_2") (pintype "input"))
      (node (ref "U24") (pin "5") (pinfunction "D_5") (pintype "passive"))
      (node (ref "U3") (pin "2") (pinfunction "A_2") (pintype "passive"))
    )
    (net (code "128") (name "Net-(U1-VCC)") (class "Default")
      (node (ref "C1") (pin "2") (pinfunction "2_2") (pintype "passive"))
      (node (ref "C2") (pin "1") (pinfunction "1_1") (pintype "passive"))
      (node (ref "R1") (pin "1") (pinfunction "1_1") (pintype "passive"))
      (node (ref "R4") (pin "1") (pinfunction "1_1") (pintype "passive"))
      (node (ref "U1") (pin "5") (pinfunction "VCC_5") (pintype "power_in"))
    )
    (net (code "129") (name "Net-(U3-VCC)") (class "Default")
      (node (ref "C18") (pin "2") (pinfunction "2_2") (pintype "passive"))
      (node (ref "C19") (pin "1") (pinfunction "1_1") (pintype "passive"))
      (node (ref "R6") (pin "1") (pinfunction "1_1") (pintype "passive"))
      (node (ref "U3") (pin "5") (pinfunction "VCC_5") (pintype "power_in"))
    )
    (net (code "130") (name "Net-(U6-FB1)") (class "Default")
      (node (ref "C26") (pin "1") (pinfunction "1_1") (pintype "passive"))
      (node (ref "R12") (pin "2") (pinfunction "2_2") (pintype "passive"))
      (node (ref "R15") (pin "2") (pinfunction "2_2") (pintype "passive"))
      (node (ref "U6") (pin "13") (pinfunction "FB1_13") (pintype "passive"))
    )
    (net (code "131") (name "Net-(U6-FB2)") (class "Default")
      (node (ref "C27") (pin "1") (pinfunction "1_1") (pintype "passive"))
      (node (ref "R13") (pin "2") (pinfunction "2_2") (pintype "passive"))
      (node (ref "R14") (pin "2") (pinfunction "2_2") (pintype "passive"))
      (node (ref "U6") (pin "11") (pinfunction "FB2_11") (pintype "passive"))
    )
    (net (code "132") (name "Net-(U6-INTVCC)") (class "Default")
      (node (ref "C22") (pin "1") (pinfunction "1_1") (pintype "passive"))
      (node (ref "U6") (pin "12") (pinfunction "INTVCC_12") (pintype "passive"))
    )
    (net (code "133") (name "Net-(U6-SW1)") (class "Default")
      (node (ref "L1") (pin "2") (pinfunction "2_2") (pintype "passive"))
      (node (ref "U6") (pin "16") (pinfunction "SW1_16") (pintype "passive"))
    )
    (net (code "134") (name "Net-(U6-SW2)") (class "Default")
      (node (ref "L2") (pin "1") (pinfunction "1_1") (pintype "passive"))
      (node (ref "U6") (pin "9") (pinfunction "SW2_9") (pintype "passive"))
    )
    (net (code "135") (name "Net-(U7-VCC)") (class "Default")
      (node (ref "C42") (pin "2") (pinfunction "2_2") (pintype "passive"))
      (node (ref "C43") (pin "1") (pinfunction "1_1") (pintype "passive"))
      (node (ref "R21") (pin "1") (pinfunction "1_1") (pintype "passive"))
      (node (ref "U7") (pin "5") (pinfunction "VCC_5") (pintype "power_in"))
    )
    (net (code "136") (name "Net-(U10-+IN)") (class "Default")
      (node (ref "TP4") (pin "1") (pinfunction "1_1") (pintype "passive"))
      (node (ref "U10") (pin "4") (pinfunction "+IN_4") (pintype "passive"))
      (node (ref "U9") (pin "5") (pinfunction "Vout+_5") (pintype "passive"))
    )
    (net (code "137") (name "Net-(U10--IN)") (class "Default")
      (node (ref "TP6") (pin "1") (pinfunction "1_1") (pintype "passive"))
      (node (ref "U10") (pin "1") (pinfunction "-IN_1") (pintype "passive"))
      (node (ref "U9") (pin "1") (pinfunction "Vout-_1") (pintype "passive"))
    )
    (net (code "138") (name "Net-(U10-REF)") (class "Default")
      (node (ref "TP7") (pin "1") (pinfunction "1_1") (pintype "passive"))
      (node (ref "U10") (pin "6") (pinfunction "REF_6") (pintype "passive"))
      (node (ref "U20") (pin "1") (pinfunction "VOUT_1") (pintype "passive"))
      (node (ref "U20") (pin "4") (pinfunction "IN-_4") (pintype "passive"))
    )
    (net (code "139") (name "Net-(U10-RG_1)") (class "Default")
      (node (ref "R92") (pin "2") (pinfunction "2_2") (pintype "passive"))
      (node (ref "U10") (pin "2") (pinfunction "RG_1_2") (pintype "passive"))
    )
    (net (code "140") (name "Net-(U10-RG_2)") (class "Default")
      (node (ref "R92") (pin "1") (pinfunction "1_1") (pintype "passive"))
      (node (ref "U10") (pin "3") (pinfunction "RG_2_3") (pintype "passive"))
    )
    (net (code "141") (name "Net-(U10-VOUT)") (class "Default")
      (node (ref "R73") (pin "2") (pinfunction "2_2") (pintype "passive"))
      (node (ref "U10") (pin "7") (pinfunction "VOUT_7") (pintype "passive"))
    )
    (net (code "142") (name "Net-(U15-DQ3{slash}~{HOLD})") (class "Default")
      (node (ref "R25") (pin "1") (pinfunction "1_1") (pintype "passive"))
      (node (ref "U15") (pin "1") (pinfunction "DQ3/~{HOLD}_1") (pintype "passive"))
    )
    (net (code "143") (name "Net-(U15-~{RESET})") (class "Default")
      (node (ref "R23") (pin "1") (pinfunction "1_1") (pintype "passive"))
      (node (ref "U15") (pin "3") (pinfunction "~{RESET}_3") (pintype "passive"))
    )
    (net (code "144") (name "Net-(U15-~{W}{slash}DQ2)") (class "Default")
      (node (ref "R24") (pin "1") (pinfunction "1_1") (pintype "passive"))
      (node (ref "U15") (pin "9") (pinfunction "~{W}/DQ2_9") (pintype "passive"))
    )
    (net (code "145") (name "Net-(U16A-VINA+)") (class "Default")
      (node (ref "R39") (pin "1") (pinfunction "1_1") (pintype "passive"))
      (node (ref "R41") (pin "2") (pinfunction "2_2") (pintype "passive"))
      (node (ref "U16") (pin "3") (pinfunction "VINA+_3") (pintype "input"))
    )
    (net (code "146") (name "Net-(U16A-VINA-)") (class "Default")
      (node (ref "R38") (pin "2") (pinfunction "2_2") (pintype "passive"))
      (node (ref "U16") (pin "1") (pinfunction "VOUTA_1") (pintype "output"))
      (node (ref "U16") (pin "2") (pinfunction "VINA-_2") (pintype "input"))
    )
    (net (code "147") (name "Net-(U16B-VINB+)") (class "Default")
      (node (ref "R44") (pin "1") (pinfunction "1_1") (pintype "passive"))
      (node (ref "R45") (pin "2") (pinfunction "2_2") (pintype "passive"))
      (node (ref "U16") (pin "5") (pinfunction "VINB+_5") (pintype "input"))
    )
    (net (code "148") (name "Net-(U16B-VINB-)") (class "Default")
      (node (ref "R43") (pin "2") (pinfunction "2_2") (pintype "passive"))
      (node (ref "U16") (pin "6") (pinfunction "VINB-_6") (pintype "input"))
      (node (ref "U16") (pin "7") (pinfunction "VOUTB_7") (pintype "output"))
    )
    (net (code "149") (name "Net-(U17-DQ3{slash}~{HOLD})") (class "Default")
      (node (ref "R29") (pin "1") (pinfunction "1_1") (pintype "passive"))
      (node (ref "U17") (pin "1") (pinfunction "DQ3/~{HOLD}_1") (pintype "passive"))
    )
    (net (code "150") (name "Net-(U17-~{RESET})") (class "Default")
      (node (ref "R27") (pin "1") (pinfunction "1_1") (pintype "passive"))
      (node (ref "U17") (pin "3") (pinfunction "~{RESET}_3") (pintype "passive"))
    )
    (net (code "151") (name "Net-(U17-~{W}{slash}DQ2)") (class "Default")
      (node (ref "R28") (pin "1") (pinfunction "1_1") (pintype "passive"))
      (node (ref "U17") (pin "9") (pinfunction "~{W}/DQ2_9") (pintype "passive"))
    )
    (net (code "152") (name "Net-(U18-DQ3{slash}~{HOLD})") (class "Default")
      (node (ref "R33") (pin "1") (pinfunction "1_1") (pintype "passive"))
      (node (ref "U18") (pin "1") (pinfunction "DQ3/~{HOLD}_1") (pintype "passive"))
    )
    (net (code "153") (name "Net-(U18-~{RESET})") (class "Default")
      (node (ref "R31") (pin "1") (pinfunction "1_1") (pintype "passive"))
      (node (ref "U18") (pin "3") (pinfunction "~{RESET}_3") (pintype "passive"))
    )
    (net (code "154") (name "Net-(U18-~{W}{slash}DQ2)") (class "Default")
      (node (ref "R32") (pin "1") (pinfunction "1_1") (pintype "passive"))
      (node (ref "U18") (pin "9") (pinfunction "~{W}/DQ2_9") (pintype "passive"))
    )
    (net (code "155") (name "Net-(U19-DQ3{slash}~{HOLD})") (class "Default")
      (node (ref "R37") (pin "1") (pinfunction "1_1") (pintype "passive"))
      (node (ref "U19") (pin "1") (pinfunction "DQ3/~{HOLD}_1") (pintype "passive"))
    )
    (net (code "156") (name "Net-(U19-~{RESET})") (class "Default")
      (node (ref "R35") (pin "1") (pinfunction "1_1") (pintype "passive"))
      (node (ref "U19") (pin "3") (pinfunction "~{RESET}_3") (pintype "passive"))
    )
    (net (code "157") (name "Net-(U19-~{W}{slash}DQ2)") (class "Default")
      (node (ref "R36") (pin "1") (pinfunction "1_1") (pintype "passive"))
      (node (ref "U19") (pin "9") (pinfunction "~{W}/DQ2_9") (pintype "passive"))
    )
    (net (code "158") (name "Net-(U20-IN+)") (class "Default")
      (node (ref "R96") (pin "2") (pinfunction "2_2") (pintype "passive"))
      (node (ref "R97") (pin "1") (pinfunction "1_1") (pintype "passive"))
      (node (ref "U20") (pin "3") (pinfunction "IN+_3") (pintype "passive"))
    )
    (net (code "159") (name "Net-(U21-DQ3{slash}~{HOLD})") (class "Default")
      (node (ref "R50") (pin "1") (pinfunction "1_1") (pintype "passive"))
      (node (ref "U21") (pin "1") (pinfunction "DQ3/~{HOLD}_1") (pintype "passive"))
    )
    (net (code "160") (name "Net-(U21-~{RESET})") (class "Default")
      (node (ref "R48") (pin "1") (pinfunction "1_1") (pintype "passive"))
      (node (ref "U21") (pin "3") (pinfunction "~{RESET}_3") (pintype "passive"))
    )
    (net (code "161") (name "Net-(U21-~{W}{slash}DQ2)") (class "Default")
      (node (ref "R49") (pin "1") (pinfunction "1_1") (pintype "passive"))
      (node (ref "U21") (pin "9") (pinfunction "~{W}/DQ2_9") (pintype "passive"))
    )
    (net (code "162") (name "Net-(U22-DQ3{slash}~{HOLD})") (class "Default")
      (node (ref "R58") (pin "1") (pinfunction "1_1") (pintype "passive"))
      (node (ref "U22") (pin "1") (pinfunction "DQ3/~{HOLD}_1") (pintype "passive"))
    )
    (net (code "163") (name "Net-(U22-~{RESET})") (class "Default")
      (node (ref "R56") (pin "1") (pinfunction "1_1") (pintype "passive"))
      (node (ref "U22") (pin "3") (pinfunction "~{RESET}_3") (pintype "passive"))
    )
    (net (code "164") (name "Net-(U22-~{W}{slash}DQ2)") (class "Default")
      (node (ref "R57") (pin "1") (pinfunction "1_1") (pintype "passive"))
      (node (ref "U22") (pin "9") (pinfunction "~{W}/DQ2_9") (pintype "passive"))
    )
    (net (code "165") (name "Net-(U23-DQ3{slash}~{HOLD})") (class "Default")
      (node (ref "R62") (pin "1") (pinfunction "1_1") (pintype "passive"))
      (node (ref "U23") (pin "1") (pinfunction "DQ3/~{HOLD}_1") (pintype "passive"))
    )
    (net (code "166") (name "Net-(U23-~{RESET})") (class "Default")
      (node (ref "R60") (pin "1") (pinfunction "1_1") (pintype "passive"))
      (node (ref "U23") (pin "3") (pinfunction "~{RESET}_3") (pintype "passive"))
    )
    (net (code "167") (name "Net-(U23-~{W}{slash}DQ2)") (class "Default")
      (node (ref "R61") (pin "1") (pinfunction "1_1") (pintype "passive"))
      (node (ref "U23") (pin "9") (pinfunction "~{W}/DQ2_9") (pintype "passive"))
    )
    (net (code "168") (name "Net-(U24-VDD)") (class "Default")
      (node (ref "C44") (pin "2") (pinfunction "2_2") (pintype "passive"))
      (node (ref "C45") (pin "1") (pinfunction "1_1") (pintype "passive"))
      (node (ref "R42") (pin "1") (pinfunction "1_1") (pintype "passive"))
      (node (ref "U24") (pin "2") (pinfunction "VDD_2") (pintype "passive"))
    )
    (net (code "169") (name "Net-(U25-DQ3{slash}~{HOLD})") (class "Default")
      (node (ref "R66") (pin "1") (pinfunction "1_1") (pintype "passive"))
      (node (ref "U25") (pin "1") (pinfunction "DQ3/~{HOLD}_1") (pintype "passive"))
    )
    (net (code "170") (name "Net-(U25-~{RESET})") (class "Default")
      (node (ref "R64") (pin "1") (pinfunction "1_1") (pintype "passive"))
      (node (ref "U25") (pin "3") (pinfunction "~{RESET}_3") (pintype "passive"))
    )
    (net (code "171") (name "Net-(U25-~{W}{slash}DQ2)") (class "Default")
      (node (ref "R65") (pin "1") (pinfunction "1_1") (pintype "passive"))
      (node (ref "U25") (pin "9") (pinfunction "~{W}/DQ2_9") (pintype "passive"))
    )
    (net (code "172") (name "Net-(U26A-VINA+)") (class "Default")
      (node (ref "R69") (pin "1") (pinfunction "1_1") (pintype "passive"))
      (node (ref "R70") (pin "2") (pinfunction "2_2") (pintype "passive"))
      (node (ref "U26") (pin "3") (pinfunction "VINA+_3") (pintype "input"))
    )
    (net (code "173") (name "Net-(U26A-VINA-)") (class "Default")
      (node (ref "R68") (pin "2") (pinfunction "2_2") (pintype "passive"))
      (node (ref "U26") (pin "1") (pinfunction "VOUTA_1") (pintype "output"))
      (node (ref "U26") (pin "2") (pinfunction "VINA-_2") (pintype "input"))
    )
    (net (code "174") (name "Net-(U26B-VINB+)") (class "Default")
      (node (ref "R72") (pin "1") (pinfunction "1_1") (pintype "passive"))
      (node (ref "R74") (pin "2") (pinfunction "2_2") (pintype "passive"))
      (node (ref "U26") (pin "5") (pinfunction "VINB+_5") (pintype "input"))
    )
    (net (code "175") (name "Net-(U26B-VINB-)") (class "Default")
      (node (ref "R71") (pin "2") (pinfunction "2_2") (pintype "passive"))
      (node (ref "U26") (pin "6") (pinfunction "VINB-_6") (pintype "input"))
      (node (ref "U26") (pin "7") (pinfunction "VOUTB_7") (pintype "output"))
    )
    (net (code "176") (name "Net-(U27-VCC)") (class "Default")
      (node (ref "C65") (pin "2") (pinfunction "2_2") (pintype "passive"))
      (node (ref "C69") (pin "1") (pinfunction "1_1") (pintype "passive"))
      (node (ref "R91") (pin "1") (pinfunction "1_1") (pintype "passive"))
      (node (ref "U27") (pin "5") (pinfunction "VCC_5") (pintype "power_in"))
    )
    (net (code "177") (name "Net-(U28-DQ3{slash}~{HOLD})") (class "Default")
      (node (ref "R78") (pin "1") (pinfunction "1_1") (pintype "passive"))
      (node (ref "U28") (pin "1") (pinfunction "DQ3/~{HOLD}_1") (pintype "passive"))
    )
    (net (code "178") (name "Net-(U28-~{RESET})") (class "Default")
      (node (ref "R76") (pin "1") (pinfunction "1_1") (pintype "passive"))
      (node (ref "U28") (pin "3") (pinfunction "~{RESET}_3") (pintype "passive"))
    )
    (net (code "179") (name "Net-(U28-~{W}{slash}DQ2)") (class "Default")
      (node (ref "R77") (pin "1") (pinfunction "1_1") (pintype "passive"))
      (node (ref "U28") (pin "9") (pinfunction "~{W}/DQ2_9") (pintype "passive"))
    )
    (net (code "180") (name "Net-(U29-DQ3{slash}~{HOLD})") (class "Default")
      (node (ref "R82") (pin "1") (pinfunction "1_1") (pintype "passive"))
      (node (ref "U29") (pin "1") (pinfunction "DQ3/~{HOLD}_1") (pintype "passive"))
    )
    (net (code "181") (name "Net-(U29-~{RESET})") (class "Default")
      (node (ref "R80") (pin "1") (pinfunction "1_1") (pintype "passive"))
      (node (ref "U29") (pin "3") (pinfunction "~{RESET}_3") (pintype "passive"))
    )
    (net (code "182") (name "Net-(U29-~{W}{slash}DQ2)") (class "Default")
      (node (ref "R81") (pin "1") (pinfunction "1_1") (pintype "passive"))
      (node (ref "U29") (pin "9") (pinfunction "~{W}/DQ2_9") (pintype "passive"))
    )
    (net (code "183") (name "Net-(U30-DQ3{slash}~{HOLD})") (class "Default")
      (node (ref "R86") (pin "1") (pinfunction "1_1") (pintype "passive"))
      (node (ref "U30") (pin "1") (pinfunction "DQ3/~{HOLD}_1") (pintype "passive"))
    )
    (net (code "184") (name "Net-(U30-~{RESET})") (class "Default")
      (node (ref "R84") (pin "1") (pinfunction "1_1") (pintype "passive"))
      (node (ref "U30") (pin "3") (pinfunction "~{RESET}_3") (pintype "passive"))
    )
    (net (code "185") (name "Net-(U30-~{W}{slash}DQ2)") (class "Default")
      (node (ref "R85") (pin "1") (pinfunction "1_1") (pintype "passive"))
      (node (ref "U30") (pin "9") (pinfunction "~{W}/DQ2_9") (pintype "passive"))
    )
    (net (code "186") (name "Net-(U31-DQ3{slash}~{HOLD})") (class "Default")
      (node (ref "R90") (pin "1") (pinfunction "1_1") (pintype "passive"))
      (node (ref "U31") (pin "1") (pinfunction "DQ3/~{HOLD}_1") (pintype "passive"))
    )
    (net (code "187") (name "Net-(U31-~{RESET})") (class "Default")
      (node (ref "R88") (pin "1") (pinfunction "1_1") (pintype "passive"))
      (node (ref "U31") (pin "3") (pinfunction "~{RESET}_3") (pintype "passive"))
    )
    (net (code "188") (name "Net-(U31-~{W}{slash}DQ2)") (class "Default")
      (node (ref "R89") (pin "1") (pinfunction "1_1") (pintype "passive"))
      (node (ref "U31") (pin "9") (pinfunction "~{W}/DQ2_9") (pintype "passive"))
    )
    (net (code "189") (name "Net-(U33-DIN)") (class "Default")
      (node (ref "R52") (pin "2") (pinfunction "2_2") (pintype "passive"))
      (node (ref "U33") (pin "2") (pinfunction "DIN_2") (pintype "passive"))
    )
    (net (code "190") (name "Net-(U33-DOUT)") (class "Default")
      (node (ref "R51") (pin "2") (pinfunction "2_2") (pintype "passive"))
      (node (ref "U33") (pin "18") (pinfunction "DOUT_18") (pintype "passive"))
    )
    (net (code "191") (name "Net-(U33-SCLK)") (class "Default")
      (node (ref "R53") (pin "2") (pinfunction "2_2") (pintype "passive"))
      (node (ref "U33") (pin "1") (pinfunction "SCLK_1") (pintype "passive"))
    )
    (net (code "192") (name "Net-(U33-VIN0)") (class "Default")
      (node (ref "C62") (pin "2") (pinfunction "2_2") (pintype "passive"))
      (node (ref "R38") (pin "1") (pinfunction "1_1") (pintype "passive"))
      (node (ref "U33") (pin "16") (pinfunction "VIN0_16") (pintype "passive"))
    )
    (net (code "193") (name "Net-(U33-VIN1)") (class "Default")
      (node (ref "C67") (pin "2") (pinfunction "2_2") (pintype "passive"))
      (node (ref "R43") (pin "1") (pinfunction "1_1") (pintype "passive"))
      (node (ref "U33") (pin "15") (pinfunction "VIN1_15") (pintype "passive"))
    )
    (net (code "194") (name "Net-(U33-VIN2)") (class "Default")
      (node (ref "C77") (pin "2") (pinfunction "2_2") (pintype "passive"))
      (node (ref "R68") (pin "1") (pinfunction "1_1") (pintype "passive"))
      (node (ref "U33") (pin "14") (pinfunction "VIN2_14") (pintype "passive"))
    )
    (net (code "195") (name "Net-(U33-VIN3)") (class "Default")
      (node (ref "C83") (pin "2") (pinfunction "2_2") (pintype "passive"))
      (node (ref "R71") (pin "1") (pinfunction "1_1") (pintype "passive"))
      (node (ref "U33") (pin "13") (pinfunction "VIN3_13") (pintype "passive"))
    )
    (net (code "196") (name "Net-(U33-VIN4)") (class "Default")
      (node (ref "C93") (pin "2") (pinfunction "2_2") (pintype "passive"))
      (node (ref "R93") (pin "1") (pinfunction "1_1") (pintype "passive"))
      (node (ref "U33") (pin "12") (pinfunction "VIN4_12") (pintype "passive"))
    )
    (net (code "197") (name "Net-(U33-VIN5)") (class "Default")
      (node (ref "C117") (pin "2") (pinfunction "2_2") (pintype "passive"))
      (node (ref "R103") (pin "1") (pinfunction "1_1") (pintype "passive"))
      (node (ref "U33") (pin "11") (pinfunction "VIN5_11") (pintype "passive"))
    )
    (net (code "198") (name "Net-(U33-~{CS})") (class "Default")
      (node (ref "R46") (pin "2") (pinfunction "2_2") (pintype "passive"))
      (node (ref "R54") (pin "2") (pinfunction "2_2") (pintype "passive"))
      (node (ref "U33") (pin "3") (pinfunction "~{CS}_3") (pintype "passive"))
    )
    (net (code "199") (name "Net-(U34-DQ3{slash}~{HOLD})") (class "Default")
      (node (ref "R109") (pin "1") (pinfunction "1_1") (pintype "passive"))
      (node (ref "U34") (pin "1") (pinfunction "DQ3/~{HOLD}_1") (pintype "passive"))
    )
    (net (code "200") (name "Net-(U34-~{RESET})") (class "Default")
      (node (ref "R107") (pin "1") (pinfunction "1_1") (pintype "passive"))
      (node (ref "U34") (pin "3") (pinfunction "~{RESET}_3") (pintype "passive"))
    )
    (net (code "201") (name "Net-(U34-~{W}{slash}DQ2)") (class "Default")
      (node (ref "R108") (pin "1") (pinfunction "1_1") (pintype "passive"))
      (node (ref "U34") (pin "9") (pinfunction "~{W}/DQ2_9") (pintype "passive"))
    )
    (net (code "202") (name "Net-(U35-DQ3{slash}~{HOLD})") (class "Default")
      (node (ref "R113") (pin "1") (pinfunction "1_1") (pintype "passive"))
      (node (ref "U35") (pin "1") (pinfunction "DQ3/~{HOLD}_1") (pintype "passive"))
    )
    (net (code "203") (name "Net-(U35-~{RESET})") (class "Default")
      (node (ref "R111") (pin "1") (pinfunction "1_1") (pintype "passive"))
      (node (ref "U35") (pin "3") (pinfunction "~{RESET}_3") (pintype "passive"))
    )
    (net (code "204") (name "Net-(U35-~{W}{slash}DQ2)") (class "Default")
      (node (ref "R112") (pin "1") (pinfunction "1_1") (pintype "passive"))
      (node (ref "U35") (pin "9") (pinfunction "~{W}/DQ2_9") (pintype "passive"))
    )
    (net (code "205") (name "Net-(U36-DQ3{slash}~{HOLD})") (class "Default")
      (node (ref "R117") (pin "1") (pinfunction "1_1") (pintype "passive"))
      (node (ref "U36") (pin "1") (pinfunction "DQ3/~{HOLD}_1") (pintype "passive"))
    )
    (net (code "206") (name "Net-(U36-~{RESET})") (class "Default")
      (node (ref "R115") (pin "1") (pinfunction "1_1") (pintype "passive"))
      (node (ref "U36") (pin "3") (pinfunction "~{RESET}_3") (pintype "passive"))
    )
    (net (code "207") (name "Net-(U36-~{W}{slash}DQ2)") (class "Default")
      (node (ref "R116") (pin "1") (pinfunction "1_1") (pintype "passive"))
      (node (ref "U36") (pin "9") (pinfunction "~{W}/DQ2_9") (pintype "passive"))
    )
    (net (code "208") (name "Net-(U37-DQ3{slash}~{HOLD})") (class "Default")
      (node (ref "R121") (pin "1") (pinfunction "1_1") (pintype "passive"))
      (node (ref "U37") (pin "1") (pinfunction "DQ3/~{HOLD}_1") (pintype "passive"))
    )
    (net (code "209") (name "Net-(U37-~{RESET})") (class "Default")
      (node (ref "R119") (pin "1") (pinfunction "1_1") (pintype "passive"))
      (node (ref "U37") (pin "3") (pinfunction "~{RESET}_3") (pintype "passive"))
    )
    (net (code "210") (name "Net-(U37-~{W}{slash}DQ2)") (class "Default")
      (node (ref "R120") (pin "1") (pinfunction "1_1") (pintype "passive"))
      (node (ref "U37") (pin "9") (pinfunction "~{W}/DQ2_9") (pintype "passive"))
    )
    (net (code "211") (name "Net-(U40-DQ3{slash}~{HOLD})") (class "Default")
      (node (ref "R126") (pin "1") (pinfunction "1_1") (pintype "passive"))
      (node (ref "U40") (pin "1") (pinfunction "DQ3/~{HOLD}_1") (pintype "passive"))
    )
    (net (code "212") (name "Net-(U40-~{RESET})") (class "Default")
      (node (ref "R124") (pin "1") (pinfunction "1_1") (pintype "passive"))
      (node (ref "U40") (pin "3") (pinfunction "~{RESET}_3") (pintype "passive"))
    )
    (net (code "213") (name "Net-(U40-~{W}{slash}DQ2)") (class "Default")
      (node (ref "R125") (pin "1") (pinfunction "1_1") (pintype "passive"))
      (node (ref "U40") (pin "9") (pinfunction "~{W}/DQ2_9") (pintype "passive"))
    )
    (net (code "214") (name "Net-(U41-DQ3{slash}~{HOLD})") (class "Default")
      (node (ref "R130") (pin "1") (pinfunction "1_1") (pintype "passive"))
      (node (ref "U41") (pin "1") (pinfunction "DQ3/~{HOLD}_1") (pintype "passive"))
    )
    (net (code "215") (name "Net-(U41-~{RESET})") (class "Default")
      (node (ref "R128") (pin "1") (pinfunction "1_1") (pintype "passive"))
      (node (ref "U41") (pin "3") (pinfunction "~{RESET}_3") (pintype "passive"))
    )
    (net (code "216") (name "Net-(U41-~{W}{slash}DQ2)") (class "Default")
      (node (ref "R129") (pin "1") (pinfunction "1_1") (pintype "passive"))
      (node (ref "U41") (pin "9") (pinfunction "~{W}/DQ2_9") (pintype "passive"))
    )
    (net (code "217") (name "Net-(U42-DQ3{slash}~{HOLD})") (class "Default")
      (node (ref "R134") (pin "1") (pinfunction "1_1") (pintype "passive"))
      (node (ref "U42") (pin "1") (pinfunction "DQ3/~{HOLD}_1") (pintype "passive"))
    )
    (net (code "218") (name "Net-(U42-~{RESET})") (class "Default")
      (node (ref "R132") (pin "1") (pinfunction "1_1") (pintype "passive"))
      (node (ref "U42") (pin "3") (pinfunction "~{RESET}_3") (pintype "passive"))
    )
    (net (code "219") (name "Net-(U42-~{W}{slash}DQ2)") (class "Default")
      (node (ref "R133") (pin "1") (pinfunction "1_1") (pintype "passive"))
      (node (ref "U42") (pin "9") (pinfunction "~{W}/DQ2_9") (pintype "passive"))
    )
    (net (code "220") (name "Net-(U43-DQ3{slash}~{HOLD})") (class "Default")
      (node (ref "R138") (pin "1") (pinfunction "1_1") (pintype "passive"))
      (node (ref "U43") (pin "1") (pinfunction "DQ3/~{HOLD}_1") (pintype "passive"))
    )
    (net (code "221") (name "Net-(U43-~{RESET})") (class "Default")
      (node (ref "R136") (pin "1") (pinfunction "1_1") (pintype "passive"))
      (node (ref "U43") (pin "3") (pinfunction "~{RESET}_3") (pintype "passive"))
    )
    (net (code "222") (name "Net-(U43-~{W}{slash}DQ2)") (class "Default")
      (node (ref "R137") (pin "1") (pinfunction "1_1") (pintype "passive"))
      (node (ref "U43") (pin "9") (pinfunction "~{W}/DQ2_9") (pintype "passive"))
    )
    (net (code "223") (name "Net-(U44-PGC2{slash}OA2IN+{slash}RP36{slash}RB4)") (class "Default")
      (node (ref "R190") (pin "1") (pinfunction "1_1") (pintype "passive"))
      (node (ref "U44") (pin "27") (pinfunction "PGC2/OA2IN+/RP36/RB4_27") (pintype "passive"))
    )
    (net (code "224") (name "Net-(U44-PGD2{slash}OA2IN-{slash}AN8{slash}CMP4A{slash}RP35{slash}RB3)") (class "Default")
      (node (ref "R189") (pin "1") (pinfunction "1_1") (pintype "passive"))
      (node (ref "U44") (pin "26") (pinfunction "PGD2/OA2IN-/AN8/CMP4A/RP35/RB3_26") (pintype "passive"))
    )
    (net (code "225") (name "Net-(U45-DQ3{slash}~{HOLD})") (class "Default")
      (node (ref "R145") (pin "1") (pinfunction "1_1") (pintype "passive"))
      (node (ref "U45") (pin "1") (pinfunction "DQ3/~{HOLD}_1") (pintype "passive"))
    )
    (net (code "226") (name "Net-(U45-~{RESET})") (class "Default")
      (node (ref "R143") (pin "1") (pinfunction "1_1") (pintype "passive"))
      (node (ref "U45") (pin "3") (pinfunction "~{RESET}_3") (pintype "passive"))
    )
    (net (code "227") (name "Net-(U45-~{W}{slash}DQ2)") (class "Default")
      (node (ref "R144") (pin "1") (pinfunction "1_1") (pintype "passive"))
      (node (ref "U45") (pin "9") (pinfunction "~{W}/DQ2_9") (pintype "passive"))
    )
    (net (code "228") (name "Net-(U46-DQ3{slash}~{HOLD})") (class "Default")
      (node (ref "R149") (pin "1") (pinfunction "1_1") (pintype "passive"))
      (node (ref "U46") (pin "1") (pinfunction "DQ3/~{HOLD}_1") (pintype "passive"))
    )
    (net (code "229") (name "Net-(U46-~{RESET})") (class "Default")
      (node (ref "R147") (pin "1") (pinfunction "1_1") (pintype "passive"))
      (node (ref "U46") (pin "3") (pinfunction "~{RESET}_3") (pintype "passive"))
    )
    (net (code "230") (name "Net-(U46-~{W}{slash}DQ2)") (class "Default")
      (node (ref "R148") (pin "1") (pinfunction "1_1") (pintype "passive"))
      (node (ref "U46") (pin "9") (pinfunction "~{W}/DQ2_9") (pintype "passive"))
    )
    (net (code "231") (name "Net-(U47-DQ3{slash}~{HOLD})") (class "Default")
      (node (ref "R152") (pin "1") (pinfunction "1_1") (pintype "passive"))
      (node (ref "U47") (pin "1") (pinfunction "DQ3/~{HOLD}_1") (pintype "passive"))
    )
    (net (code "232") (name "Net-(U47-~{RESET})") (class "Default")
      (node (ref "R150") (pin "1") (pinfunction "1_1") (pintype "passive"))
      (node (ref "U47") (pin "3") (pinfunction "~{RESET}_3") (pintype "passive"))
    )
    (net (code "233") (name "Net-(U47-~{W}{slash}DQ2)") (class "Default")
      (node (ref "R151") (pin "1") (pinfunction "1_1") (pintype "passive"))
      (node (ref "U47") (pin "9") (pinfunction "~{W}/DQ2_9") (pintype "passive"))
    )
    (net (code "234") (name "Net-(U48-DQ3{slash}~{HOLD})") (class "Default")
      (node (ref "R158") (pin "1") (pinfunction "1_1") (pintype "passive"))
      (node (ref "U48") (pin "1") (pinfunction "DQ3/~{HOLD}_1") (pintype "passive"))
    )
    (net (code "235") (name "Net-(U48-~{RESET})") (class "Default")
      (node (ref "R156") (pin "1") (pinfunction "1_1") (pintype "passive"))
      (node (ref "U48") (pin "3") (pinfunction "~{RESET}_3") (pintype "passive"))
    )
    (net (code "236") (name "Net-(U48-~{W}{slash}DQ2)") (class "Default")
      (node (ref "R157") (pin "1") (pinfunction "1_1") (pintype "passive"))
      (node (ref "U48") (pin "9") (pinfunction "~{W}/DQ2_9") (pintype "passive"))
    )
    (net (code "237") (name "Net-(U50A-VINA+)") (class "Default")
      (node (ref "R94") (pin "1") (pinfunction "1_1") (pintype "passive"))
      (node (ref "R95") (pin "2") (pinfunction "2_2") (pintype "passive"))
      (node (ref "U50") (pin "3") (pinfunction "VINA+_3") (pintype "input"))
    )
    (net (code "238") (name "Net-(U50A-VINA-)") (class "Default")
      (node (ref "R93") (pin "2") (pinfunction "2_2") (pintype "passive"))
      (node (ref "U50") (pin "1") (pinfunction "VOUTA_1") (pintype "output"))
      (node (ref "U50") (pin "2") (pinfunction "VINA-_2") (pintype "input"))
    )
    (net (code "239") (name "Net-(U50B-VINB+)") (class "Default")
      (node (ref "R105") (pin "1") (pinfunction "1_1") (pintype "passive"))
      (node (ref "R164") (pin "2") (pinfunction "2_2") (pintype "passive"))
      (node (ref "U50") (pin "5") (pinfunction "VINB+_5") (pintype "input"))
    )
    (net (code "240") (name "Net-(U50B-VINB-)") (class "Default")
      (node (ref "R103") (pin "2") (pinfunction "2_2") (pintype "passive"))
      (node (ref "U50") (pin "6") (pinfunction "VINB-_6") (pintype "input"))
      (node (ref "U50") (pin "7") (pinfunction "VOUTB_7") (pintype "output"))
    )
    (net (code "241") (name "Net-(Y1-OUT)") (class "Default")
      (node (ref "R140") (pin "2") (pinfunction "2_2") (pintype "passive"))
      (node (ref "Y1") (pin "3") (pinfunction "OUT_3") (pintype "passive"))
    )
    (net (code "242") (name "unconnected-(U3-NC-Pad1)") (class "Default")
      (node (ref "U3") (pin "1") (pinfunction "NC_1") (pintype "power_in"))
    )
    (net (code "243") (name "unconnected-(U5-STAT-Pad4)") (class "Default")
      (node (ref "U5") (pin "4") (pinfunction "STAT_4") (pintype "open_collector"))
    )
    (net (code "244") (name "unconnected-(U6-NC-Pad15)") (class "Default")
      (node (ref "U6") (pin "15") (pinfunction "NC_15") (pintype "passive"))
    )
    (net (code "245") (name "unconnected-(U6-PGOOD1-Pad3)") (class "Default")
      (node (ref "U6") (pin "3") (pinfunction "PGOOD1_3") (pintype "passive"))
    )
    (net (code "246") (name "unconnected-(U6-PGOOD2-Pad6)") (class "Default")
      (node (ref "U6") (pin "6") (pinfunction "PGOOD2_6") (pintype "passive"))
    )
    (net (code "247") (name "unconnected-(U7-NC-Pad1)") (class "Default")
      (node (ref "U7") (pin "1") (pinfunction "NC_1") (pintype "power_in"))
    )
    (net (code "248") (name "unconnected-(U8-STAT-Pad4)") (class "Default")
      (node (ref "U8") (pin "4") (pinfunction "STAT_4") (pintype "open_collector"))
    )
    (net (code "249") (name "unconnected-(U9-NC-Pad2)") (class "Default")
      (node (ref "U9") (pin "2") (pinfunction "NC_2") (pintype "passive"))
    )
    (net (code "250") (name "unconnected-(U9-NC-Pad3)") (class "Default")
      (node (ref "U9") (pin "3") (pinfunction "NC_3") (pintype "passive"))
    )
    (net (code "251") (name "unconnected-(U9-NC-Pad6)") (class "Default")
      (node (ref "U9") (pin "6") (pinfunction "NC_6") (pintype "passive"))
    )
    (net (code "252") (name "unconnected-(U9-NC-Pad7)") (class "Default")
      (node (ref "U9") (pin "7") (pinfunction "NC_7") (pintype "passive"))
    )
    (net (code "253") (name "unconnected-(U11-STAT-Pad4)") (class "Default")
      (node (ref "U11") (pin "4") (pinfunction "STAT_4") (pintype "open_collector"))
    )
    (net (code "254") (name "unconnected-(U12-STAT-Pad4)") (class "Default")
      (node (ref "U12") (pin "4") (pinfunction "STAT_4") (pintype "open_collector"))
    )
    (net (code "255") (name "unconnected-(U13-INT2-Pad4)") (class "Default")
      (node (ref "U13") (pin "4") (pinfunction "INT2_4") (pintype "passive"))
    )
    (net (code "256") (name "unconnected-(U14-INT-Pad5)") (class "Default")
      (node (ref "U14") (pin "5") (pinfunction "INT_5") (pintype "passive"))
    )
    (net (code "257") (name "unconnected-(U15-DNU_1-Pad4)") (class "Default")
      (node (ref "U15") (pin "4") (pinfunction "DNU_1_4") (pintype "passive"))
    )
    (net (code "258") (name "unconnected-(U15-DNU_2-Pad5)") (class "Default")
      (node (ref "U15") (pin "5") (pinfunction "DNU_2_5") (pintype "passive"))
    )
    (net (code "259") (name "unconnected-(U15-DNU_3-Pad6)") (class "Default")
      (node (ref "U15") (pin "6") (pinfunction "DNU_3_6") (pintype "passive"))
    )
    (net (code "260") (name "unconnected-(U15-DNU_4-Pad11)") (class "Default")
      (node (ref "U15") (pin "11") (pinfunction "DNU_4_11") (pintype "passive"))
    )
    (net (code "261") (name "unconnected-(U15-DNU_5-Pad12)") (class "Default")
      (node (ref "U15") (pin "12") (pinfunction "DNU_5_12") (pintype "passive"))
    )
    (net (code "262") (name "unconnected-(U15-DNU_6-Pad13)") (class "Default")
      (node (ref "U15") (pin "13") (pinfunction "DNU_6_13") (pintype "passive"))
    )
    (net (code "263") (name "unconnected-(U15-DNU_7-Pad14)") (class "Default")
      (node (ref "U15") (pin "14") (pinfunction "DNU_7_14") (pintype "passive"))
    )
    (net (code "264") (name "unconnected-(U16B-VDD-Pad8)") (class "Default")
      (node (ref "U16") (pin "8") (pinfunction "VDD_8") (pintype "power_in"))
    )
    (net (code "265") (name "unconnected-(U16B-VSS-Pad4)") (class "Default")
      (node (ref "U16") (pin "4") (pinfunction "VSS_4") (pintype "power_in"))
    )
    (net (code "266") (name "unconnected-(U17-DNU_1-Pad4)") (class "Default")
      (node (ref "U17") (pin "4") (pinfunction "DNU_1_4") (pintype "passive"))
    )
    (net (code "267") (name "unconnected-(U17-DNU_2-Pad5)") (class "Default")
      (node (ref "U17") (pin "5") (pinfunction "DNU_2_5") (pintype "passive"))
    )
    (net (code "268") (name "unconnected-(U17-DNU_3-Pad6)") (class "Default")
      (node (ref "U17") (pin "6") (pinfunction "DNU_3_6") (pintype "passive"))
    )
    (net (code "269") (name "unconnected-(U17-DNU_4-Pad11)") (class "Default")
      (node (ref "U17") (pin "11") (pinfunction "DNU_4_11") (pintype "passive"))
    )
    (net (code "270") (name "unconnected-(U17-DNU_5-Pad12)") (class "Default")
      (node (ref "U17") (pin "12") (pinfunction "DNU_5_12") (pintype "passive"))
    )
    (net (code "271") (name "unconnected-(U17-DNU_6-Pad13)") (class "Default")
      (node (ref "U17") (pin "13") (pinfunction "DNU_6_13") (pintype "passive"))
    )
    (net (code "272") (name "unconnected-(U17-DNU_7-Pad14)") (class "Default")
      (node (ref "U17") (pin "14") (pinfunction "DNU_7_14") (pintype "passive"))
    )
    (net (code "273") (name "unconnected-(U18-DNU_1-Pad4)") (class "Default")
      (node (ref "U18") (pin "4") (pinfunction "DNU_1_4") (pintype "passive"))
    )
    (net (code "274") (name "unconnected-(U18-DNU_2-Pad5)") (class "Default")
      (node (ref "U18") (pin "5") (pinfunction "DNU_2_5") (pintype "passive"))
    )
    (net (code "275") (name "unconnected-(U18-DNU_3-Pad6)") (class "Default")
      (node (ref "U18") (pin "6") (pinfunction "DNU_3_6") (pintype "passive"))
    )
    (net (code "276") (name "unconnected-(U18-DNU_4-Pad11)") (class "Default")
      (node (ref "U18") (pin "11") (pinfunction "DNU_4_11") (pintype "passive"))
    )
    (net (code "277") (name "unconnected-(U18-DNU_5-Pad12)") (class "Default")
      (node (ref "U18") (pin "12") (pinfunction "DNU_5_12") (pintype "passive"))
    )
    (net (code "278") (name "unconnected-(U18-DNU_6-Pad13)") (class "Default")
      (node (ref "U18") (pin "13") (pinfunction "DNU_6_13") (pintype "passive"))
    )
    (net (code "279") (name "unconnected-(U18-DNU_7-Pad14)") (class "Default")
      (node (ref "U18") (pin "14") (pinfunction "DNU_7_14") (pintype "passive"))
    )
    (net (code "280") (name "unconnected-(U19-DNU_1-Pad4)") (class "Default")
      (node (ref "U19") (pin "4") (pinfunction "DNU_1_4") (pintype "passive"))
    )
    (net (code "281") (name "unconnected-(U19-DNU_2-Pad5)") (class "Default")
      (node (ref "U19") (pin "5") (pinfunction "DNU_2_5") (pintype "passive"))
    )
    (net (code "282") (name "unconnected-(U19-DNU_3-Pad6)") (class "Default")
      (node (ref "U19") (pin "6") (pinfunction "DNU_3_6") (pintype "passive"))
    )
    (net (code "283") (name "unconnected-(U19-DNU_4-Pad11)") (class "Default")
      (node (ref "U19") (pin "11") (pinfunction "DNU_4_11") (pintype "passive"))
    )
    (net (code "284") (name "unconnected-(U19-DNU_5-Pad12)") (class "Default")
      (node (ref "U19") (pin "12") (pinfunction "DNU_5_12") (pintype "passive"))
    )
    (net (code "285") (name "unconnected-(U19-DNU_6-Pad13)") (class "Default")
      (node (ref "U19") (pin "13") (pinfunction "DNU_6_13") (pintype "passive"))
    )
    (net (code "286") (name "unconnected-(U19-DNU_7-Pad14)") (class "Default")
      (node (ref "U19") (pin "14") (pinfunction "DNU_7_14") (pintype "passive"))
    )
    (net (code "287") (name "unconnected-(U21-DNU_1-Pad4)") (class "Default")
      (node (ref "U21") (pin "4") (pinfunction "DNU_1_4") (pintype "passive"))
    )
    (net (code "288") (name "unconnected-(U21-DNU_2-Pad5)") (class "Default")
      (node (ref "U21") (pin "5") (pinfunction "DNU_2_5") (pintype "passive"))
    )
    (net (code "289") (name "unconnected-(U21-DNU_3-Pad6)") (class "Default")
      (node (ref "U21") (pin "6") (pinfunction "DNU_3_6") (pintype "passive"))
    )
    (net (code "290") (name "unconnected-(U21-DNU_4-Pad11)") (class "Default")
      (node (ref "U21") (pin "11") (pinfunction "DNU_4_11") (pintype "passive"))
    )
    (net (code "291") (name "unconnected-(U21-DNU_5-Pad12)") (class "Default")
      (node (ref "U21") (pin "12") (pinfunction "DNU_5_12") (pintype "passive"))
    )
    (net (code "292") (name "unconnected-(U21-DNU_6-Pad13)") (class "Default")
      (node (ref "U21") (pin "13") (pinfunction "DNU_6_13") (pintype "passive"))
    )
    (net (code "293") (name "unconnected-(U21-DNU_7-Pad14)") (class "Default")
      (node (ref "U21") (pin "14") (pinfunction "DNU_7_14") (pintype "passive"))
    )
    (net (code "294") (name "unconnected-(U22-DNU_1-Pad4)") (class "Default")
      (node (ref "U22") (pin "4") (pinfunction "DNU_1_4") (pintype "passive"))
    )
    (net (code "295") (name "unconnected-(U22-DNU_2-Pad5)") (class "Default")
      (node (ref "U22") (pin "5") (pinfunction "DNU_2_5") (pintype "passive"))
    )
    (net (code "296") (name "unconnected-(U22-DNU_3-Pad6)") (class "Default")
      (node (ref "U22") (pin "6") (pinfunction "DNU_3_6") (pintype "passive"))
    )
    (net (code "297") (name "unconnected-(U22-DNU_4-Pad11)") (class "Default")
      (node (ref "U22") (pin "11") (pinfunction "DNU_4_11") (pintype "passive"))
    )
    (net (code "298") (name "unconnected-(U22-DNU_5-Pad12)") (class "Default")
      (node (ref "U22") (pin "12") (pinfunction "DNU_5_12") (pintype "passive"))
    )
    (net (code "299") (name "unconnected-(U22-DNU_6-Pad13)") (class "Default")
      (node (ref "U22") (pin "13") (pinfunction "DNU_6_13") (pintype "passive"))
    )
    (net (code "300") (name "unconnected-(U22-DNU_7-Pad14)") (class "Default")
      (node (ref "U22") (pin "14") (pinfunction "DNU_7_14") (pintype "passive"))
    )
    (net (code "301") (name "unconnected-(U23-DNU_1-Pad4)") (class "Default")
      (node (ref "U23") (pin "4") (pinfunction "DNU_1_4") (pintype "passive"))
    )
    (net (code "302") (name "unconnected-(U23-DNU_2-Pad5)") (class "Default")
      (node (ref "U23") (pin "5") (pinfunction "DNU_2_5") (pintype "passive"))
    )
    (net (code "303") (name "unconnected-(U23-DNU_3-Pad6)") (class "Default")
      (node (ref "U23") (pin "6") (pinfunction "DNU_3_6") (pintype "passive"))
    )
    (net (code "304") (name "unconnected-(U23-DNU_4-Pad11)") (class "Default")
      (node (ref "U23") (pin "11") (pinfunction "DNU_4_11") (pintype "passive"))
    )
    (net (code "305") (name "unconnected-(U23-DNU_5-Pad12)") (class "Default")
      (node (ref "U23") (pin "12") (pinfunction "DNU_5_12") (pintype "passive"))
    )
    (net (code "306") (name "unconnected-(U23-DNU_6-Pad13)") (class "Default")
      (node (ref "U23") (pin "13") (pinfunction "DNU_6_13") (pintype "passive"))
    )
    (net (code "307") (name "unconnected-(U23-DNU_7-Pad14)") (class "Default")
      (node (ref "U23") (pin "14") (pinfunction "DNU_7_14") (pintype "passive"))
    )
    (net (code "308") (name "unconnected-(U25-DNU_1-Pad4)") (class "Default")
      (node (ref "U25") (pin "4") (pinfunction "DNU_1_4") (pintype "passive"))
    )
    (net (code "309") (name "unconnected-(U25-DNU_2-Pad5)") (class "Default")
      (node (ref "U25") (pin "5") (pinfunction "DNU_2_5") (pintype "passive"))
    )
    (net (code "310") (name "unconnected-(U25-DNU_3-Pad6)") (class "Default")
      (node (ref "U25") (pin "6") (pinfunction "DNU_3_6") (pintype "passive"))
    )
    (net (code "311") (name "unconnected-(U25-DNU_4-Pad11)") (class "Default")
      (node (ref "U25") (pin "11") (pinfunction "DNU_4_11") (pintype "passive"))
    )
    (net (code "312") (name "unconnected-(U25-DNU_5-Pad12)") (class "Default")
      (node (ref "U25") (pin "12") (pinfunction "DNU_5_12") (pintype "passive"))
    )
    (net (code "313") (name "unconnected-(U25-DNU_6-Pad13)") (class "Default")
      (node (ref "U25") (pin "13") (pinfunction "DNU_6_13") (pintype "passive"))
    )
    (net (code "314") (name "unconnected-(U25-DNU_7-Pad14)") (class "Default")
      (node (ref "U25") (pin "14") (pinfunction "DNU_7_14") (pintype "passive"))
    )
    (net (code "315") (name "unconnected-(U26B-VDD-Pad8)") (class "Default")
      (node (ref "U26") (pin "8") (pinfunction "VDD_8") (pintype "power_in"))
    )
    (net (code "316") (name "unconnected-(U26B-VSS-Pad4)") (class "Default")
      (node (ref "U26") (pin "4") (pinfunction "VSS_4") (pintype "power_in"))
    )
    (net (code "317") (name "unconnected-(U28-DNU_1-Pad4)") (class "Default")
      (node (ref "U28") (pin "4") (pinfunction "DNU_1_4") (pintype "passive"))
    )
    (net (code "318") (name "unconnected-(U28-DNU_2-Pad5)") (class "Default")
      (node (ref "U28") (pin "5") (pinfunction "DNU_2_5") (pintype "passive"))
    )
    (net (code "319") (name "unconnected-(U28-DNU_3-Pad6)") (class "Default")
      (node (ref "U28") (pin "6") (pinfunction "DNU_3_6") (pintype "passive"))
    )
    (net (code "320") (name "unconnected-(U28-DNU_4-Pad11)") (class "Default")
      (node (ref "U28") (pin "11") (pinfunction "DNU_4_11") (pintype "passive"))
    )
    (net (code "321") (name "unconnected-(U28-DNU_5-Pad12)") (class "Default")
      (node (ref "U28") (pin "12") (pinfunction "DNU_5_12") (pintype "passive"))
    )
    (net (code "322") (name "unconnected-(U28-DNU_6-Pad13)") (class "Default")
      (node (ref "U28") (pin "13") (pinfunction "DNU_6_13") (pintype "passive"))
    )
    (net (code "323") (name "unconnected-(U28-DNU_7-Pad14)") (class "Default")
      (node (ref "U28") (pin "14") (pinfunction "DNU_7_14") (pintype "passive"))
    )
    (net (code "324") (name "unconnected-(U29-DNU_1-Pad4)") (class "Default")
      (node (ref "U29") (pin "4") (pinfunction "DNU_1_4") (pintype "passive"))
    )
    (net (code "325") (name "unconnected-(U29-DNU_2-Pad5)") (class "Default")
      (node (ref "U29") (pin "5") (pinfunction "DNU_2_5") (pintype "passive"))
    )
    (net (code "326") (name "unconnected-(U29-DNU_3-Pad6)") (class "Default")
      (node (ref "U29") (pin "6") (pinfunction "DNU_3_6") (pintype "passive"))
    )
    (net (code "327") (name "unconnected-(U29-DNU_4-Pad11)") (class "Default")
      (node (ref "U29") (pin "11") (pinfunction "DNU_4_11") (pintype "passive"))
    )
    (net (code "328") (name "unconnected-(U29-DNU_5-Pad12)") (class "Default")
      (node (ref "U29") (pin "12") (pinfunction "DNU_5_12") (pintype "passive"))
    )
    (net (code "329") (name "unconnected-(U29-DNU_6-Pad13)") (class "Default")
      (node (ref "U29") (pin "13") (pinfunction "DNU_6_13") (pintype "passive"))
    )
    (net (code "330") (name "unconnected-(U29-DNU_7-Pad14)") (class "Default")
      (node (ref "U29") (pin "14") (pinfunction "DNU_7_14") (pintype "passive"))
    )
    (net (code "331") (name "unconnected-(U30-DNU_1-Pad4)") (class "Default")
      (node (ref "U30") (pin "4") (pinfunction "DNU_1_4") (pintype "passive"))
    )
    (net (code "332") (name "unconnected-(U30-DNU_2-Pad5)") (class "Default")
      (node (ref "U30") (pin "5") (pinfunction "DNU_2_5") (pintype "passive"))
    )
    (net (code "333") (name "unconnected-(U30-DNU_3-Pad6)") (class "Default")
      (node (ref "U30") (pin "6") (pinfunction "DNU_3_6") (pintype "passive"))
    )
    (net (code "334") (name "unconnected-(U30-DNU_4-Pad11)") (class "Default")
      (node (ref "U30") (pin "11") (pinfunction "DNU_4_11") (pintype "passive"))
    )
    (net (code "335") (name "unconnected-(U30-DNU_5-Pad12)") (class "Default")
      (node (ref "U30") (pin "12") (pinfunction "DNU_5_12") (pintype "passive"))
    )
    (net (code "336") (name "unconnected-(U30-DNU_6-Pad13)") (class "Default")
      (node (ref "U30") (pin "13") (pinfunction "DNU_6_13") (pintype "passive"))
    )
    (net (code "337") (name "unconnected-(U30-DNU_7-Pad14)") (class "Default")
      (node (ref "U30") (pin "14") (pinfunction "DNU_7_14") (pintype "passive"))
    )
    (net (code "338") (name "unconnected-(U31-DNU_1-Pad4)") (class "Default")
      (node (ref "U31") (pin "4") (pinfunction "DNU_1_4") (pintype "passive"))
    )
    (net (code "339") (name "unconnected-(U31-DNU_2-Pad5)") (class "Default")
      (node (ref "U31") (pin "5") (pinfunction "DNU_2_5") (pintype "passive"))
    )
    (net (code "340") (name "unconnected-(U31-DNU_3-Pad6)") (class "Default")
      (node (ref "U31") (pin "6") (pinfunction "DNU_3_6") (pintype "passive"))
    )
    (net (code "341") (name "unconnected-(U31-DNU_4-Pad11)") (class "Default")
      (node (ref "U31") (pin "11") (pinfunction "DNU_4_11") (pintype "passive"))
    )
    (net (code "342") (name "unconnected-(U31-DNU_5-Pad12)") (class "Default")
      (node (ref "U31") (pin "12") (pinfunction "DNU_5_12") (pintype "passive"))
    )
    (net (code "343") (name "unconnected-(U31-DNU_6-Pad13)") (class "Default")
      (node (ref "U31") (pin "13") (pinfunction "DNU_6_13") (pintype "passive"))
    )
    (net (code "344") (name "unconnected-(U31-DNU_7-Pad14)") (class "Default")
      (node (ref "U31") (pin "14") (pinfunction "DNU_7_14") (pintype "passive"))
    )
    (net (code "345") (name "unconnected-(U32-NC_1-Pad1)") (class "Default")
      (node (ref "U32") (pin "1") (pinfunction "NC_1_1") (pintype "passive"))
    )
    (net (code "346") (name "unconnected-(U32-NC_2-Pad3)") (class "Default")
      (node (ref "U32") (pin "3") (pinfunction "NC_2_3") (pintype "passive"))
    )
    (net (code "347") (name "unconnected-(U32-NC_3-Pad5)") (class "Default")
      (node (ref "U32") (pin "5") (pinfunction "NC_3_5") (pintype "passive"))
    )
    (net (code "348") (name "unconnected-(U32-NC_4-Pad7)") (class "Default")
      (node (ref "U32") (pin "7") (pinfunction "NC_4_7") (pintype "passive"))
    )
    (net (code "349") (name "unconnected-(U32-NC_5-Pad8)") (class "Default")
      (node (ref "U32") (pin "8") (pinfunction "NC_5_8") (pintype "passive"))
    )
    (net (code "350") (name "unconnected-(U34-DNU_1-Pad4)") (class "Default")
      (node (ref "U34") (pin "4") (pinfunction "DNU_1_4") (pintype "passive"))
    )
    (net (code "351") (name "unconnected-(U34-DNU_2-Pad5)") (class "Default")
      (node (ref "U34") (pin "5") (pinfunction "DNU_2_5") (pintype "passive"))
    )
    (net (code "352") (name "unconnected-(U34-DNU_3-Pad6)") (class "Default")
      (node (ref "U34") (pin "6") (pinfunction "DNU_3_6") (pintype "passive"))
    )
    (net (code "353") (name "unconnected-(U34-DNU_4-Pad11)") (class "Default")
      (node (ref "U34") (pin "11") (pinfunction "DNU_4_11") (pintype "passive"))
    )
    (net (code "354") (name "unconnected-(U34-DNU_5-Pad12)") (class "Default")
      (node (ref "U34") (pin "12") (pinfunction "DNU_5_12") (pintype "passive"))
    )
    (net (code "355") (name "unconnected-(U34-DNU_6-Pad13)") (class "Default")
      (node (ref "U34") (pin "13") (pinfunction "DNU_6_13") (pintype "passive"))
    )
    (net (code "356") (name "unconnected-(U34-DNU_7-Pad14)") (class "Default")
      (node (ref "U34") (pin "14") (pinfunction "DNU_7_14") (pintype "passive"))
    )
    (net (code "357") (name "unconnected-(U35-DNU_1-Pad4)") (class "Default")
      (node (ref "U35") (pin "4") (pinfunction "DNU_1_4") (pintype "passive"))
    )
    (net (code "358") (name "unconnected-(U35-DNU_2-Pad5)") (class "Default")
      (node (ref "U35") (pin "5") (pinfunction "DNU_2_5") (pintype "passive"))
    )
    (net (code "359") (name "unconnected-(U35-DNU_3-Pad6)") (class "Default")
      (node (ref "U35") (pin "6") (pinfunction "DNU_3_6") (pintype "passive"))
    )
    (net (code "360") (name "unconnected-(U35-DNU_4-Pad11)") (class "Default")
      (node (ref "U35") (pin "11") (pinfunction "DNU_4_11") (pintype "passive"))
    )
    (net (code "361") (name "unconnected-(U35-DNU_5-Pad12)") (class "Default")
      (node (ref "U35") (pin "12") (pinfunction "DNU_5_12") (pintype "passive"))
    )
    (net (code "362") (name "unconnected-(U35-DNU_6-Pad13)") (class "Default")
      (node (ref "U35") (pin "13") (pinfunction "DNU_6_13") (pintype "passive"))
    )
    (net (code "363") (name "unconnected-(U35-DNU_7-Pad14)") (class "Default")
      (node (ref "U35") (pin "14") (pinfunction "DNU_7_14") (pintype "passive"))
    )
    (net (code "364") (name "unconnected-(U36-DNU_1-Pad4)") (class "Default")
      (node (ref "U36") (pin "4") (pinfunction "DNU_1_4") (pintype "passive"))
    )
    (net (code "365") (name "unconnected-(U36-DNU_2-Pad5)") (class "Default")
      (node (ref "U36") (pin "5") (pinfunction "DNU_2_5") (pintype "passive"))
    )
    (net (code "366") (name "unconnected-(U36-DNU_3-Pad6)") (class "Default")
      (node (ref "U36") (pin "6") (pinfunction "DNU_3_6") (pintype "passive"))
    )
    (net (code "367") (name "unconnected-(U36-DNU_4-Pad11)") (class "Default")
      (node (ref "U36") (pin "11") (pinfunction "DNU_4_11") (pintype "passive"))
    )
    (net (code "368") (name "unconnected-(U36-DNU_5-Pad12)") (class "Default")
      (node (ref "U36") (pin "12") (pinfunction "DNU_5_12") (pintype "passive"))
    )
    (net (code "369") (name "unconnected-(U36-DNU_6-Pad13)") (class "Default")
      (node (ref "U36") (pin "13") (pinfunction "DNU_6_13") (pintype "passive"))
    )
    (net (code "370") (name "unconnected-(U36-DNU_7-Pad14)") (class "Default")
      (node (ref "U36") (pin "14") (pinfunction "DNU_7_14") (pintype "passive"))
    )
    (net (code "371") (name "unconnected-(U37-DNU_1-Pad4)") (class "Default")
      (node (ref "U37") (pin "4") (pinfunction "DNU_1_4") (pintype "passive"))
    )
    (net (code "372") (name "unconnected-(U37-DNU_2-Pad5)") (class "Default")
      (node (ref "U37") (pin "5") (pinfunction "DNU_2_5") (pintype "passive"))
    )
    (net (code "373") (name "unconnected-(U37-DNU_3-Pad6)") (class "Default")
      (node (ref "U37") (pin "6") (pinfunction "DNU_3_6") (pintype "passive"))
    )
    (net (code "374") (name "unconnected-(U37-DNU_4-Pad11)") (class "Default")
      (node (ref "U37") (pin "11") (pinfunction "DNU_4_11") (pintype "passive"))
    )
    (net (code "375") (name "unconnected-(U37-DNU_5-Pad12)") (class "Default")
      (node (ref "U37") (pin "12") (pinfunction "DNU_5_12") (pintype "passive"))
    )
    (net (code "376") (name "unconnected-(U37-DNU_6-Pad13)") (class "Default")
      (node (ref "U37") (pin "13") (pinfunction "DNU_6_13") (pintype "passive"))
    )
    (net (code "377") (name "unconnected-(U37-DNU_7-Pad14)") (class "Default")
      (node (ref "U37") (pin "14") (pinfunction "DNU_7_14") (pintype "passive"))
    )
    (net (code "378") (name "unconnected-(U38-NC_1-Pad41)") (class "Default")
      (node (ref "U38") (pin "41") (pinfunction "NC_1_41") (pintype "passive"))
    )
    (net (code "379") (name "unconnected-(U38-NC_2-Pad42)") (class "Default")
      (node (ref "U38") (pin "42") (pinfunction "NC_2_42") (pintype "passive"))
    )
    (net (code "380") (name "unconnected-(U38-NC_3-Pad44)") (class "Default")
      (node (ref "U38") (pin "44") (pinfunction "NC_3_44") (pintype "passive"))
    )
    (net (code "381") (name "unconnected-(U38-S1-Pad12)") (class "Default")
      (node (ref "U38") (pin "12") (pinfunction "S1_12") (pintype "passive"))
    )
    (net (code "382") (name "unconnected-(U38-S26-Pad34)") (class "Default")
      (node (ref "U38") (pin "34") (pinfunction "S26_34") (pintype "passive"))
    )
    (net (code "383") (name "unconnected-(U38-S27-Pad35)") (class "Default")
      (node (ref "U38") (pin "35") (pinfunction "S27_35") (pintype "passive"))
    )
    (net (code "384") (name "unconnected-(U38-S28-Pad36)") (class "Default")
      (node (ref "U38") (pin "36") (pinfunction "S28_36") (pintype "passive"))
    )
    (net (code "385") (name "unconnected-(U38-S29-Pad37)") (class "Default")
      (node (ref "U38") (pin "37") (pinfunction "S29_37") (pintype "passive"))
    )
    (net (code "386") (name "unconnected-(U38-S30-Pad38)") (class "Default")
      (node (ref "U38") (pin "38") (pinfunction "S30_38") (pintype "passive"))
    )
    (net (code "387") (name "unconnected-(U38-S31-Pad39)") (class "Default")
      (node (ref "U38") (pin "39") (pinfunction "S31_39") (pintype "passive"))
    )
    (net (code "388") (name "unconnected-(U38-S32-Pad40)") (class "Default")
      (node (ref "U38") (pin "40") (pinfunction "S32_40") (pintype "passive"))
    )
    (net (code "389") (name "unconnected-(U39-SIO2-Pad3)") (class "Default")
      (node (ref "U39") (pin "3") (pinfunction "SIO2_3") (pintype "passive"))
    )
    (net (code "390") (name "unconnected-(U40-DNU_1-Pad4)") (class "Default")
      (node (ref "U40") (pin "4") (pinfunction "DNU_1_4") (pintype "passive"))
    )
    (net (code "391") (name "unconnected-(U40-DNU_2-Pad5)") (class "Default")
      (node (ref "U40") (pin "5") (pinfunction "DNU_2_5") (pintype "passive"))
    )
    (net (code "392") (name "unconnected-(U40-DNU_3-Pad6)") (class "Default")
      (node (ref "U40") (pin "6") (pinfunction "DNU_3_6") (pintype "passive"))
    )
    (net (code "393") (name "unconnected-(U40-DNU_4-Pad11)") (class "Default")
      (node (ref "U40") (pin "11") (pinfunction "DNU_4_11") (pintype "passive"))
    )
    (net (code "394") (name "unconnected-(U40-DNU_5-Pad12)") (class "Default")
      (node (ref "U40") (pin "12") (pinfunction "DNU_5_12") (pintype "passive"))
    )
    (net (code "395") (name "unconnected-(U40-DNU_6-Pad13)") (class "Default")
      (node (ref "U40") (pin "13") (pinfunction "DNU_6_13") (pintype "passive"))
    )
    (net (code "396") (name "unconnected-(U40-DNU_7-Pad14)") (class "Default")
      (node (ref "U40") (pin "14") (pinfunction "DNU_7_14") (pintype "passive"))
    )
    (net (code "397") (name "unconnected-(U41-DNU_1-Pad4)") (class "Default")
      (node (ref "U41") (pin "4") (pinfunction "DNU_1_4") (pintype "passive"))
    )
    (net (code "398") (name "unconnected-(U41-DNU_2-Pad5)") (class "Default")
      (node (ref "U41") (pin "5") (pinfunction "DNU_2_5") (pintype "passive"))
    )
    (net (code "399") (name "unconnected-(U41-DNU_3-Pad6)") (class "Default")
      (node (ref "U41") (pin "6") (pinfunction "DNU_3_6") (pintype "passive"))
    )
    (net (code "400") (name "unconnected-(U41-DNU_4-Pad11)") (class "Default")
      (node (ref "U41") (pin "11") (pinfunction "DNU_4_11") (pintype "passive"))
    )
    (net (code "401") (name "unconnected-(U41-DNU_5-Pad12)") (class "Default")
      (node (ref "U41") (pin "12") (pinfunction "DNU_5_12") (pintype "passive"))
    )
    (net (code "402") (name "unconnected-(U41-DNU_6-Pad13)") (class "Default")
      (node (ref "U41") (pin "13") (pinfunction "DNU_6_13") (pintype "passive"))
    )
    (net (code "403") (name "unconnected-(U41-DNU_7-Pad14)") (class "Default")
      (node (ref "U41") (pin "14") (pinfunction "DNU_7_14") (pintype "passive"))
    )
    (net (code "404") (name "unconnected-(U42-DNU_1-Pad4)") (class "Default")
      (node (ref "U42") (pin "4") (pinfunction "DNU_1_4") (pintype "passive"))
    )
    (net (code "405") (name "unconnected-(U42-DNU_2-Pad5)") (class "Default")
      (node (ref "U42") (pin "5") (pinfunction "DNU_2_5") (pintype "passive"))
    )
    (net (code "406") (name "unconnected-(U42-DNU_3-Pad6)") (class "Default")
      (node (ref "U42") (pin "6") (pinfunction "DNU_3_6") (pintype "passive"))
    )
    (net (code "407") (name "unconnected-(U42-DNU_4-Pad11)") (class "Default")
      (node (ref "U42") (pin "11") (pinfunction "DNU_4_11") (pintype "passive"))
    )
    (net (code "408") (name "unconnected-(U42-DNU_5-Pad12)") (class "Default")
      (node (ref "U42") (pin "12") (pinfunction "DNU_5_12") (pintype "passive"))
    )
    (net (code "409") (name "unconnected-(U42-DNU_6-Pad13)") (class "Default")
      (node (ref "U42") (pin "13") (pinfunction "DNU_6_13") (pintype "passive"))
    )
    (net (code "410") (name "unconnected-(U42-DNU_7-Pad14)") (class "Default")
      (node (ref "U42") (pin "14") (pinfunction "DNU_7_14") (pintype "passive"))
    )
    (net (code "411") (name "unconnected-(U43-DNU_1-Pad4)") (class "Default")
      (node (ref "U43") (pin "4") (pinfunction "DNU_1_4") (pintype "passive"))
    )
    (net (code "412") (name "unconnected-(U43-DNU_2-Pad5)") (class "Default")
      (node (ref "U43") (pin "5") (pinfunction "DNU_2_5") (pintype "passive"))
    )
    (net (code "413") (name "unconnected-(U43-DNU_3-Pad6)") (class "Default")
      (node (ref "U43") (pin "6") (pinfunction "DNU_3_6") (pintype "passive"))
    )
    (net (code "414") (name "unconnected-(U43-DNU_4-Pad11)") (class "Default")
      (node (ref "U43") (pin "11") (pinfunction "DNU_4_11") (pintype "passive"))
    )
    (net (code "415") (name "unconnected-(U43-DNU_5-Pad12)") (class "Default")
      (node (ref "U43") (pin "12") (pinfunction "DNU_5_12") (pintype "passive"))
    )
    (net (code "416") (name "unconnected-(U43-DNU_6-Pad13)") (class "Default")
      (node (ref "U43") (pin "13") (pinfunction "DNU_6_13") (pintype "passive"))
    )
    (net (code "417") (name "unconnected-(U43-DNU_7-Pad14)") (class "Default")
      (node (ref "U43") (pin "14") (pinfunction "DNU_7_14") (pintype "passive"))
    )
    (net (code "418") (name "unconnected-(U45-DNU_1-Pad4)") (class "Default")
      (node (ref "U45") (pin "4") (pinfunction "DNU_1_4") (pintype "passive"))
    )
    (net (code "419") (name "unconnected-(U45-DNU_2-Pad5)") (class "Default")
      (node (ref "U45") (pin "5") (pinfunction "DNU_2_5") (pintype "passive"))
    )
    (net (code "420") (name "unconnected-(U45-DNU_3-Pad6)") (class "Default")
      (node (ref "U45") (pin "6") (pinfunction "DNU_3_6") (pintype "passive"))
    )
    (net (code "421") (name "unconnected-(U45-DNU_4-Pad11)") (class "Default")
      (node (ref "U45") (pin "11") (pinfunction "DNU_4_11") (pintype "passive"))
    )
    (net (code "422") (name "unconnected-(U45-DNU_5-Pad12)") (class "Default")
      (node (ref "U45") (pin "12") (pinfunction "DNU_5_12") (pintype "passive"))
    )
    (net (code "423") (name "unconnected-(U45-DNU_6-Pad13)") (class "Default")
      (node (ref "U45") (pin "13") (pinfunction "DNU_6_13") (pintype "passive"))
    )
    (net (code "424") (name "unconnected-(U45-DNU_7-Pad14)") (class "Default")
      (node (ref "U45") (pin "14") (pinfunction "DNU_7_14") (pintype "passive"))
    )
    (net (code "425") (name "unconnected-(U46-DNU_1-Pad4)") (class "Default")
      (node (ref "U46") (pin "4") (pinfunction "DNU_1_4") (pintype "passive"))
    )
    (net (code "426") (name "unconnected-(U46-DNU_2-Pad5)") (class "Default")
      (node (ref "U46") (pin "5") (pinfunction "DNU_2_5") (pintype "passive"))
    )
    (net (code "427") (name "unconnected-(U46-DNU_3-Pad6)") (class "Default")
      (node (ref "U46") (pin "6") (pinfunction "DNU_3_6") (pintype "passive"))
    )
    (net (code "428") (name "unconnected-(U46-DNU_4-Pad11)") (class "Default")
      (node (ref "U46") (pin "11") (pinfunction "DNU_4_11") (pintype "passive"))
    )
    (net (code "429") (name "unconnected-(U46-DNU_5-Pad12)") (class "Default")
      (node (ref "U46") (pin "12") (pinfunction "DNU_5_12") (pintype "passive"))
    )
    (net (code "430") (name "unconnected-(U46-DNU_6-Pad13)") (class "Default")
      (node (ref "U46") (pin "13") (pinfunction "DNU_6_13") (pintype "passive"))
    )
    (net (code "431") (name "unconnected-(U46-DNU_7-Pad14)") (class "Default")
      (node (ref "U46") (pin "14") (pinfunction "DNU_7_14") (pintype "passive"))
    )
    (net (code "432") (name "unconnected-(U47-DNU_1-Pad4)") (class "Default")
      (node (ref "U47") (pin "4") (pinfunction "DNU_1_4") (pintype "passive"))
    )
    (net (code "433") (name "unconnected-(U47-DNU_2-Pad5)") (class "Default")
      (node (ref "U47") (pin "5") (pinfunction "DNU_2_5") (pintype "passive"))
    )
    (net (code "434") (name "unconnected-(U47-DNU_3-Pad6)") (class "Default")
      (node (ref "U47") (pin "6") (pinfunction "DNU_3_6") (pintype "passive"))
    )
    (net (code "435") (name "unconnected-(U47-DNU_4-Pad11)") (class "Default")
      (node (ref "U47") (pin "11") (pinfunction "DNU_4_11") (pintype "passive"))
    )
    (net (code "436") (name "unconnected-(U47-DNU_5-Pad12)") (class "Default")
      (node (ref "U47") (pin "12") (pinfunction "DNU_5_12") (pintype "passive"))
    )
    (net (code "437") (name "unconnected-(U47-DNU_6-Pad13)") (class "Default")
      (node (ref "U47") (pin "13") (pinfunction "DNU_6_13") (pintype "passive"))
    )
    (net (code "438") (name "unconnected-(U47-DNU_7-Pad14)") (class "Default")
      (node (ref "U47") (pin "14") (pinfunction "DNU_7_14") (pintype "passive"))
    )
    (net (code "439") (name "unconnected-(U48-DNU_1-Pad4)") (class "Default")
      (node (ref "U48") (pin "4") (pinfunction "DNU_1_4") (pintype "passive"))
    )
    (net (code "440") (name "unconnected-(U48-DNU_2-Pad5)") (class "Default")
      (node (ref "U48") (pin "5") (pinfunction "DNU_2_5") (pintype "passive"))
    )
    (net (code "441") (name "unconnected-(U48-DNU_3-Pad6)") (class "Default")
      (node (ref "U48") (pin "6") (pinfunction "DNU_3_6") (pintype "passive"))
    )
    (net (code "442") (name "unconnected-(U48-DNU_4-Pad11)") (class "Default")
      (node (ref "U48") (pin "11") (pinfunction "DNU_4_11") (pintype "passive"))
    )
    (net (code "443") (name "unconnected-(U48-DNU_5-Pad12)") (class "Default")
      (node (ref "U48") (pin "12") (pinfunction "DNU_5_12") (pintype "passive"))
    )
    (net (code "444") (name "unconnected-(U48-DNU_6-Pad13)") (class "Default")
      (node (ref "U48") (pin "13") (pinfunction "DNU_6_13") (pintype "passive"))
    )
    (net (code "445") (name "unconnected-(U48-DNU_7-Pad14)") (class "Default")
      (node (ref "U48") (pin "14") (pinfunction "DNU_7_14") (pintype "passive"))
    )
    (net (code "446") (name "unconnected-(U50B-VDD-Pad8)") (class "Default")
      (node (ref "U50") (pin "8") (pinfunction "VDD_8") (pintype "power_in"))
    )
    (net (code "447") (name "unconnected-(U50B-VSS-Pad4)") (class "Default")
      (node (ref "U50") (pin "4") (pinfunction "VSS_4") (pintype "power_in"))
    )
  )
)
